# ControlBoardv1_3.net
KiCad netlist of a schematic drawn in EAGLE
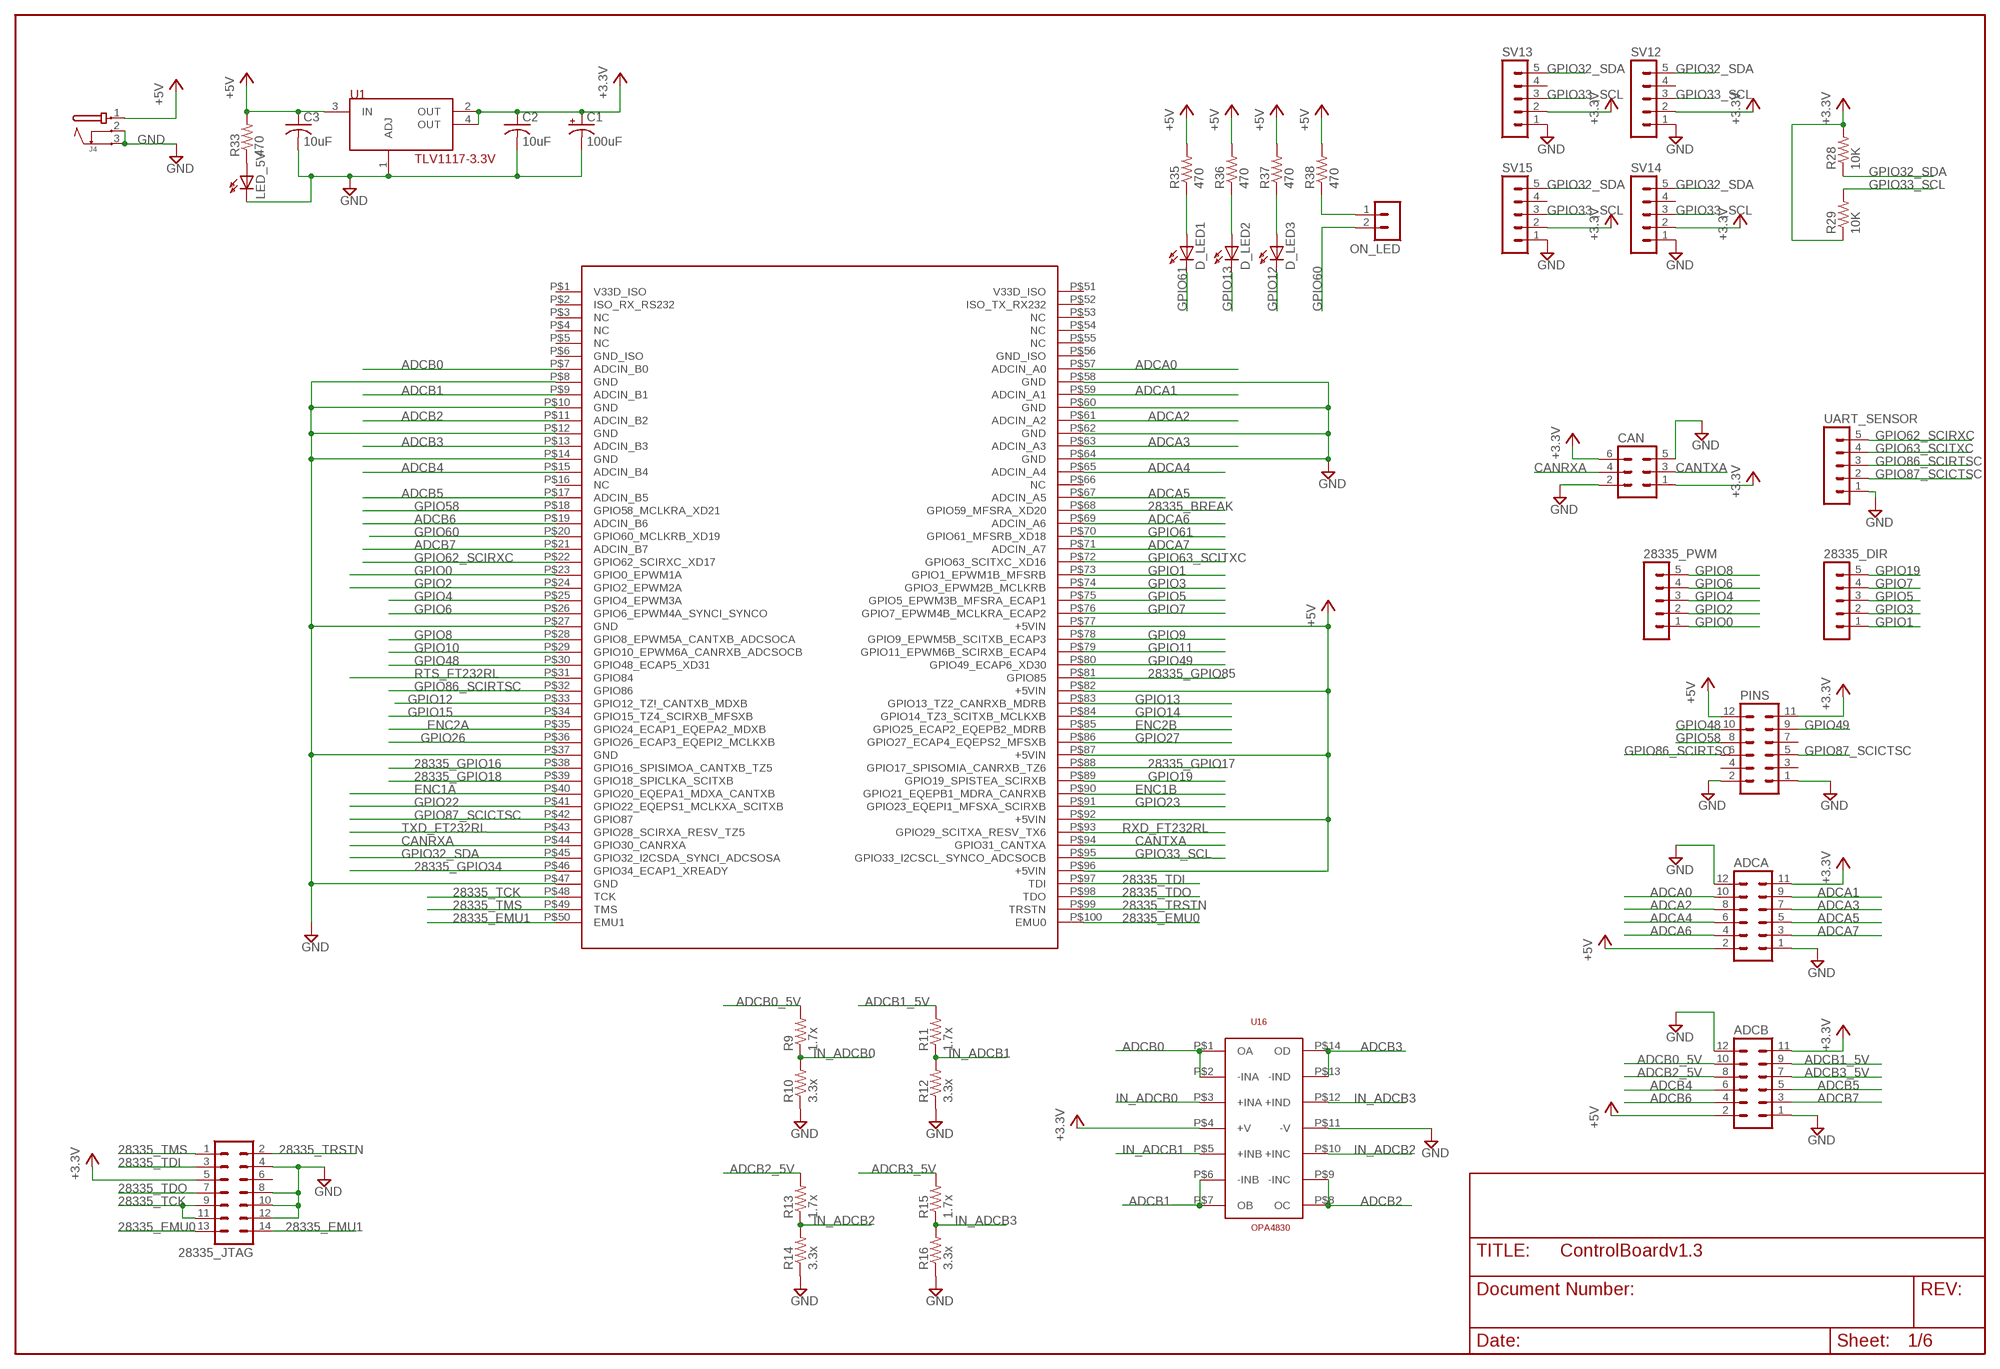
[diagram p0: schematic, sheet 1]
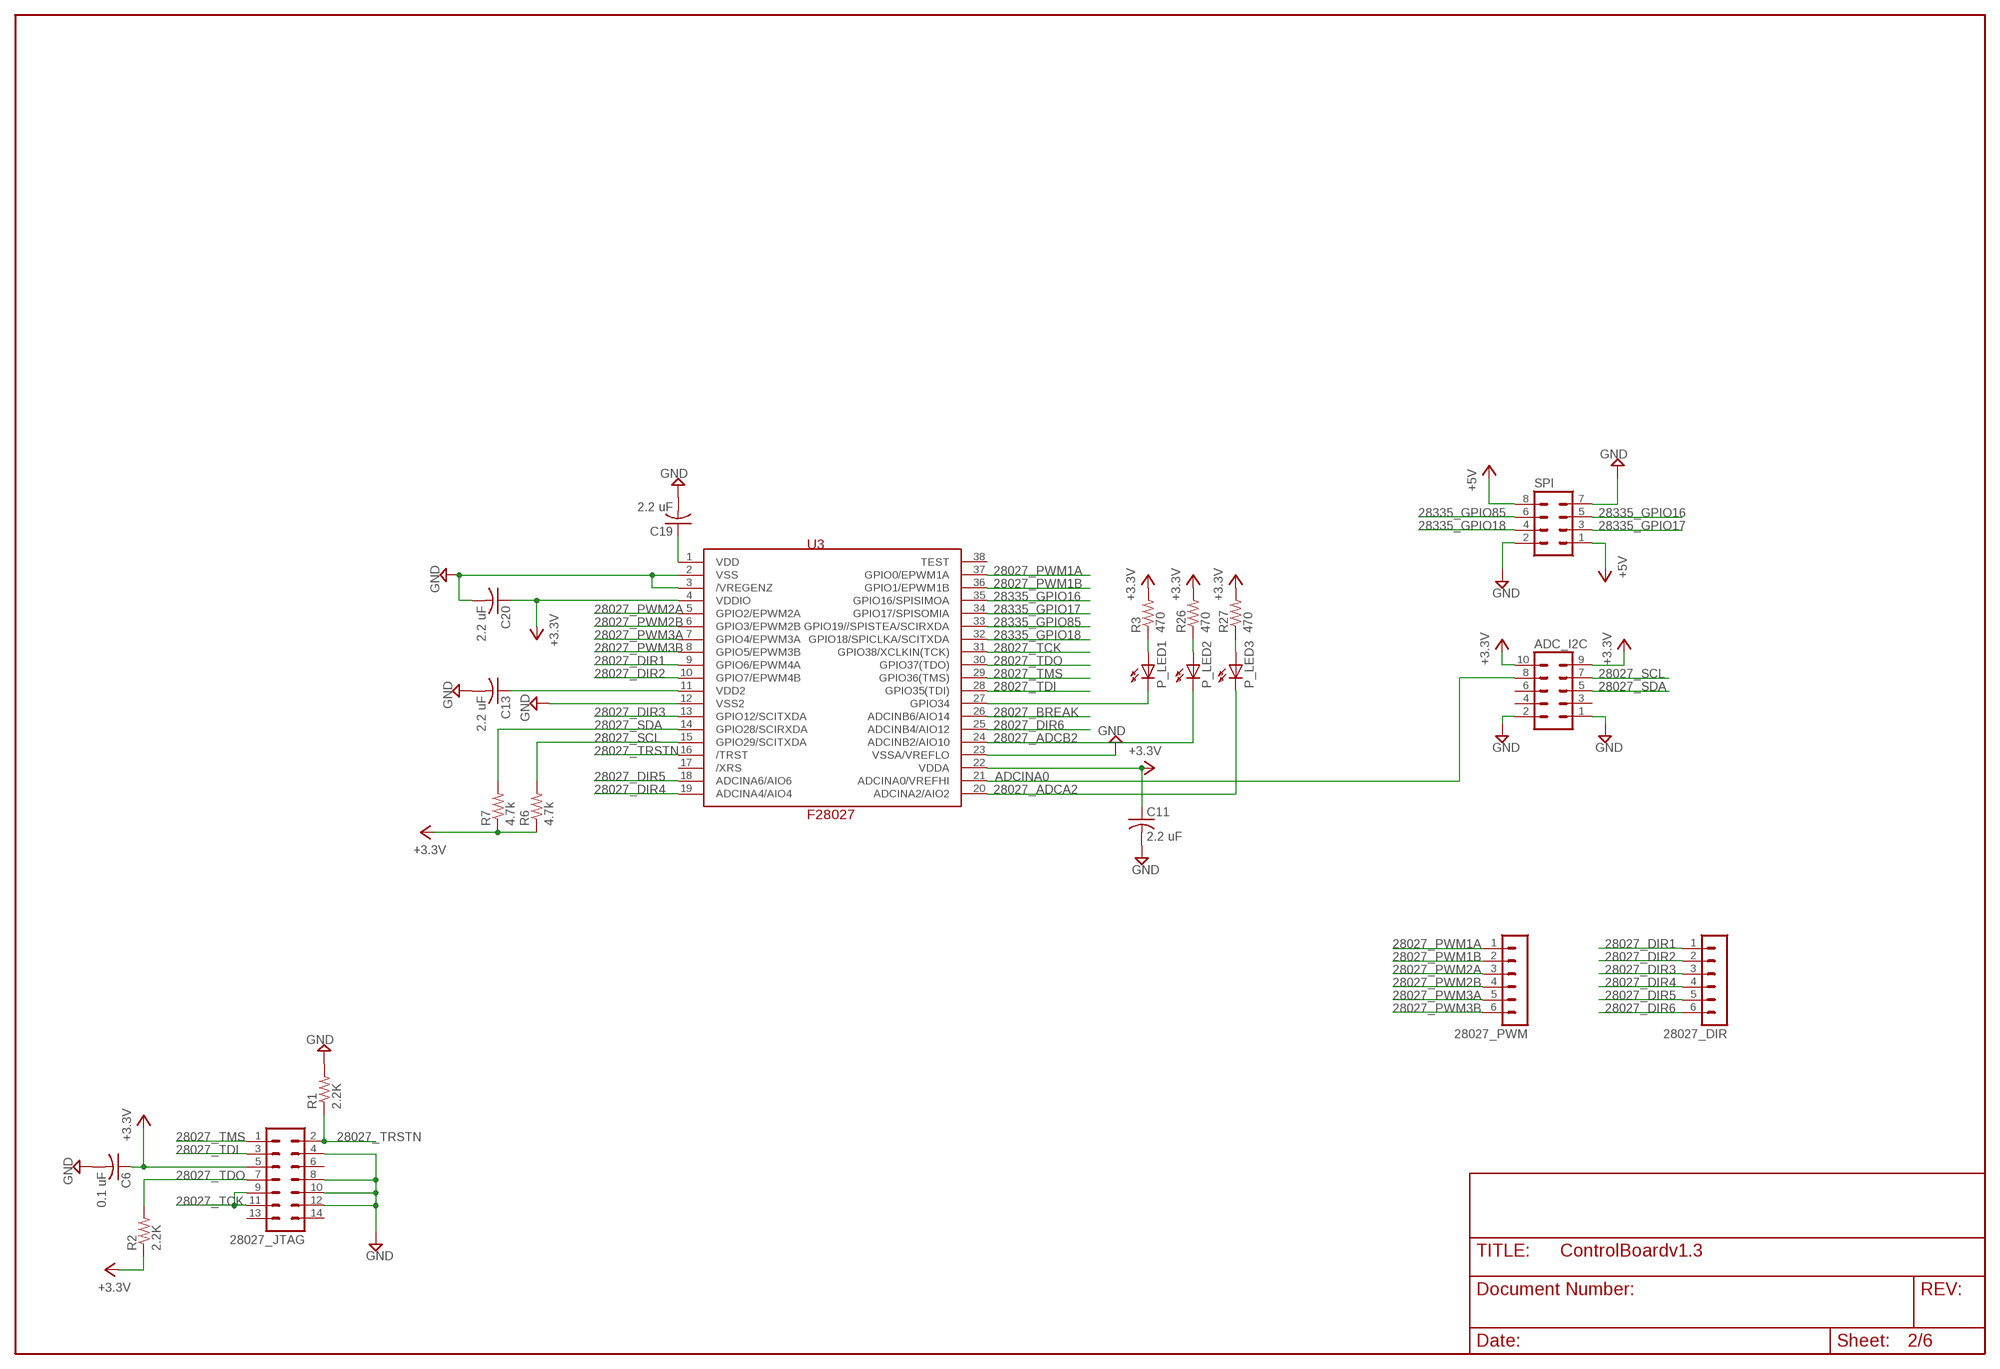
[diagram p1: schematic, sheet 2]
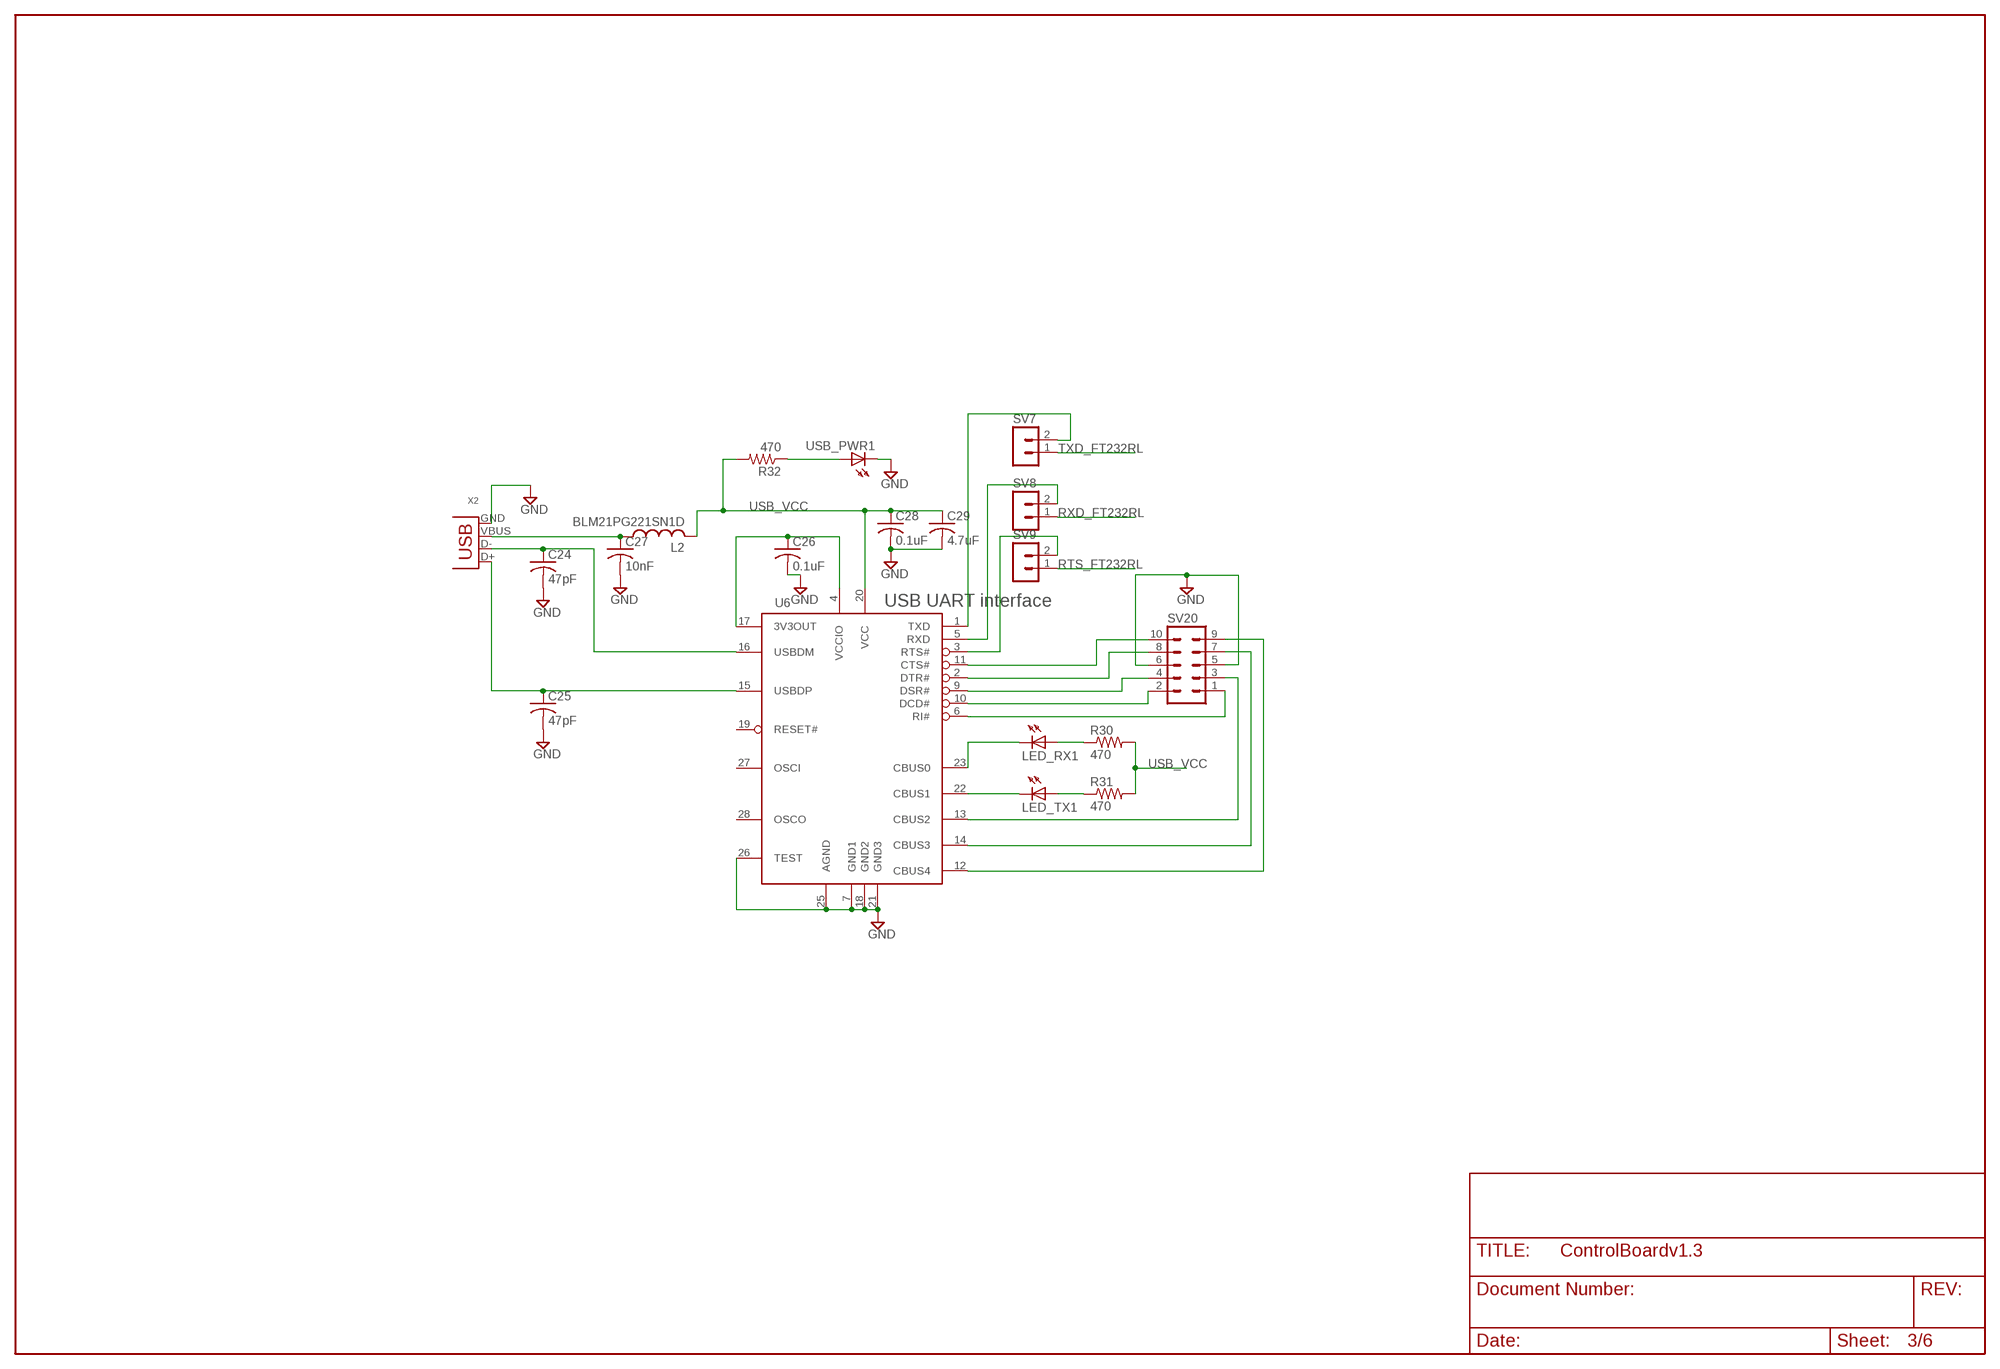
[diagram p2: schematic, sheet 3]
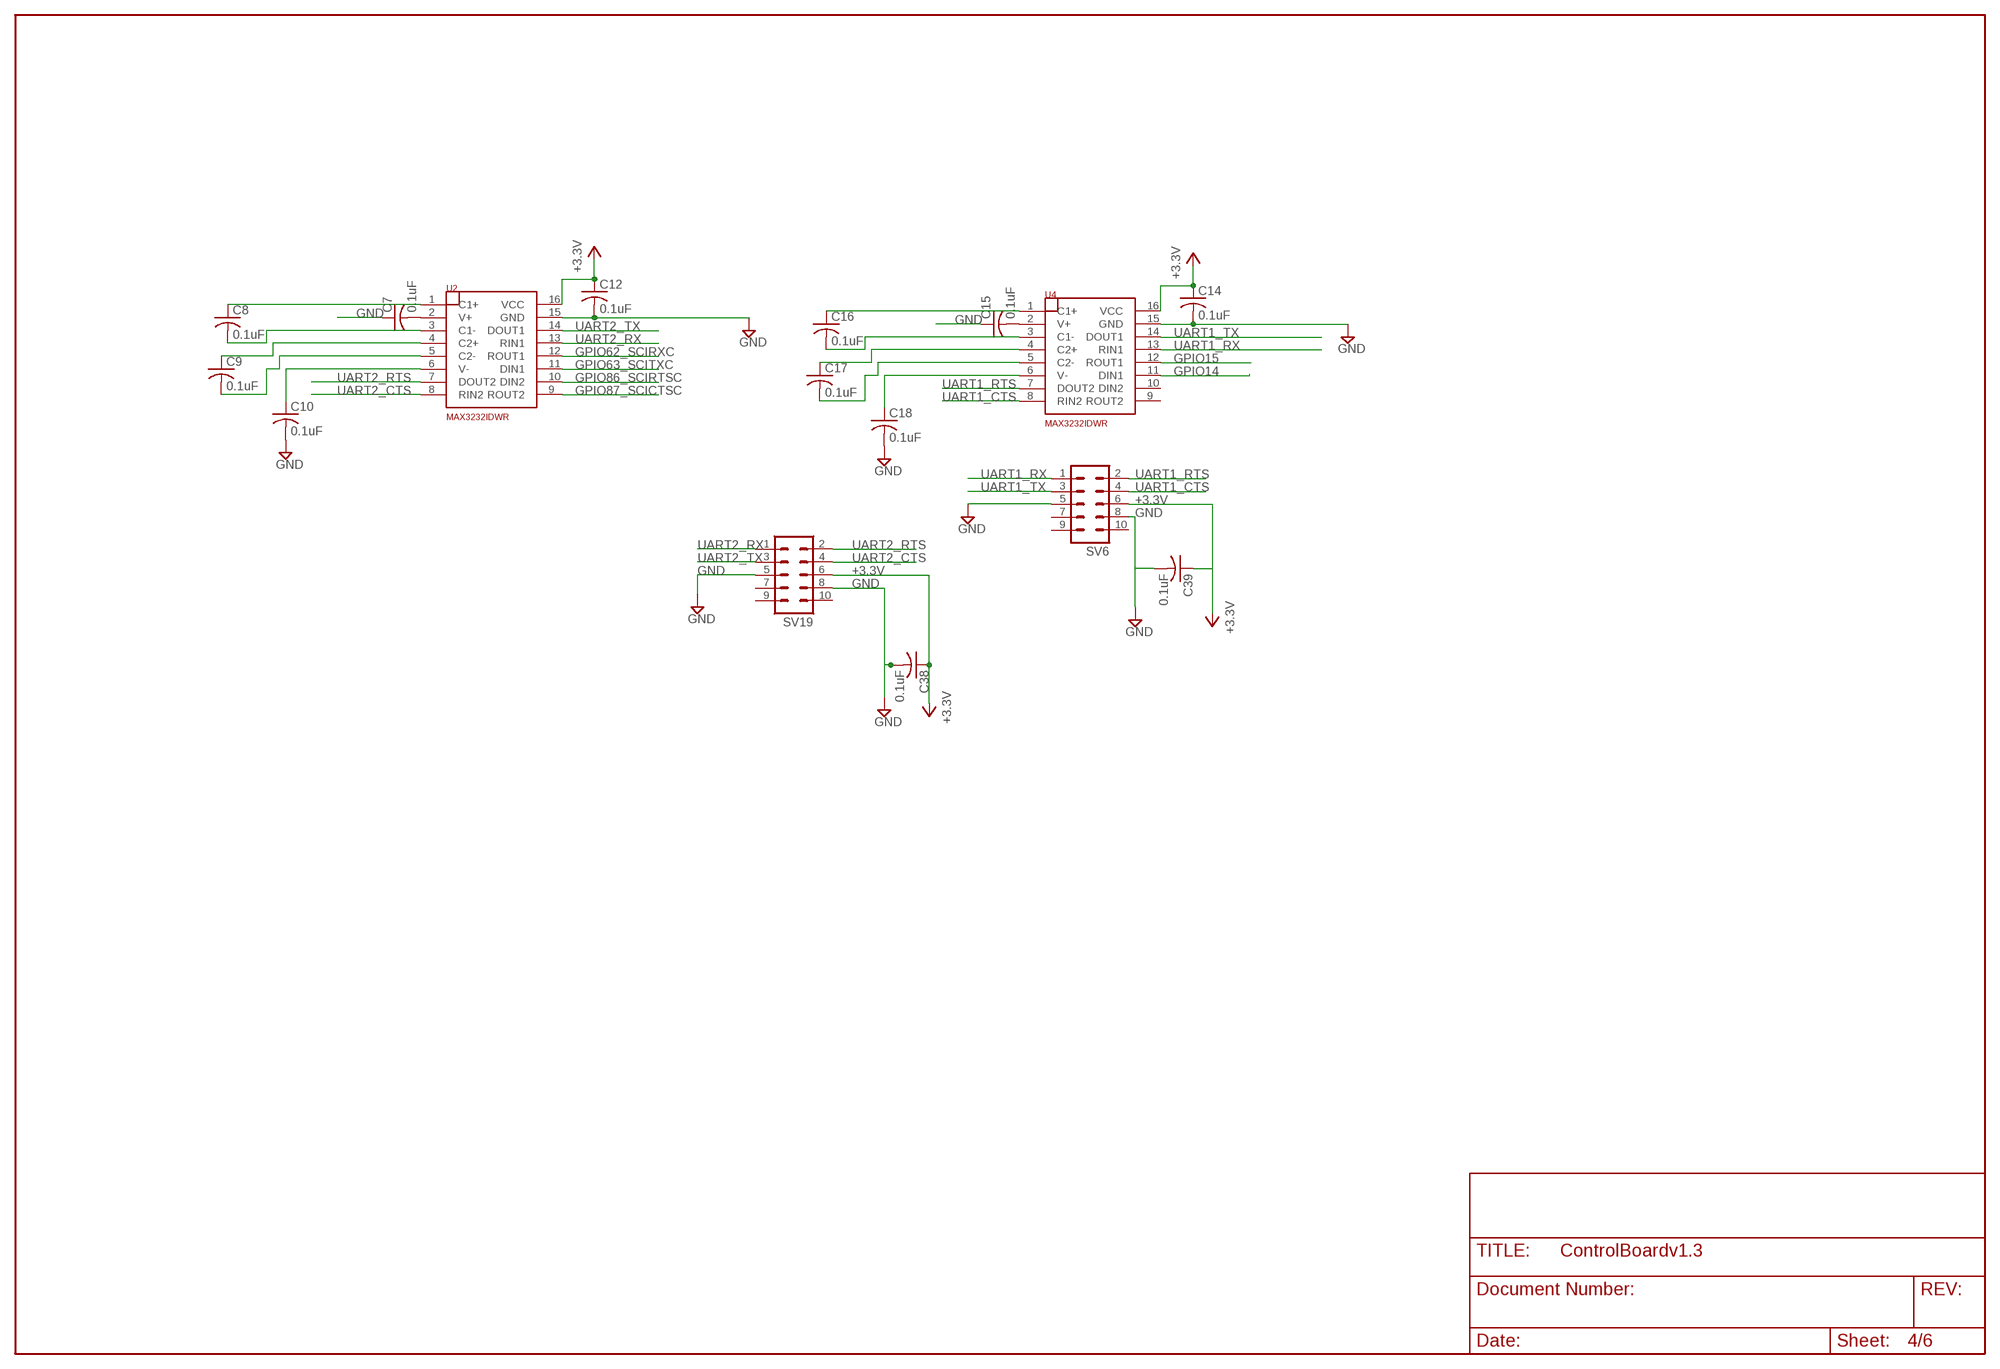
[diagram p3: schematic, sheet 4]
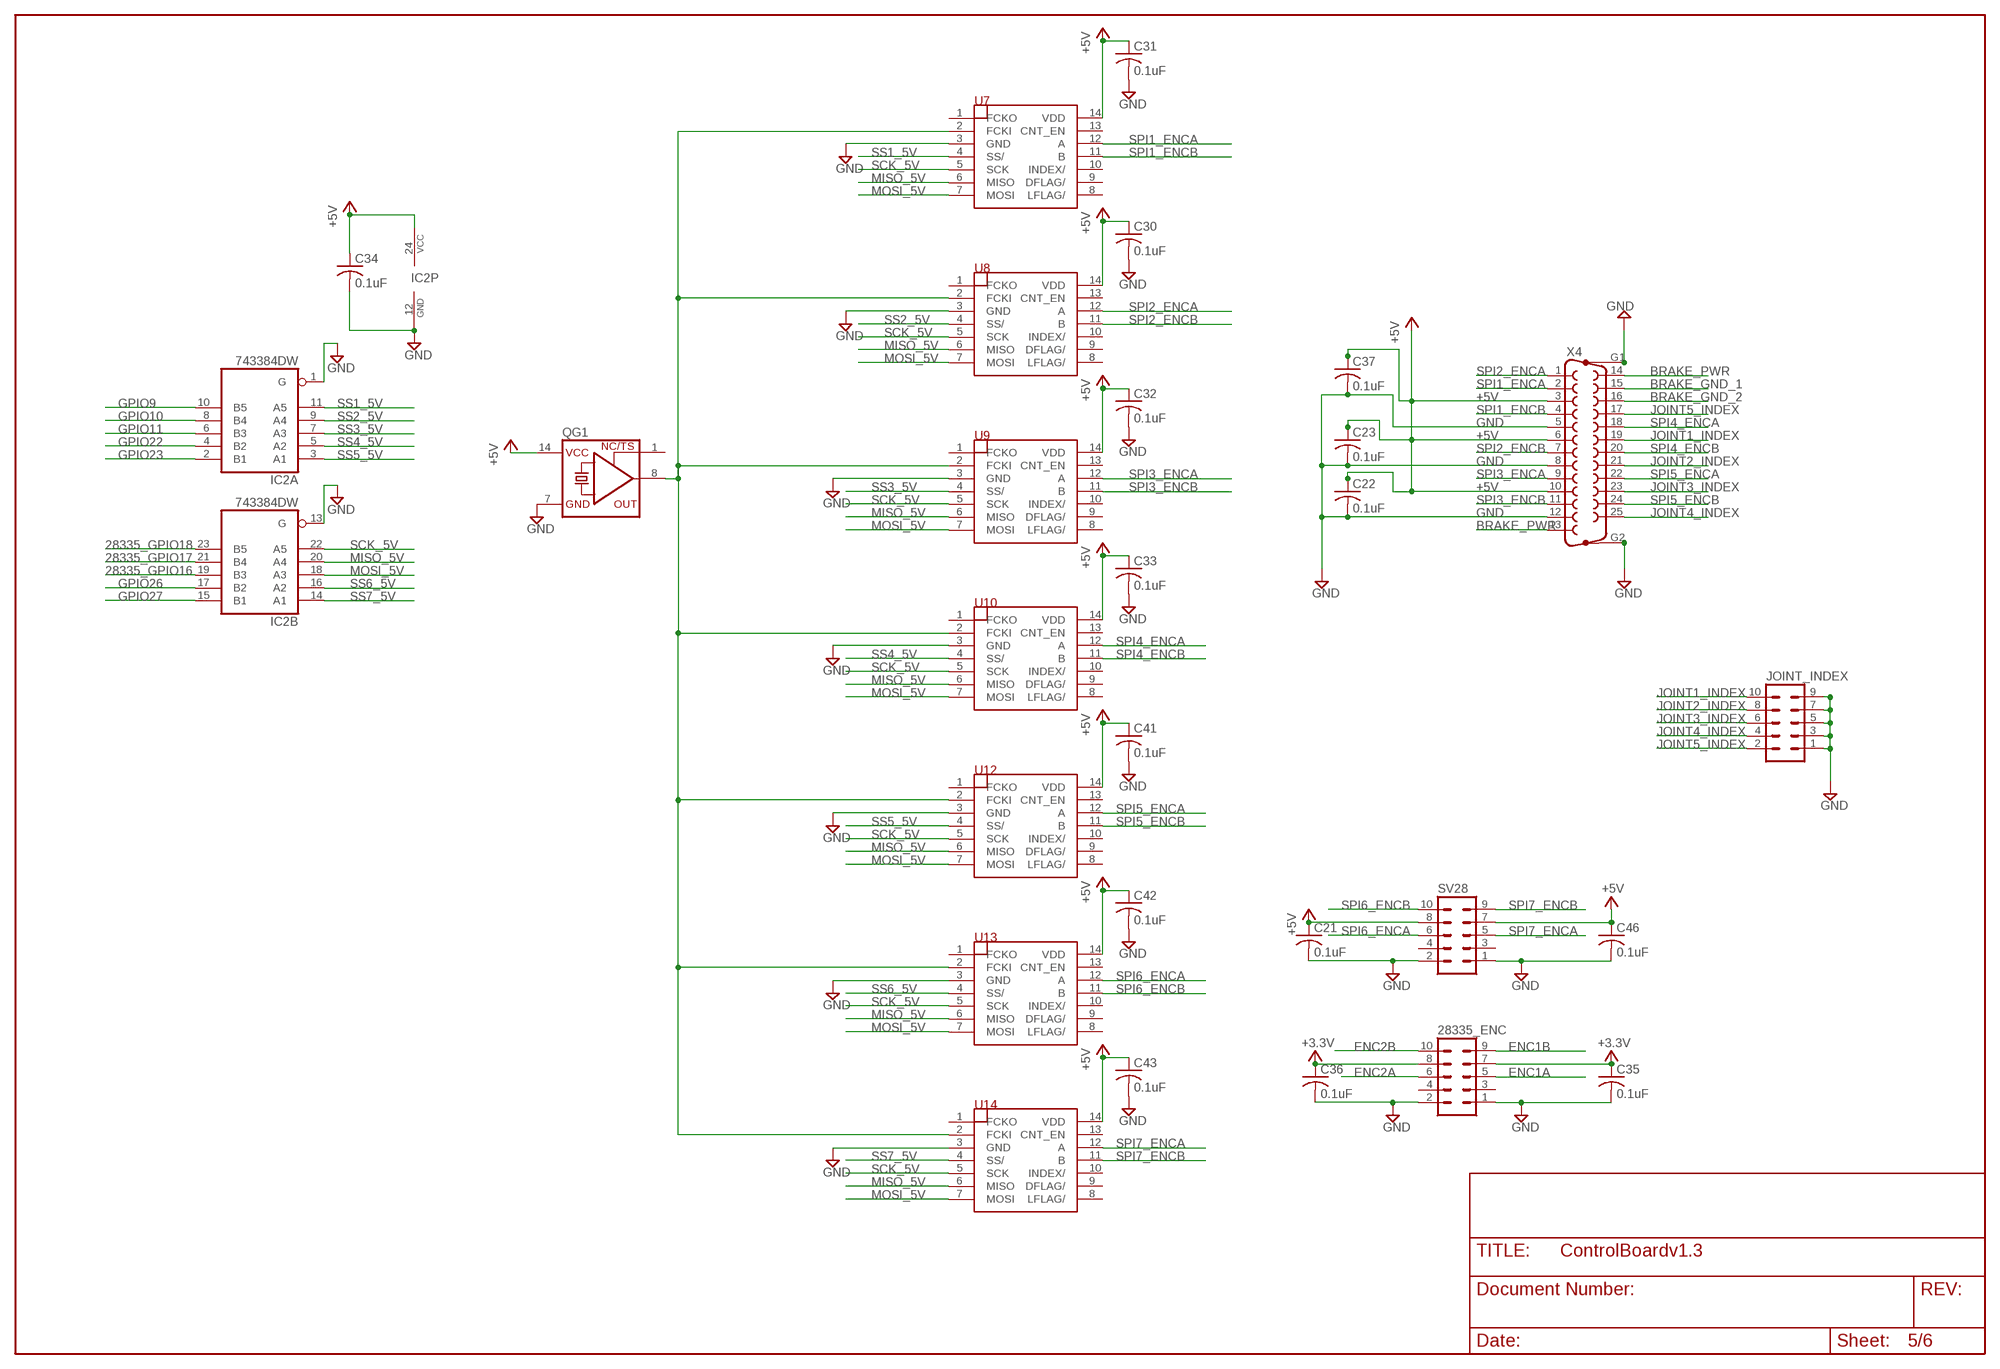
[diagram p4: schematic, sheet 5]
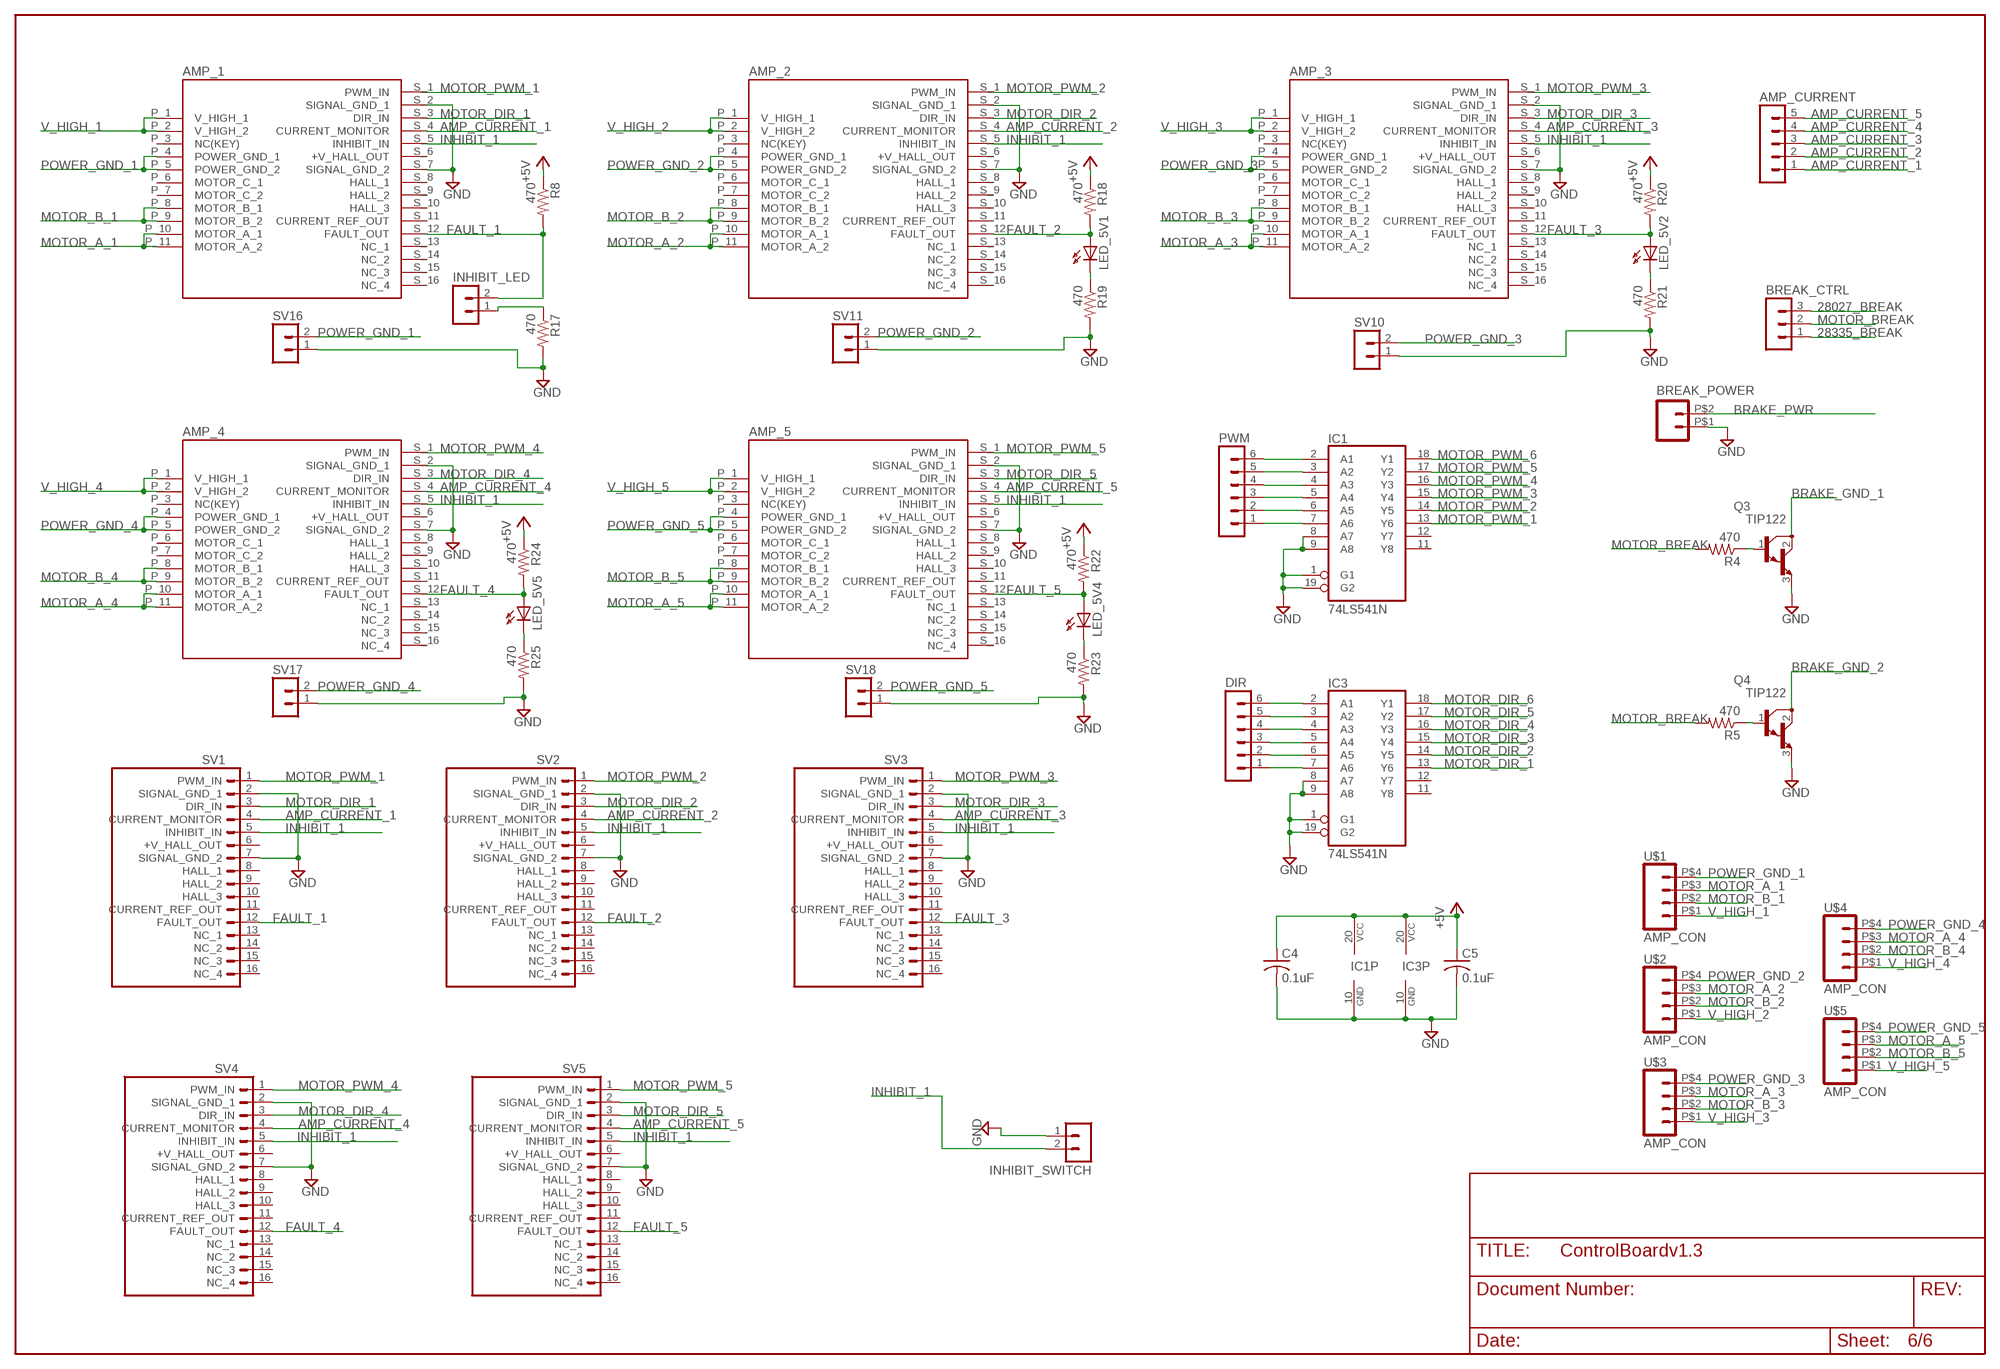
[diagram p5: schematic, sheet 6]

(export (version "E")
  (design (tool "Eeschema 10.0.6"))
  (components
    (comp (ref "C24")
      (value "47pF")
      (footprint "eagle-import:C1206")
      (libsource (lib "eagle-import") (part "C-USC1206"))
    )
    (comp (ref "C25")
      (value "47pF")
      (footprint "eagle-import:C1206")
      (libsource (lib "eagle-import") (part "C-USC1206"))
    )
    (comp (ref "C26")
      (value "0.1uF")
      (footprint "eagle-import:C1206")
      (libsource (lib "eagle-import") (part "C-USC1206"))
    )
    (comp (ref "C27")
      (value "10nF")
      (footprint "eagle-import:C1206")
      (libsource (lib "eagle-import") (part "C-USC1206"))
    )
    (comp (ref "C28")
      (value "0.1uF")
      (footprint "eagle-import:C1206")
      (libsource (lib "eagle-import") (part "C-USC1206"))
    )
    (comp (ref "C29")
      (value "4.7uF")
      (footprint "eagle-import:C1206")
      (libsource (lib "eagle-import") (part "C-USC1206"))
    )
    (comp (ref "L2")
      (value "BLM21PG221SN1D")
      (footprint "eagle-import:L0805")
      (libsource (lib "eagle-import") (part "L-USL0805"))
    )
    (comp (ref "LED_RX1")
      (value "LED3MM")
      (footprint "eagle-import:LED3MM")
      (libsource (lib "eagle-import") (part "LED3MM"))
    )
    (comp (ref "LED_TX1")
      (value "LED3MM")
      (footprint "eagle-import:LED3MM")
      (libsource (lib "eagle-import") (part "LED3MM"))
    )
    (comp (ref "R30")
      (value "470")
      (footprint "eagle-import:M1206")
      (libsource (lib "eagle-import") (part "R-US_M1206"))
    )
    (comp (ref "R31")
      (value "470")
      (footprint "eagle-import:M1206")
      (libsource (lib "eagle-import") (part "R-US_M1206"))
    )
    (comp (ref "R32")
      (value "470")
      (footprint "eagle-import:M1206")
      (libsource (lib "eagle-import") (part "R-US_M1206"))
    )
    (comp (ref "SV7")
      (value "MA02-1")
      (footprint "eagle-import:MA02-1")
      (libsource (lib "eagle-import") (part "MA02-1"))
    )
    (comp (ref "SV8")
      (value "MA02-1")
      (footprint "eagle-import:MA02-1")
      (libsource (lib "eagle-import") (part "MA02-1"))
    )
    (comp (ref "SV9")
      (value "MA02-1")
      (footprint "eagle-import:MA02-1")
      (libsource (lib "eagle-import") (part "MA02-1"))
    )
    (comp (ref "SV20")
      (value "MA05-2")
      (footprint "eagle-import:MA05-2")
      (libsource (lib "eagle-import") (part "MA05-2"))
    )
    (comp (ref "U6")
      (value "FT232RL")
      (footprint "eagle-import:SSOP28DB")
      (libsource (lib "eagle-import") (part "FT232RL"))
    )
    (comp (ref "USB_PWR1")
      (value "LED3MM")
      (footprint "eagle-import:LED3MM")
      (libsource (lib "eagle-import") (part "LED3MM"))
    )
    (comp (ref "X2")
      (value "USB-B-H")
      (footprint "eagle-import:USB-B-H")
      (libsource (lib "eagle-import") (part "USB-B-H"))
    )
    (comp (ref "28027_DIR")
      (value "MA06-1")
      (footprint "eagle-import:MA06-1")
      (libsource (lib "eagle-import") (part "MA06-1"))
    )
    (comp (ref "28027_JTAG")
      (value "MA07-2")
      (footprint "eagle-import:MA07-2")
      (libsource (lib "eagle-import") (part "MA07-2"))
    )
    (comp (ref "28027_PWM")
      (value "MA06-1")
      (footprint "eagle-import:MA06-1")
      (libsource (lib "eagle-import") (part "MA06-1"))
    )
    (comp (ref "ADC_I2C")
      (value "MA05-2")
      (footprint "eagle-import:MA05-2")
      (libsource (lib "eagle-import") (part "MA05-2"))
    )
    (comp (ref "C6")
      (value "0.1 uF")
      (footprint "eagle-import:C1206")
      (libsource (lib "eagle-import") (part "C-USC1206"))
    )
    (comp (ref "C11")
      (value "2.2 uF")
      (footprint "eagle-import:C1206")
      (libsource (lib "eagle-import") (part "C-USC1206"))
    )
    (comp (ref "C13")
      (value "2.2 uF")
      (footprint "eagle-import:C1206")
      (libsource (lib "eagle-import") (part "C-USC1206"))
    )
    (comp (ref "C19")
      (value "2.2 uF")
      (footprint "eagle-import:C1206")
      (libsource (lib "eagle-import") (part "C-USC1206"))
    )
    (comp (ref "C20")
      (value "2.2 uF")
      (footprint "eagle-import:C1206")
      (libsource (lib "eagle-import") (part "C-USC1206"))
    )
    (comp (ref "P_LED1")
      (value "LED3MM")
      (footprint "eagle-import:LED3MM")
      (libsource (lib "eagle-import") (part "LED3MM"))
    )
    (comp (ref "P_LED2")
      (value "LED3MM")
      (footprint "eagle-import:LED3MM")
      (libsource (lib "eagle-import") (part "LED3MM"))
    )
    (comp (ref "P_LED3")
      (value "LED3MM")
      (footprint "eagle-import:LED3MM")
      (libsource (lib "eagle-import") (part "LED3MM"))
    )
    (comp (ref "R1")
      (value "2.2K")
      (footprint "eagle-import:M1206")
      (libsource (lib "eagle-import") (part "R-US_M1206"))
    )
    (comp (ref "R2")
      (value "2.2K")
      (footprint "eagle-import:M1206")
      (libsource (lib "eagle-import") (part "R-US_M1206"))
    )
    (comp (ref "R3")
      (value "470")
      (footprint "eagle-import:M1206")
      (libsource (lib "eagle-import") (part "R-US_M1206"))
    )
    (comp (ref "R6")
      (value "4.7k")
      (footprint "eagle-import:M1206")
      (libsource (lib "eagle-import") (part "R-US_M1206"))
    )
    (comp (ref "R7")
      (value "4.7k")
      (footprint "eagle-import:M1206")
      (libsource (lib "eagle-import") (part "R-US_M1206"))
    )
    (comp (ref "R26")
      (value "470")
      (footprint "eagle-import:M1206")
      (libsource (lib "eagle-import") (part "R-US_M1206"))
    )
    (comp (ref "R27")
      (value "470")
      (footprint "eagle-import:M1206")
      (libsource (lib "eagle-import") (part "R-US_M1206"))
    )
    (comp (ref "SPI")
      (value "MA04-2")
      (footprint "eagle-import:MA04-2")
      (libsource (lib "eagle-import") (part "MA04-2"))
    )
    (comp (ref "U3")
      (value "F28027")
      (footprint "eagle-import:DA38")
      (libsource (lib "eagle-import") (part "TMS320F28027DAS"))
    )
    (comp (ref "28335_DIR")
      (value "MA05-1")
      (footprint "eagle-import:MA05-1")
      (libsource (lib "eagle-import") (part "MA05-1"))
    )
    (comp (ref "28335_JTAG")
      (value "MA07-2")
      (footprint "eagle-import:MA07-2")
      (libsource (lib "eagle-import") (part "MA07-2"))
    )
    (comp (ref "28335_PWM")
      (value "MA05-1")
      (footprint "eagle-import:MA05-1")
      (libsource (lib "eagle-import") (part "MA05-1"))
    )
    (comp (ref "ADCA")
      (value "MA06-2")
      (footprint "eagle-import:MA06-2")
      (libsource (lib "eagle-import") (part "con-lstb_MA06-2"))
    )
    (comp (ref "ADCB")
      (value "MA06-2")
      (footprint "eagle-import:MA06-2")
      (libsource (lib "eagle-import") (part "con-lstb_MA06-2"))
    )
    (comp (ref "C1")
      (value "100uF")
      (footprint "eagle-import:E3,5-8")
      (libsource (lib "eagle-import") (part "CPOL-USE3.5-8"))
    )
    (comp (ref "C2")
      (value "10uF")
      (footprint "eagle-import:C1206")
      (libsource (lib "eagle-import") (part "C-USC1206"))
    )
    (comp (ref "C3")
      (value "10uF")
      (footprint "eagle-import:C1206")
      (libsource (lib "eagle-import") (part "C-USC1206"))
    )
    (comp (ref "CAN")
      (value "MA03-2")
      (footprint "eagle-import:MA03-2")
      (libsource (lib "eagle-import") (part "MA03-2"))
    )
    (comp (ref "D_LED1")
      (value "LED3MM")
      (footprint "eagle-import:LED3MM")
      (libsource (lib "eagle-import") (part "LED3MM"))
    )
    (comp (ref "D_LED2")
      (value "LED3MM")
      (footprint "eagle-import:LED3MM")
      (libsource (lib "eagle-import") (part "LED3MM"))
    )
    (comp (ref "D_LED3")
      (value "LED3MM")
      (footprint "eagle-import:LED3MM")
      (libsource (lib "eagle-import") (part "LED3MM"))
    )
    (comp (ref "J4")
      (value "JACK-PMS")
      (footprint "eagle-import:JACK-PMS")
      (libsource (lib "eagle-import") (part "JACK-PMS"))
    )
    (comp (ref "J7")
      (value "F28335_CONTROLCARD")
      (footprint "eagle-import:MOLEX_DIMM_100")
      (libsource (lib "eagle-import") (part "F28335_CONTROLCARD"))
    )
    (comp (ref "LED_5V")
      (value "LED3MM")
      (footprint "eagle-import:LED3MM")
      (libsource (lib "eagle-import") (part "LED3MM"))
    )
    (comp (ref "ON_LED")
      (value "MA02-1")
      (footprint "eagle-import:MA02-1")
      (libsource (lib "eagle-import") (part "MA02-1"))
    )
    (comp (ref "PINS")
      (value "MA06-2")
      (footprint "eagle-import:MA06-2")
      (libsource (lib "eagle-import") (part "MA06-2"))
    )
    (comp (ref "R9")
      (value "1.7x")
      (footprint "eagle-import:M1206")
      (libsource (lib "eagle-import") (part "R-US_M1206"))
    )
    (comp (ref "R10")
      (value "3.3x")
      (footprint "eagle-import:M1206")
      (libsource (lib "eagle-import") (part "R-US_M1206"))
    )
    (comp (ref "R11")
      (value "1.7x")
      (footprint "eagle-import:M1206")
      (libsource (lib "eagle-import") (part "R-US_M1206"))
    )
    (comp (ref "R12")
      (value "3.3x")
      (footprint "eagle-import:M1206")
      (libsource (lib "eagle-import") (part "R-US_M1206"))
    )
    (comp (ref "R13")
      (value "1.7x")
      (footprint "eagle-import:M1206")
      (libsource (lib "eagle-import") (part "R-US_M1206"))
    )
    (comp (ref "R14")
      (value "3.3x")
      (footprint "eagle-import:M1206")
      (libsource (lib "eagle-import") (part "R-US_M1206"))
    )
    (comp (ref "R15")
      (value "1.7x")
      (footprint "eagle-import:M1206")
      (libsource (lib "eagle-import") (part "R-US_M1206"))
    )
    (comp (ref "R16")
      (value "3.3x")
      (footprint "eagle-import:M1206")
      (libsource (lib "eagle-import") (part "R-US_M1206"))
    )
    (comp (ref "R28")
      (value "10K")
      (footprint "eagle-import:M1206")
      (libsource (lib "eagle-import") (part "R-US_M1206"))
    )
    (comp (ref "R29")
      (value "10K")
      (footprint "eagle-import:M1206")
      (libsource (lib "eagle-import") (part "R-US_M1206"))
    )
    (comp (ref "R33")
      (value "470")
      (footprint "eagle-import:M1206")
      (libsource (lib "eagle-import") (part "R-US_M1206"))
    )
    (comp (ref "R35")
      (value "470")
      (footprint "eagle-import:M1206")
      (libsource (lib "eagle-import") (part "R-US_M1206"))
    )
    (comp (ref "R36")
      (value "470")
      (footprint "eagle-import:M1206")
      (libsource (lib "eagle-import") (part "R-US_M1206"))
    )
    (comp (ref "R37")
      (value "470")
      (footprint "eagle-import:M1206")
      (libsource (lib "eagle-import") (part "R-US_M1206"))
    )
    (comp (ref "R38")
      (value "470")
      (footprint "eagle-import:M1206")
      (libsource (lib "eagle-import") (part "R-US_M1206"))
    )
    (comp (ref "SV12")
      (value "MA05-1")
      (footprint "eagle-import:MA05-1")
      (libsource (lib "eagle-import") (part "MA05-1"))
    )
    (comp (ref "SV13")
      (value "MA05-1")
      (footprint "eagle-import:MA05-1")
      (libsource (lib "eagle-import") (part "MA05-1"))
    )
    (comp (ref "SV14")
      (value "MA05-1")
      (footprint "eagle-import:MA05-1")
      (libsource (lib "eagle-import") (part "MA05-1"))
    )
    (comp (ref "SV15")
      (value "MA05-1")
      (footprint "eagle-import:MA05-1")
      (libsource (lib "eagle-import") (part "MA05-1"))
    )
    (comp (ref "U1")
      (value "TLV1117-3.3V")
      (footprint "eagle-import:SOT223")
      (libsource (lib "eagle-import") (part "TLV1117-ADJ"))
    )
    (comp (ref "U16")
      (value "OPA4830")
      (footprint "eagle-import:OPA4830-TSSOP-14")
      (libsource (lib "eagle-import") (part "OPA4830"))
    )
    (comp (ref "UART_SENSOR")
      (value "MA05-1")
      (footprint "eagle-import:MA05-1")
      (libsource (lib "eagle-import") (part "MA05-1"))
    )
    (comp (ref "C7")
      (value "0.1uF")
      (footprint "eagle-import:C0805K")
      (libsource (lib "eagle-import") (part "C-USC0805K"))
    )
    (comp (ref "C8")
      (value "0.1uF")
      (footprint "eagle-import:C0805K")
      (libsource (lib "eagle-import") (part "C-USC0805K"))
    )
    (comp (ref "C9")
      (value "0.1uF")
      (footprint "eagle-import:C0805K")
      (libsource (lib "eagle-import") (part "C-USC0805K"))
    )
    (comp (ref "C10")
      (value "0.1uF")
      (footprint "eagle-import:C0805K")
      (libsource (lib "eagle-import") (part "C-USC0805K"))
    )
    (comp (ref "C12")
      (value "0.1uF")
      (footprint "eagle-import:C0805K")
      (libsource (lib "eagle-import") (part "C-USC0805K"))
    )
    (comp (ref "C14")
      (value "0.1uF")
      (footprint "eagle-import:C0805K")
      (libsource (lib "eagle-import") (part "C-USC0805K"))
    )
    (comp (ref "C15")
      (value "0.1uF")
      (footprint "eagle-import:C0805K")
      (libsource (lib "eagle-import") (part "C-USC0805K"))
    )
    (comp (ref "C16")
      (value "0.1uF")
      (footprint "eagle-import:C0805K")
      (libsource (lib "eagle-import") (part "C-USC0805K"))
    )
    (comp (ref "C17")
      (value "0.1uF")
      (footprint "eagle-import:C0805K")
      (libsource (lib "eagle-import") (part "C-USC0805K"))
    )
    (comp (ref "C18")
      (value "0.1uF")
      (footprint "eagle-import:C0805K")
      (libsource (lib "eagle-import") (part "C-USC0805K"))
    )
    (comp (ref "C38")
      (value "0.1uF")
      (footprint "eagle-import:C0805K")
      (libsource (lib "eagle-import") (part "C-USC0805K"))
    )
    (comp (ref "C39")
      (value "0.1uF")
      (footprint "eagle-import:C0805K")
      (libsource (lib "eagle-import") (part "C-USC0805K"))
    )
    (comp (ref "SV6")
      (value "MA05-2")
      (footprint "eagle-import:MA05-2")
      (libsource (lib "eagle-import") (part "MA05-2"))
    )
    (comp (ref "SV19")
      (value "MA05-2")
      (footprint "eagle-import:MA05-2")
      (libsource (lib "eagle-import") (part "MA05-2"))
    )
    (comp (ref "U2")
      (value "MAX3232IDWR")
      (footprint "eagle-import:SO16W")
      (libsource (lib "eagle-import") (part "MAX3232IDWR"))
    )
    (comp (ref "U4")
      (value "MAX3232IDWR")
      (footprint "eagle-import:SO16W")
      (libsource (lib "eagle-import") (part "MAX3232IDWR"))
    )
    (comp (ref "28335_ENC")
      (value "MA05-2")
      (footprint "eagle-import:MA05-2")
      (libsource (lib "eagle-import") (part "MA05-2"))
    )
    (comp (ref "C21")
      (value "0.1uF")
      (footprint "eagle-import:C1206")
      (libsource (lib "eagle-import") (part "C-USC1206"))
    )
    (comp (ref "C22")
      (value "0.1uF")
      (footprint "eagle-import:C1206")
      (libsource (lib "eagle-import") (part "C-USC1206"))
    )
    (comp (ref "C23")
      (value "0.1uF")
      (footprint "eagle-import:C1206")
      (libsource (lib "eagle-import") (part "C-USC1206"))
    )
    (comp (ref "C30")
      (value "0.1uF")
      (footprint "eagle-import:C1206")
      (libsource (lib "eagle-import") (part "C-USC1206"))
    )
    (comp (ref "C31")
      (value "0.1uF")
      (footprint "eagle-import:C1206")
      (libsource (lib "eagle-import") (part "C-USC1206"))
    )
    (comp (ref "C32")
      (value "0.1uF")
      (footprint "eagle-import:C1206")
      (libsource (lib "eagle-import") (part "C-USC1206"))
    )
    (comp (ref "C33")
      (value "0.1uF")
      (footprint "eagle-import:C1206")
      (libsource (lib "eagle-import") (part "C-USC1206"))
    )
    (comp (ref "C34")
      (value "0.1uF")
      (footprint "eagle-import:C1206")
      (libsource (lib "eagle-import") (part "C-USC1206"))
    )
    (comp (ref "C35")
      (value "0.1uF")
      (footprint "eagle-import:C1206")
      (libsource (lib "eagle-import") (part "C-USC1206"))
    )
    (comp (ref "C36")
      (value "0.1uF")
      (footprint "eagle-import:C1206")
      (libsource (lib "eagle-import") (part "C-USC1206"))
    )
    (comp (ref "C37")
      (value "0.1uF")
      (footprint "eagle-import:C1206")
      (libsource (lib "eagle-import") (part "C-USC1206"))
    )
    (comp (ref "C41")
      (value "0.1uF")
      (footprint "eagle-import:C1206")
      (libsource (lib "eagle-import") (part "C-USC1206"))
    )
    (comp (ref "C42")
      (value "0.1uF")
      (footprint "eagle-import:C1206")
      (libsource (lib "eagle-import") (part "C-USC1206"))
    )
    (comp (ref "C43")
      (value "0.1uF")
      (footprint "eagle-import:C1206")
      (libsource (lib "eagle-import") (part "C-USC1206"))
    )
    (comp (ref "C46")
      (value "0.1uF")
      (footprint "eagle-import:C1206")
      (libsource (lib "eagle-import") (part "C-USC1206"))
    )
    (comp (ref "IC2")
      (value "743384DW")
      (footprint "eagle-import:SO24W")
      (libsource (lib "eagle-import") (part "743384DW"))
    )
    (comp (ref "JOINT_INDEX")
      (value "MA05-2")
      (footprint "eagle-import:MA05-2")
      (libsource (lib "eagle-import") (part "MA05-2"))
    )
    (comp (ref "QG1")
      (value "XO-14")
      (footprint "eagle-import:DIL14S")
      (libsource (lib "eagle-import") (part "XO-14"))
    )
    (comp (ref "SV28")
      (value "MA05-2")
      (footprint "eagle-import:MA05-2")
      (libsource (lib "eagle-import") (part "MA05-2"))
    )
    (comp (ref "U7")
      (value "LS7366R")
      (footprint "eagle-import:SO14")
      (libsource (lib "eagle-import") (part "LS7366R"))
    )
    (comp (ref "U8")
      (value "LS7366R")
      (footprint "eagle-import:SO14")
      (libsource (lib "eagle-import") (part "LS7366R"))
    )
    (comp (ref "U9")
      (value "LS7366R")
      (footprint "eagle-import:SO14")
      (libsource (lib "eagle-import") (part "LS7366R"))
    )
    (comp (ref "U10")
      (value "LS7366R")
      (footprint "eagle-import:SO14")
      (libsource (lib "eagle-import") (part "LS7366R"))
    )
    (comp (ref "U12")
      (value "LS7366R")
      (footprint "eagle-import:SO14")
      (libsource (lib "eagle-import") (part "LS7366R"))
    )
    (comp (ref "U13")
      (value "LS7366R")
      (footprint "eagle-import:SO14")
      (libsource (lib "eagle-import") (part "LS7366R"))
    )
    (comp (ref "U14")
      (value "LS7366R")
      (footprint "eagle-import:SO14")
      (libsource (lib "eagle-import") (part "LS7366R"))
    )
    (comp (ref "X4")
      (value "F25HP")
      (footprint "eagle-import:F25HP")
      (libsource (lib "eagle-import") (part "F25HP"))
    )
    (comp (ref "AMP_1")
      (value "AZBDC12A8THROUGH_HOLE")
      (footprint "eagle-import:AZBDC12A8")
      (libsource (lib "eagle-import") (part "AZBDC12A8THROUGH_HOLE"))
    )
    (comp (ref "AMP_2")
      (value "AZBDC12A8THROUGH_HOLE")
      (footprint "eagle-import:AZBDC12A8")
      (libsource (lib "eagle-import") (part "AZBDC12A8THROUGH_HOLE"))
    )
    (comp (ref "AMP_3")
      (value "AZBDC12A8THROUGH_HOLE")
      (footprint "eagle-import:AZBDC12A8")
      (libsource (lib "eagle-import") (part "AZBDC12A8THROUGH_HOLE"))
    )
    (comp (ref "AMP_4")
      (value "AZBDC12A8THROUGH_HOLE")
      (footprint "eagle-import:AZBDC12A8")
      (libsource (lib "eagle-import") (part "AZBDC12A8THROUGH_HOLE"))
    )
    (comp (ref "AMP_5")
      (value "AZBDC12A8THROUGH_HOLE")
      (footprint "eagle-import:AZBDC12A8")
      (libsource (lib "eagle-import") (part "AZBDC12A8THROUGH_HOLE"))
    )
    (comp (ref "AMP_CURRENT")
      (value "MA05-1")
      (footprint "eagle-import:MA05-1")
      (libsource (lib "eagle-import") (part "MA05-1"))
    )
    (comp (ref "BREAK_CTRL")
      (value "MA03-1")
      (footprint "eagle-import:MA03-1")
      (libsource (lib "eagle-import") (part "MA03-1"))
    )
    (comp (ref "BREAK_POWER")
      (value "BREAK_POWER_CON")
      (footprint "eagle-import:BREAK_POWER_CON")
      (libsource (lib "eagle-import") (part "BREAK_POWER_CON"))
    )
    (comp (ref "C4")
      (value "0.1uF")
      (footprint "eagle-import:C1206")
      (libsource (lib "eagle-import") (part "C-USC1206"))
    )
    (comp (ref "C5")
      (value "0.1uF")
      (footprint "eagle-import:C1206")
      (libsource (lib "eagle-import") (part "C-USC1206"))
    )
    (comp (ref "DIR")
      (value "MA06-1")
      (footprint "eagle-import:MA06-1")
      (libsource (lib "eagle-import") (part "MA06-1"))
    )
    (comp (ref "IC1")
      (value "74LS541N")
      (footprint "eagle-import:DIL20")
      (libsource (lib "eagle-import") (part "74541NLS"))
    )
    (comp (ref "IC3")
      (value "74LS541N")
      (footprint "eagle-import:DIL20")
      (libsource (lib "eagle-import") (part "74541NLS"))
    )
    (comp (ref "INHIBIT_LED")
      (value "MA02-1")
      (footprint "eagle-import:MA02-1")
      (libsource (lib "eagle-import") (part "MA02-1"))
    )
    (comp (ref "INHIBIT_SWITCH")
      (value "MA02-1")
      (footprint "eagle-import:MA02-1")
      (libsource (lib "eagle-import") (part "MA02-1"))
    )
    (comp (ref "LED_5V1")
      (value "LED3MM")
      (footprint "eagle-import:LED3MM")
      (libsource (lib "eagle-import") (part "LED3MM"))
    )
    (comp (ref "LED_5V2")
      (value "LED3MM")
      (footprint "eagle-import:LED3MM")
      (libsource (lib "eagle-import") (part "LED3MM"))
    )
    (comp (ref "LED_5V4")
      (value "LED3MM")
      (footprint "eagle-import:LED3MM")
      (libsource (lib "eagle-import") (part "LED3MM"))
    )
    (comp (ref "LED_5V5")
      (value "LED3MM")
      (footprint "eagle-import:LED3MM")
      (libsource (lib "eagle-import") (part "LED3MM"))
    )
    (comp (ref "PWM")
      (value "MA06-1")
      (footprint "eagle-import:MA06-1")
      (libsource (lib "eagle-import") (part "MA06-1"))
    )
    (comp (ref "Q3")
      (value "TIP122")
      (footprint "eagle-import:TO220")
      (libsource (lib "eagle-import") (part "TIP122"))
    )
    (comp (ref "Q4")
      (value "TIP122")
      (footprint "eagle-import:TO220")
      (libsource (lib "eagle-import") (part "TIP122"))
    )
    (comp (ref "R4")
      (value "470")
      (footprint "eagle-import:M1206")
      (libsource (lib "eagle-import") (part "R-US_M1206"))
    )
    (comp (ref "R5")
      (value "470")
      (footprint "eagle-import:M1206")
      (libsource (lib "eagle-import") (part "R-US_M1206"))
    )
    (comp (ref "R8")
      (value "470")
      (footprint "eagle-import:M1206")
      (libsource (lib "eagle-import") (part "R-US_M1206"))
    )
    (comp (ref "R17")
      (value "470")
      (footprint "eagle-import:M1206")
      (libsource (lib "eagle-import") (part "R-US_M1206"))
    )
    (comp (ref "R18")
      (value "470")
      (footprint "eagle-import:M1206")
      (libsource (lib "eagle-import") (part "R-US_M1206"))
    )
    (comp (ref "R19")
      (value "470")
      (footprint "eagle-import:M1206")
      (libsource (lib "eagle-import") (part "R-US_M1206"))
    )
    (comp (ref "R20")
      (value "470")
      (footprint "eagle-import:M1206")
      (libsource (lib "eagle-import") (part "R-US_M1206"))
    )
    (comp (ref "R21")
      (value "470")
      (footprint "eagle-import:M1206")
      (libsource (lib "eagle-import") (part "R-US_M1206"))
    )
    (comp (ref "R22")
      (value "470")
      (footprint "eagle-import:M1206")
      (libsource (lib "eagle-import") (part "R-US_M1206"))
    )
    (comp (ref "R23")
      (value "470")
      (footprint "eagle-import:M1206")
      (libsource (lib "eagle-import") (part "R-US_M1206"))
    )
    (comp (ref "R24")
      (value "470")
      (footprint "eagle-import:M1206")
      (libsource (lib "eagle-import") (part "R-US_M1206"))
    )
    (comp (ref "R25")
      (value "470")
      (footprint "eagle-import:M1206")
      (libsource (lib "eagle-import") (part "R-US_M1206"))
    )
    (comp (ref "SV1")
      (value "AMP_HEADER")
      (footprint "eagle-import:AMP_HEADER")
      (libsource (lib "eagle-import") (part "AMP_HEADER"))
    )
    (comp (ref "SV2")
      (value "AMP_HEADER")
      (footprint "eagle-import:AMP_HEADER")
      (libsource (lib "eagle-import") (part "AMP_HEADER"))
    )
    (comp (ref "SV3")
      (value "AMP_HEADER")
      (footprint "eagle-import:AMP_HEADER")
      (libsource (lib "eagle-import") (part "AMP_HEADER"))
    )
    (comp (ref "SV4")
      (value "AMP_HEADER")
      (footprint "eagle-import:AMP_HEADER")
      (libsource (lib "eagle-import") (part "AMP_HEADER"))
    )
    (comp (ref "SV5")
      (value "AMP_HEADER")
      (footprint "eagle-import:AMP_HEADER")
      (libsource (lib "eagle-import") (part "AMP_HEADER"))
    )
    (comp (ref "SV10")
      (value "MA02-1")
      (footprint "eagle-import:MA02-1")
      (libsource (lib "eagle-import") (part "MA02-1"))
    )
    (comp (ref "SV11")
      (value "MA02-1")
      (footprint "eagle-import:MA02-1")
      (libsource (lib "eagle-import") (part "MA02-1"))
    )
    (comp (ref "SV16")
      (value "MA02-1")
      (footprint "eagle-import:MA02-1")
      (libsource (lib "eagle-import") (part "MA02-1"))
    )
    (comp (ref "SV17")
      (value "MA02-1")
      (footprint "eagle-import:MA02-1")
      (libsource (lib "eagle-import") (part "MA02-1"))
    )
    (comp (ref "SV18")
      (value "MA02-1")
      (footprint "eagle-import:MA02-1")
      (libsource (lib "eagle-import") (part "MA02-1"))
    )
    (comp (ref "U$1")
      (value "AMP_CON")
      (footprint "eagle-import:APM_CON")
      (libsource (lib "eagle-import") (part "AMP_CON"))
    )
    (comp (ref "U$2")
      (value "AMP_CON")
      (footprint "eagle-import:APM_CON")
      (libsource (lib "eagle-import") (part "AMP_CON"))
    )
    (comp (ref "U$3")
      (value "AMP_CON")
      (footprint "eagle-import:APM_CON")
      (libsource (lib "eagle-import") (part "AMP_CON"))
    )
    (comp (ref "U$4")
      (value "AMP_CON")
      (footprint "eagle-import:APM_CON")
      (libsource (lib "eagle-import") (part "AMP_CON"))
    )
    (comp (ref "U$5")
      (value "AMP_CON")
      (footprint "eagle-import:APM_CON")
      (libsource (lib "eagle-import") (part "AMP_CON"))
    )
  )
  (nets
    (net (code "1") (name "+3.3V") (class "Default")
      (node (ref "28027_JTAG") (pin "5") (pinfunction "5_5") (pintype "passive"))
      (node (ref "28335_ENC") (pin "7") (pinfunction "7_7") (pintype "passive"))
      (node (ref "28335_ENC") (pin "8") (pinfunction "8_8") (pintype "passive"))
      (node (ref "28335_JTAG") (pin "5") (pinfunction "5_5") (pintype "passive"))
      (node (ref "ADCA") (pin "11") (pinfunction "11_11") (pintype "passive"))
      (node (ref "ADCB") (pin "11") (pinfunction "11_11") (pintype "passive"))
      (node (ref "ADC_I2C") (pin "10") (pinfunction "10_10") (pintype "passive"))
      (node (ref "ADC_I2C") (pin "9") (pinfunction "9_9") (pintype "passive"))
      (node (ref "C1") (pin "+") (pinfunction "+_+") (pintype "passive"))
      (node (ref "C11") (pin "1") (pinfunction "1_1") (pintype "passive"))
      (node (ref "C12") (pin "1") (pinfunction "1_1") (pintype "passive"))
      (node (ref "C14") (pin "1") (pinfunction "1_1") (pintype "passive"))
      (node (ref "C2") (pin "1") (pinfunction "1_1") (pintype "passive"))
      (node (ref "C20") (pin "1") (pinfunction "1_1") (pintype "passive"))
      (node (ref "C35") (pin "1") (pinfunction "1_1") (pintype "passive"))
      (node (ref "C36") (pin "1") (pinfunction "1_1") (pintype "passive"))
      (node (ref "C38") (pin "1") (pinfunction "1_1") (pintype "passive"))
      (node (ref "C39") (pin "1") (pinfunction "1_1") (pintype "passive"))
      (node (ref "C6") (pin "1") (pinfunction "1_1") (pintype "passive"))
      (node (ref "CAN") (pin "1") (pinfunction "1_1") (pintype "passive"))
      (node (ref "CAN") (pin "6") (pinfunction "6_6") (pintype "passive"))
      (node (ref "PINS") (pin "11") (pinfunction "11_11") (pintype "passive"))
      (node (ref "R2") (pin "1") (pinfunction "1_1") (pintype "passive"))
      (node (ref "R26") (pin "2") (pinfunction "2_2") (pintype "passive"))
      (node (ref "R27") (pin "2") (pinfunction "2_2") (pintype "passive"))
      (node (ref "R28") (pin "2") (pinfunction "2_2") (pintype "passive"))
      (node (ref "R29") (pin "1") (pinfunction "1_1") (pintype "passive"))
      (node (ref "R3") (pin "2") (pinfunction "2_2") (pintype "passive"))
      (node (ref "R6") (pin "1") (pinfunction "1_1") (pintype "passive"))
      (node (ref "R7") (pin "1") (pinfunction "1_1") (pintype "passive"))
      (node (ref "SV12") (pin "2") (pinfunction "2_2") (pintype "passive"))
      (node (ref "SV13") (pin "2") (pinfunction "2_2") (pintype "passive"))
      (node (ref "SV14") (pin "2") (pinfunction "2_2") (pintype "passive"))
      (node (ref "SV15") (pin "2") (pinfunction "2_2") (pintype "passive"))
      (node (ref "SV19") (pin "6") (pinfunction "6_6") (pintype "passive"))
      (node (ref "SV6") (pin "6") (pinfunction "6_6") (pintype "passive"))
      (node (ref "U1") (pin "2") (pinfunction "OUT_2") (pintype "bidirectional"))
      (node (ref "U1") (pin "4") (pinfunction "OUT_4") (pintype "bidirectional"))
      (node (ref "U16") (pin "P$4") (pinfunction "+V_P$4") (pintype "bidirectional"))
      (node (ref "U2") (pin "16") (pinfunction "VCC_16") (pintype "bidirectional"))
      (node (ref "U3") (pin "22") (pinfunction "VDDA_22") (pintype "bidirectional"))
      (node (ref "U3") (pin "4") (pinfunction "VDDIO_4") (pintype "bidirectional"))
      (node (ref "U4") (pin "16") (pinfunction "VCC_16") (pintype "bidirectional"))
    )
    (net (code "2") (name "+5V") (class "Default")
      (node (ref "ADCA") (pin "2") (pinfunction "2_2") (pintype "passive"))
      (node (ref "ADCB") (pin "2") (pinfunction "2_2") (pintype "passive"))
      (node (ref "C21") (pin "1") (pinfunction "1_1") (pintype "passive"))
      (node (ref "C22") (pin "1") (pinfunction "1_1") (pintype "passive"))
      (node (ref "C23") (pin "1") (pinfunction "1_1") (pintype "passive"))
      (node (ref "C3") (pin "1") (pinfunction "1_1") (pintype "passive"))
      (node (ref "C30") (pin "1") (pinfunction "1_1") (pintype "passive"))
      (node (ref "C31") (pin "1") (pinfunction "1_1") (pintype "passive"))
      (node (ref "C32") (pin "1") (pinfunction "1_1") (pintype "passive"))
      (node (ref "C33") (pin "1") (pinfunction "1_1") (pintype "passive"))
      (node (ref "C34") (pin "1") (pinfunction "1_1") (pintype "passive"))
      (node (ref "C37") (pin "1") (pinfunction "1_1") (pintype "passive"))
      (node (ref "C4") (pin "1") (pinfunction "1_1") (pintype "passive"))
      (node (ref "C41") (pin "1") (pinfunction "1_1") (pintype "passive"))
      (node (ref "C42") (pin "1") (pinfunction "1_1") (pintype "passive"))
      (node (ref "C43") (pin "1") (pinfunction "1_1") (pintype "passive"))
      (node (ref "C46") (pin "1") (pinfunction "1_1") (pintype "passive"))
      (node (ref "C5") (pin "1") (pinfunction "1_1") (pintype "passive"))
      (node (ref "IC1") (pin "20") (pinfunction "VCC_20") (pintype "power_in"))
      (node (ref "IC2") (pin "24") (pinfunction "VCC_24") (pintype "power_in"))
      (node (ref "IC3") (pin "20") (pinfunction "VCC_20") (pintype "power_in"))
      (node (ref "J4") (pin "1") (pinfunction "1_1") (pintype "passive"))
      (node (ref "J7") (pin "P$77") (pinfunction "+5VIN_P$77") (pintype "bidirectional"))
      (node (ref "J7") (pin "P$82") (pinfunction "+5VIN_P$82") (pintype "bidirectional"))
      (node (ref "J7") (pin "P$87") (pinfunction "+5VIN_P$87") (pintype "bidirectional"))
      (node (ref "J7") (pin "P$92") (pinfunction "+5VIN_P$92") (pintype "bidirectional"))
      (node (ref "J7") (pin "P$96") (pinfunction "+5VIN_P$96") (pintype "bidirectional"))
      (node (ref "PINS") (pin "12") (pinfunction "12_12") (pintype "passive"))
      (node (ref "QG1") (pin "14") (pinfunction "VCC_14") (pintype "power_in"))
      (node (ref "R18") (pin "1") (pinfunction "1_1") (pintype "passive"))
      (node (ref "R20") (pin "1") (pinfunction "1_1") (pintype "passive"))
      (node (ref "R22") (pin "1") (pinfunction "1_1") (pintype "passive"))
      (node (ref "R24") (pin "1") (pinfunction "1_1") (pintype "passive"))
      (node (ref "R33") (pin "2") (pinfunction "2_2") (pintype "passive"))
      (node (ref "R35") (pin "2") (pinfunction "2_2") (pintype "passive"))
      (node (ref "R36") (pin "2") (pinfunction "2_2") (pintype "passive"))
      (node (ref "R37") (pin "2") (pinfunction "2_2") (pintype "passive"))
      (node (ref "R38") (pin "2") (pinfunction "2_2") (pintype "passive"))
      (node (ref "R8") (pin "1") (pinfunction "1_1") (pintype "passive"))
      (node (ref "SPI") (pin "1") (pinfunction "1_1") (pintype "passive"))
      (node (ref "SPI") (pin "8") (pinfunction "8_8") (pintype "passive"))
      (node (ref "SV28") (pin "7") (pinfunction "7_7") (pintype "passive"))
      (node (ref "SV28") (pin "8") (pinfunction "8_8") (pintype "passive"))
      (node (ref "U1") (pin "3") (pinfunction "IN_3") (pintype "bidirectional"))
      (node (ref "U10") (pin "14") (pinfunction "VDD_14") (pintype "bidirectional"))
      (node (ref "U12") (pin "14") (pinfunction "VDD_14") (pintype "bidirectional"))
      (node (ref "U13") (pin "14") (pinfunction "VDD_14") (pintype "bidirectional"))
      (node (ref "U14") (pin "14") (pinfunction "VDD_14") (pintype "bidirectional"))
      (node (ref "U7") (pin "14") (pinfunction "VDD_14") (pintype "bidirectional"))
      (node (ref "U8") (pin "14") (pinfunction "VDD_14") (pintype "bidirectional"))
      (node (ref "U9") (pin "14") (pinfunction "VDD_14") (pintype "bidirectional"))
      (node (ref "X4") (pin "10") (pinfunction "10_10") (pintype "passive"))
      (node (ref "X4") (pin "3") (pinfunction "3_3") (pintype "passive"))
      (node (ref "X4") (pin "6") (pinfunction "6_6") (pintype "passive"))
    )
    (net (code "3") (name "28027_ADCA2") (class "Default")
      (node (ref "P_LED3") (pin "K") (pinfunction "C_K") (pintype "passive"))
      (node (ref "U3") (pin "20") (pinfunction "ADCINA2/AIO2_20") (pintype "bidirectional"))
    )
    (net (code "4") (name "28027_ADCB2") (class "Default")
      (node (ref "P_LED2") (pin "K") (pinfunction "C_K") (pintype "passive"))
      (node (ref "U3") (pin "24") (pinfunction "ADCINB2/AIO10_24") (pintype "bidirectional"))
    )
    (net (code "5") (name "28027_BREAK") (class "Default")
      (node (ref "BREAK_CTRL") (pin "3") (pinfunction "3_3") (pintype "passive"))
      (node (ref "U3") (pin "26") (pinfunction "ADCINB6/AIO14_26") (pintype "bidirectional"))
    )
    (net (code "6") (name "28027_DIR1") (class "Default")
      (node (ref "28027_DIR") (pin "1") (pinfunction "1_1") (pintype "passive"))
      (node (ref "U3") (pin "9") (pinfunction "GPIO6/EPWM4A_9") (pintype "bidirectional"))
    )
    (net (code "7") (name "28027_DIR2") (class "Default")
      (node (ref "28027_DIR") (pin "2") (pinfunction "2_2") (pintype "passive"))
      (node (ref "U3") (pin "10") (pinfunction "GPIO7/EPWM4B_10") (pintype "bidirectional"))
    )
    (net (code "8") (name "28027_DIR3") (class "Default")
      (node (ref "28027_DIR") (pin "3") (pinfunction "3_3") (pintype "passive"))
      (node (ref "U3") (pin "13") (pinfunction "GPIO12/SCITXDA_13") (pintype "bidirectional"))
    )
    (net (code "9") (name "28027_DIR4") (class "Default")
      (node (ref "28027_DIR") (pin "4") (pinfunction "4_4") (pintype "passive"))
      (node (ref "U3") (pin "19") (pinfunction "ADCINA4/AIO4_19") (pintype "bidirectional"))
    )
    (net (code "10") (name "28027_DIR5") (class "Default")
      (node (ref "28027_DIR") (pin "5") (pinfunction "5_5") (pintype "passive"))
      (node (ref "U3") (pin "18") (pinfunction "ADCINA6/AIO6_18") (pintype "bidirectional"))
    )
    (net (code "11") (name "28027_DIR6") (class "Default")
      (node (ref "28027_DIR") (pin "6") (pinfunction "6_6") (pintype "passive"))
      (node (ref "U3") (pin "25") (pinfunction "ADCINB4/AIO12_25") (pintype "bidirectional"))
    )
    (net (code "12") (name "28027_PWM1A") (class "Default")
      (node (ref "28027_PWM") (pin "1") (pinfunction "1_1") (pintype "passive"))
      (node (ref "U3") (pin "37") (pinfunction "GPIO0/EPWM1A_37") (pintype "bidirectional"))
    )
    (net (code "13") (name "28027_PWM1B") (class "Default")
      (node (ref "28027_PWM") (pin "2") (pinfunction "2_2") (pintype "passive"))
      (node (ref "U3") (pin "36") (pinfunction "GPIO1/EPWM1B_36") (pintype "bidirectional"))
    )
    (net (code "14") (name "28027_PWM2A") (class "Default")
      (node (ref "28027_PWM") (pin "3") (pinfunction "3_3") (pintype "passive"))
      (node (ref "U3") (pin "5") (pinfunction "GPIO2/EPWM2A_5") (pintype "bidirectional"))
    )
    (net (code "15") (name "28027_PWM2B") (class "Default")
      (node (ref "28027_PWM") (pin "4") (pinfunction "4_4") (pintype "passive"))
      (node (ref "U3") (pin "6") (pinfunction "GPIO3/EPWM2B_6") (pintype "bidirectional"))
    )
    (net (code "16") (name "28027_PWM3A") (class "Default")
      (node (ref "28027_PWM") (pin "5") (pinfunction "5_5") (pintype "passive"))
      (node (ref "U3") (pin "7") (pinfunction "GPIO4/EPWM3A_7") (pintype "bidirectional"))
    )
    (net (code "17") (name "28027_PWM3B") (class "Default")
      (node (ref "28027_PWM") (pin "6") (pinfunction "6_6") (pintype "passive"))
      (node (ref "U3") (pin "8") (pinfunction "GPIO5/EPWM3B_8") (pintype "bidirectional"))
    )
    (net (code "18") (name "28027_SCL") (class "Default")
      (node (ref "ADC_I2C") (pin "7") (pinfunction "7_7") (pintype "passive"))
      (node (ref "R6") (pin "2") (pinfunction "2_2") (pintype "passive"))
      (node (ref "U3") (pin "15") (pinfunction "GPIO29/SCITXDA_15") (pintype "bidirectional"))
    )
    (net (code "19") (name "28027_SDA") (class "Default")
      (node (ref "ADC_I2C") (pin "5") (pinfunction "5_5") (pintype "passive"))
      (node (ref "R7") (pin "2") (pinfunction "2_2") (pintype "passive"))
      (node (ref "U3") (pin "14") (pinfunction "GPIO28/SCIRXDA_14") (pintype "bidirectional"))
    )
    (net (code "20") (name "28027_TCK") (class "Default")
      (node (ref "28027_JTAG") (pin "11") (pinfunction "11_11") (pintype "passive"))
      (node (ref "28027_JTAG") (pin "9") (pinfunction "9_9") (pintype "passive"))
      (node (ref "U3") (pin "31") (pinfunction "GPIO38/XCLKIN(TCK)_31") (pintype "bidirectional"))
    )
    (net (code "21") (name "28027_TDI") (class "Default")
      (node (ref "28027_JTAG") (pin "3") (pinfunction "3_3") (pintype "passive"))
      (node (ref "U3") (pin "28") (pinfunction "GPIO35(TDI)_28") (pintype "bidirectional"))
    )
    (net (code "22") (name "28027_TDO") (class "Default")
      (node (ref "28027_JTAG") (pin "7") (pinfunction "7_7") (pintype "passive"))
      (node (ref "R2") (pin "2") (pinfunction "2_2") (pintype "passive"))
      (node (ref "U3") (pin "30") (pinfunction "GPIO37(TDO)_30") (pintype "bidirectional"))
    )
    (net (code "23") (name "28027_TMS") (class "Default")
      (node (ref "28027_JTAG") (pin "1") (pinfunction "1_1") (pintype "passive"))
      (node (ref "U3") (pin "29") (pinfunction "GPIO36(TMS)_29") (pintype "bidirectional"))
    )
    (net (code "24") (name "28027_TRSTN") (class "Default")
      (node (ref "28027_JTAG") (pin "2") (pinfunction "2_2") (pintype "passive"))
      (node (ref "R1") (pin "1") (pinfunction "1_1") (pintype "passive"))
      (node (ref "U3") (pin "16") (pinfunction "/TRST_16") (pintype "bidirectional"))
    )
    (net (code "25") (name "28335_BREAK") (class "Default")
      (node (ref "BREAK_CTRL") (pin "1") (pinfunction "1_1") (pintype "passive"))
      (node (ref "J7") (pin "P$68") (pinfunction "GPIO59_MFSRA_XD20_P$68") (pintype "bidirectional"))
    )
    (net (code "26") (name "28335_EMU0") (class "Default")
      (node (ref "28335_JTAG") (pin "13") (pinfunction "13_13") (pintype "passive"))
      (node (ref "J7") (pin "P$100") (pinfunction "EMU0_P$100") (pintype "bidirectional"))
    )
    (net (code "27") (name "28335_EMU1") (class "Default")
      (node (ref "28335_JTAG") (pin "14") (pinfunction "14_14") (pintype "passive"))
      (node (ref "J7") (pin "P$50") (pinfunction "EMU1_P$50") (pintype "bidirectional"))
    )
    (net (code "28") (name "28335_GPIO16") (class "Default")
      (node (ref "IC2") (pin "19") (pinfunction "B3_19") (pintype "bidirectional"))
      (node (ref "J7") (pin "P$38") (pinfunction "GPIO16_SPISIMOA_CANTXB_TZ5_P$38") (pintype "bidirectional"))
      (node (ref "SPI") (pin "5") (pinfunction "5_5") (pintype "passive"))
      (node (ref "U3") (pin "35") (pinfunction "GPIO16/SPISIMOA_35") (pintype "bidirectional"))
    )
    (net (code "29") (name "28335_GPIO17") (class "Default")
      (node (ref "IC2") (pin "21") (pinfunction "B4_21") (pintype "bidirectional"))
      (node (ref "J7") (pin "P$88") (pinfunction "GPIO17_SPISOMIA_CANRXB_TZ6_P$88") (pintype "bidirectional"))
      (node (ref "SPI") (pin "3") (pinfunction "3_3") (pintype "passive"))
      (node (ref "U3") (pin "34") (pinfunction "GPIO17/SPISOMIA_34") (pintype "bidirectional"))
    )
    (net (code "30") (name "28335_GPIO18") (class "Default")
      (node (ref "IC2") (pin "23") (pinfunction "B5_23") (pintype "bidirectional"))
      (node (ref "J7") (pin "P$39") (pinfunction "GPIO18_SPICLKA_SCITXB_P$39") (pintype "bidirectional"))
      (node (ref "SPI") (pin "4") (pinfunction "4_4") (pintype "passive"))
      (node (ref "U3") (pin "32") (pinfunction "GPIO18/SPICLKA/SCITXDA_32") (pintype "bidirectional"))
    )
    (net (code "31") (name "28335_GPIO34") (class "Default")
      (node (ref "J7") (pin "P$46") (pinfunction "GPIO34_ECAP1_XREADY_P$46") (pintype "bidirectional"))
    )
    (net (code "32") (name "28335_GPIO85") (class "Default")
      (node (ref "J7") (pin "P$81") (pinfunction "GPIO85_P$81") (pintype "bidirectional"))
      (node (ref "SPI") (pin "6") (pinfunction "6_6") (pintype "passive"))
      (node (ref "U3") (pin "33") (pinfunction "GPIO19//SPISTEA/SCIRXDA_33") (pintype "bidirectional"))
    )
    (net (code "33") (name "28335_TCK") (class "Default")
      (node (ref "28335_JTAG") (pin "11") (pinfunction "11_11") (pintype "passive"))
      (node (ref "28335_JTAG") (pin "9") (pinfunction "9_9") (pintype "passive"))
      (node (ref "J7") (pin "P$48") (pinfunction "TCK_P$48") (pintype "bidirectional"))
    )
    (net (code "34") (name "28335_TDI") (class "Default")
      (node (ref "28335_JTAG") (pin "3") (pinfunction "3_3") (pintype "passive"))
      (node (ref "J7") (pin "P$97") (pinfunction "TDI_P$97") (pintype "bidirectional"))
    )
    (net (code "35") (name "28335_TDO") (class "Default")
      (node (ref "28335_JTAG") (pin "7") (pinfunction "7_7") (pintype "passive"))
      (node (ref "J7") (pin "P$98") (pinfunction "TDO_P$98") (pintype "bidirectional"))
    )
    (net (code "36") (name "28335_TMS") (class "Default")
      (node (ref "28335_JTAG") (pin "1") (pinfunction "1_1") (pintype "passive"))
      (node (ref "J7") (pin "P$49") (pinfunction "TMS_P$49") (pintype "bidirectional"))
    )
    (net (code "37") (name "28335_TRSTN") (class "Default")
      (node (ref "28335_JTAG") (pin "2") (pinfunction "2_2") (pintype "passive"))
      (node (ref "J7") (pin "P$99") (pinfunction "TRSTN_P$99") (pintype "bidirectional"))
    )
    (net (code "38") (name "ADCA0") (class "Default")
      (node (ref "ADCA") (pin "10") (pinfunction "10_10") (pintype "passive"))
      (node (ref "J7") (pin "P$57") (pinfunction "ADCIN_A0_P$57") (pintype "bidirectional"))
    )
    (net (code "39") (name "ADCA1") (class "Default")
      (node (ref "ADCA") (pin "9") (pinfunction "9_9") (pintype "passive"))
      (node (ref "J7") (pin "P$59") (pinfunction "ADCIN_A1_P$59") (pintype "bidirectional"))
    )
    (net (code "40") (name "ADCA2") (class "Default")
      (node (ref "ADCA") (pin "8") (pinfunction "8_8") (pintype "passive"))
      (node (ref "J7") (pin "P$61") (pinfunction "ADCIN_A2_P$61") (pintype "bidirectional"))
    )
    (net (code "41") (name "ADCA3") (class "Default")
      (node (ref "ADCA") (pin "7") (pinfunction "7_7") (pintype "passive"))
      (node (ref "J7") (pin "P$63") (pinfunction "ADCIN_A3_P$63") (pintype "bidirectional"))
    )
    (net (code "42") (name "ADCA4") (class "Default")
      (node (ref "ADCA") (pin "6") (pinfunction "6_6") (pintype "passive"))
      (node (ref "J7") (pin "P$65") (pinfunction "ADCIN_A4_P$65") (pintype "bidirectional"))
    )
    (net (code "43") (name "ADCA5") (class "Default")
      (node (ref "ADCA") (pin "5") (pinfunction "5_5") (pintype "passive"))
      (node (ref "J7") (pin "P$67") (pinfunction "ADCIN_A5_P$67") (pintype "bidirectional"))
    )
    (net (code "44") (name "ADCA6") (class "Default")
      (node (ref "ADCA") (pin "4") (pinfunction "4_4") (pintype "passive"))
      (node (ref "J7") (pin "P$69") (pinfunction "ADCIN_A6_P$69") (pintype "bidirectional"))
    )
    (net (code "45") (name "ADCA7") (class "Default")
      (node (ref "ADCA") (pin "3") (pinfunction "3_3") (pintype "passive"))
      (node (ref "J7") (pin "P$71") (pinfunction "ADCIN_A7_P$71") (pintype "bidirectional"))
    )
    (net (code "46") (name "ADCB0") (class "Default")
      (node (ref "J7") (pin "P$7") (pinfunction "ADCIN_B0_P$7") (pintype "bidirectional"))
      (node (ref "U16") (pin "P$1") (pinfunction "OA_P$1") (pintype "bidirectional"))
      (node (ref "U16") (pin "P$2") (pinfunction "-INA_P$2") (pintype "bidirectional"))
    )
    (net (code "47") (name "ADCB0_5V") (class "Default")
      (node (ref "ADCB") (pin "10") (pinfunction "10_10") (pintype "passive"))
      (node (ref "R9") (pin "2") (pinfunction "2_2") (pintype "passive"))
    )
    (net (code "48") (name "ADCB1") (class "Default")
      (node (ref "J7") (pin "P$9") (pinfunction "ADCIN_B1_P$9") (pintype "bidirectional"))
      (node (ref "U16") (pin "P$6") (pinfunction "-INB_P$6") (pintype "bidirectional"))
      (node (ref "U16") (pin "P$7") (pinfunction "OB_P$7") (pintype "bidirectional"))
    )
    (net (code "49") (name "ADCB1_5V") (class "Default")
      (node (ref "ADCB") (pin "9") (pinfunction "9_9") (pintype "passive"))
      (node (ref "R11") (pin "2") (pinfunction "2_2") (pintype "passive"))
    )
    (net (code "50") (name "ADCB2") (class "Default")
      (node (ref "J7") (pin "P$11") (pinfunction "ADCIN_B2_P$11") (pintype "bidirectional"))
      (node (ref "U16") (pin "P$8") (pinfunction "OC_P$8") (pintype "bidirectional"))
      (node (ref "U16") (pin "P$9") (pinfunction "-INC_P$9") (pintype "bidirectional"))
    )
    (net (code "51") (name "ADCB2_5V") (class "Default")
      (node (ref "ADCB") (pin "8") (pinfunction "8_8") (pintype "passive"))
      (node (ref "R13") (pin "2") (pinfunction "2_2") (pintype "passive"))
    )
    (net (code "52") (name "ADCB3") (class "Default")
      (node (ref "J7") (pin "P$13") (pinfunction "ADCIN_B3_P$13") (pintype "bidirectional"))
      (node (ref "U16") (pin "P$13") (pinfunction "-IND_P$13") (pintype "bidirectional"))
      (node (ref "U16") (pin "P$14") (pinfunction "OD_P$14") (pintype "bidirectional"))
    )
    (net (code "53") (name "ADCB3_5V") (class "Default")
      (node (ref "ADCB") (pin "7") (pinfunction "7_7") (pintype "passive"))
      (node (ref "R15") (pin "2") (pinfunction "2_2") (pintype "passive"))
    )
    (net (code "54") (name "ADCB4") (class "Default")
      (node (ref "ADCB") (pin "6") (pinfunction "6_6") (pintype "passive"))
      (node (ref "J7") (pin "P$15") (pinfunction "ADCIN_B4_P$15") (pintype "bidirectional"))
    )
    (net (code "55") (name "ADCB5") (class "Default")
      (node (ref "ADCB") (pin "5") (pinfunction "5_5") (pintype "passive"))
      (node (ref "J7") (pin "P$17") (pinfunction "ADCIN_B5_P$17") (pintype "bidirectional"))
    )
    (net (code "56") (name "ADCB6") (class "Default")
      (node (ref "ADCB") (pin "4") (pinfunction "4_4") (pintype "passive"))
      (node (ref "J7") (pin "P$19") (pinfunction "ADCIN_B6_P$19") (pintype "bidirectional"))
    )
    (net (code "57") (name "ADCB7") (class "Default")
      (node (ref "ADCB") (pin "3") (pinfunction "3_3") (pintype "passive"))
      (node (ref "J7") (pin "P$21") (pinfunction "ADCIN_B7_P$21") (pintype "bidirectional"))
    )
    (net (code "58") (name "ADCINA0") (class "Default")
      (node (ref "ADC_I2C") (pin "8") (pinfunction "8_8") (pintype "passive"))
      (node (ref "U3") (pin "21") (pinfunction "ADCINA0/VREFHI_21") (pintype "bidirectional"))
    )
    (net (code "59") (name "AMP_CURRENT_1") (class "Default")
      (node (ref "AMP_1") (pin "S_4") (pinfunction "CURRENT_MONITOR_S_4") (pintype "bidirectional"))
      (node (ref "AMP_CURRENT") (pin "1") (pinfunction "1_1") (pintype "passive"))
      (node (ref "SV1") (pin "4") (pinfunction "CURRENT_MONITOR_4") (pintype "passive"))
    )
    (net (code "60") (name "AMP_CURRENT_2") (class "Default")
      (node (ref "AMP_2") (pin "S_4") (pinfunction "CURRENT_MONITOR_S_4") (pintype "bidirectional"))
      (node (ref "AMP_CURRENT") (pin "2") (pinfunction "2_2") (pintype "passive"))
      (node (ref "SV2") (pin "4") (pinfunction "CURRENT_MONITOR_4") (pintype "passive"))
    )
    (net (code "61") (name "AMP_CURRENT_3") (class "Default")
      (node (ref "AMP_3") (pin "S_4") (pinfunction "CURRENT_MONITOR_S_4") (pintype "bidirectional"))
      (node (ref "AMP_CURRENT") (pin "3") (pinfunction "3_3") (pintype "passive"))
      (node (ref "SV3") (pin "4") (pinfunction "CURRENT_MONITOR_4") (pintype "passive"))
    )
    (net (code "62") (name "AMP_CURRENT_4") (class "Default")
      (node (ref "AMP_4") (pin "S_4") (pinfunction "CURRENT_MONITOR_S_4") (pintype "bidirectional"))
      (node (ref "AMP_CURRENT") (pin "4") (pinfunction "4_4") (pintype "passive"))
      (node (ref "SV4") (pin "4") (pinfunction "CURRENT_MONITOR_4") (pintype "passive"))
    )
    (net (code "63") (name "AMP_CURRENT_5") (class "Default")
      (node (ref "AMP_5") (pin "S_4") (pinfunction "CURRENT_MONITOR_S_4") (pintype "bidirectional"))
      (node (ref "AMP_CURRENT") (pin "5") (pinfunction "5_5") (pintype "passive"))
      (node (ref "SV5") (pin "4") (pinfunction "CURRENT_MONITOR_4") (pintype "passive"))
    )
    (net (code "64") (name "BRAKE_GND_1") (class "Default")
      (node (ref "Q3") (pin "2") (pinfunction "C_2") (pintype "passive"))
      (node (ref "X4") (pin "15") (pinfunction "15_15") (pintype "passive"))
    )
    (net (code "65") (name "BRAKE_GND_2") (class "Default")
      (node (ref "Q4") (pin "2") (pinfunction "C_2") (pintype "passive"))
      (node (ref "X4") (pin "16") (pinfunction "16_16") (pintype "passive"))
    )
    (net (code "66") (name "BRAKE_PWR") (class "Default")
      (node (ref "BREAK_POWER") (pin "P$2") (pinfunction "P$2_P$2") (pintype "passive"))
      (node (ref "X4") (pin "13") (pinfunction "13_13") (pintype "passive"))
      (node (ref "X4") (pin "14") (pinfunction "14_14") (pintype "passive"))
    )
    (net (code "67") (name "CANRXA") (class "Default")
      (node (ref "CAN") (pin "4") (pinfunction "4_4") (pintype "passive"))
      (node (ref "J7") (pin "P$44") (pinfunction "GPIO30_CANRXA_P$44") (pintype "bidirectional"))
    )
    (net (code "68") (name "CANTXA") (class "Default")
      (node (ref "CAN") (pin "3") (pinfunction "3_3") (pintype "passive"))
      (node (ref "J7") (pin "P$94") (pinfunction "GPIO31_CANTXA_P$94") (pintype "bidirectional"))
    )
    (net (code "69") (name "ENC1A") (class "Default")
      (node (ref "28335_ENC") (pin "5") (pinfunction "5_5") (pintype "passive"))
      (node (ref "J7") (pin "P$40") (pinfunction "GPIO20_EQEPA1_MDXA_CANTXB_P$40") (pintype "bidirectional"))
    )
    (net (code "70") (name "ENC1B") (class "Default")
      (node (ref "28335_ENC") (pin "9") (pinfunction "9_9") (pintype "passive"))
      (node (ref "J7") (pin "P$90") (pinfunction "GPIO21_EQEPB1_MDRA_CANRXB_P$90") (pintype "bidirectional"))
    )
    (net (code "71") (name "ENC2A") (class "Default")
      (node (ref "28335_ENC") (pin "6") (pinfunction "6_6") (pintype "passive"))
      (node (ref "J7") (pin "P$35") (pinfunction "GPIO24_ECAP1_EQEPA2_MDXB_P$35") (pintype "bidirectional"))
    )
    (net (code "72") (name "ENC2B") (class "Default")
      (node (ref "28335_ENC") (pin "10") (pinfunction "10_10") (pintype "passive"))
      (node (ref "J7") (pin "P$85") (pinfunction "GPIO25_ECAP2_EQEPB2_MDRB_P$85") (pintype "bidirectional"))
    )
    (net (code "73") (name "FAULT_1") (class "Default")
      (node (ref "AMP_1") (pin "S_12") (pinfunction "FAULT_OUT_S_12") (pintype "bidirectional"))
      (node (ref "INHIBIT_LED") (pin "2") (pinfunction "2_2") (pintype "passive"))
      (node (ref "R8") (pin "2") (pinfunction "2_2") (pintype "passive"))
      (node (ref "SV1") (pin "12") (pinfunction "FAULT_OUT_12") (pintype "passive"))
    )
    (net (code "74") (name "FAULT_2") (class "Default")
      (node (ref "AMP_2") (pin "S_12") (pinfunction "FAULT_OUT_S_12") (pintype "bidirectional"))
      (node (ref "LED_5V1") (pin "A") (pinfunction "A_A") (pintype "passive"))
      (node (ref "R18") (pin "2") (pinfunction "2_2") (pintype "passive"))
      (node (ref "SV2") (pin "12") (pinfunction "FAULT_OUT_12") (pintype "passive"))
    )
    (net (code "75") (name "FAULT_3") (class "Default")
      (node (ref "AMP_3") (pin "S_12") (pinfunction "FAULT_OUT_S_12") (pintype "bidirectional"))
      (node (ref "LED_5V2") (pin "A") (pinfunction "A_A") (pintype "passive"))
      (node (ref "R20") (pin "2") (pinfunction "2_2") (pintype "passive"))
      (node (ref "SV3") (pin "12") (pinfunction "FAULT_OUT_12") (pintype "passive"))
    )
    (net (code "76") (name "FAULT_4") (class "Default")
      (node (ref "AMP_4") (pin "S_12") (pinfunction "FAULT_OUT_S_12") (pintype "bidirectional"))
      (node (ref "LED_5V5") (pin "A") (pinfunction "A_A") (pintype "passive"))
      (node (ref "R24") (pin "2") (pinfunction "2_2") (pintype "passive"))
      (node (ref "SV4") (pin "12") (pinfunction "FAULT_OUT_12") (pintype "passive"))
    )
    (net (code "77") (name "FAULT_5") (class "Default")
      (node (ref "AMP_5") (pin "S_12") (pinfunction "FAULT_OUT_S_12") (pintype "bidirectional"))
      (node (ref "LED_5V4") (pin "A") (pinfunction "A_A") (pintype "passive"))
      (node (ref "R22") (pin "2") (pinfunction "2_2") (pintype "passive"))
      (node (ref "SV5") (pin "12") (pinfunction "FAULT_OUT_12") (pintype "passive"))
    )
    (net (code "78") (name "GND") (class "Default")
      (node (ref "28027_JTAG") (pin "10") (pinfunction "10_10") (pintype "passive"))
      (node (ref "28027_JTAG") (pin "12") (pinfunction "12_12") (pintype "passive"))
      (node (ref "28027_JTAG") (pin "4") (pinfunction "4_4") (pintype "passive"))
      (node (ref "28027_JTAG") (pin "8") (pinfunction "8_8") (pintype "passive"))
      (node (ref "28335_ENC") (pin "1") (pinfunction "1_1") (pintype "passive"))
      (node (ref "28335_ENC") (pin "2") (pinfunction "2_2") (pintype "passive"))
      (node (ref "28335_JTAG") (pin "10") (pinfunction "10_10") (pintype "passive"))
      (node (ref "28335_JTAG") (pin "12") (pinfunction "12_12") (pintype "passive"))
      (node (ref "28335_JTAG") (pin "4") (pinfunction "4_4") (pintype "passive"))
      (node (ref "28335_JTAG") (pin "8") (pinfunction "8_8") (pintype "passive"))
      (node (ref "ADCA") (pin "1") (pinfunction "1_1") (pintype "passive"))
      (node (ref "ADCA") (pin "12") (pinfunction "12_12") (pintype "passive"))
      (node (ref "ADCB") (pin "1") (pinfunction "1_1") (pintype "passive"))
      (node (ref "ADCB") (pin "12") (pinfunction "12_12") (pintype "passive"))
      (node (ref "ADC_I2C") (pin "1") (pinfunction "1_1") (pintype "passive"))
      (node (ref "ADC_I2C") (pin "2") (pinfunction "2_2") (pintype "passive"))
      (node (ref "AMP_1") (pin "S_2") (pinfunction "SIGNAL_GND_1_S_2") (pintype "bidirectional"))
      (node (ref "AMP_1") (pin "S_7") (pinfunction "SIGNAL_GND_2_S_7") (pintype "bidirectional"))
      (node (ref "AMP_2") (pin "S_2") (pinfunction "SIGNAL_GND_1_S_2") (pintype "bidirectional"))
      (node (ref "AMP_2") (pin "S_7") (pinfunction "SIGNAL_GND_2_S_7") (pintype "bidirectional"))
      (node (ref "AMP_3") (pin "S_2") (pinfunction "SIGNAL_GND_1_S_2") (pintype "bidirectional"))
      (node (ref "AMP_3") (pin "S_7") (pinfunction "SIGNAL_GND_2_S_7") (pintype "bidirectional"))
      (node (ref "AMP_4") (pin "S_2") (pinfunction "SIGNAL_GND_1_S_2") (pintype "bidirectional"))
      (node (ref "AMP_4") (pin "S_7") (pinfunction "SIGNAL_GND_2_S_7") (pintype "bidirectional"))
      (node (ref "AMP_5") (pin "S_2") (pinfunction "SIGNAL_GND_1_S_2") (pintype "bidirectional"))
      (node (ref "AMP_5") (pin "S_7") (pinfunction "SIGNAL_GND_2_S_7") (pintype "bidirectional"))
      (node (ref "BREAK_POWER") (pin "P$1") (pinfunction "P$1_P$1") (pintype "passive"))
      (node (ref "C1") (pin "-") (pinfunction "-_-") (pintype "passive"))
      (node (ref "C10") (pin "2") (pinfunction "2_2") (pintype "passive"))
      (node (ref "C11") (pin "2") (pinfunction "2_2") (pintype "passive"))
      (node (ref "C12") (pin "2") (pinfunction "2_2") (pintype "passive"))
      (node (ref "C13") (pin "2") (pinfunction "2_2") (pintype "passive"))
      (node (ref "C14") (pin "2") (pinfunction "2_2") (pintype "passive"))
      (node (ref "C15") (pin "1") (pinfunction "1_1") (pintype "passive"))
      (node (ref "C18") (pin "2") (pinfunction "2_2") (pintype "passive"))
      (node (ref "C19") (pin "2") (pinfunction "2_2") (pintype "passive"))
      (node (ref "C2") (pin "2") (pinfunction "2_2") (pintype "passive"))
      (node (ref "C20") (pin "2") (pinfunction "2_2") (pintype "passive"))
      (node (ref "C21") (pin "2") (pinfunction "2_2") (pintype "passive"))
      (node (ref "C22") (pin "2") (pinfunction "2_2") (pintype "passive"))
      (node (ref "C23") (pin "2") (pinfunction "2_2") (pintype "passive"))
      (node (ref "C24") (pin "2") (pinfunction "2_2") (pintype "passive"))
      (node (ref "C25") (pin "2") (pinfunction "2_2") (pintype "passive"))
      (node (ref "C26") (pin "2") (pinfunction "2_2") (pintype "passive"))
      (node (ref "C27") (pin "2") (pinfunction "2_2") (pintype "passive"))
      (node (ref "C28") (pin "2") (pinfunction "2_2") (pintype "passive"))
      (node (ref "C29") (pin "2") (pinfunction "2_2") (pintype "passive"))
      (node (ref "C3") (pin "2") (pinfunction "2_2") (pintype "passive"))
      (node (ref "C30") (pin "2") (pinfunction "2_2") (pintype "passive"))
      (node (ref "C31") (pin "2") (pinfunction "2_2") (pintype "passive"))
      (node (ref "C32") (pin "2") (pinfunction "2_2") (pintype "passive"))
      (node (ref "C33") (pin "2") (pinfunction "2_2") (pintype "passive"))
      (node (ref "C34") (pin "2") (pinfunction "2_2") (pintype "passive"))
      (node (ref "C35") (pin "2") (pinfunction "2_2") (pintype "passive"))
      (node (ref "C36") (pin "2") (pinfunction "2_2") (pintype "passive"))
      (node (ref "C37") (pin "2") (pinfunction "2_2") (pintype "passive"))
      (node (ref "C38") (pin "2") (pinfunction "2_2") (pintype "passive"))
      (node (ref "C39") (pin "2") (pinfunction "2_2") (pintype "passive"))
      (node (ref "C4") (pin "2") (pinfunction "2_2") (pintype "passive"))
      (node (ref "C41") (pin "2") (pinfunction "2_2") (pintype "passive"))
      (node (ref "C42") (pin "2") (pinfunction "2_2") (pintype "passive"))
      (node (ref "C43") (pin "2") (pinfunction "2_2") (pintype "passive"))
      (node (ref "C46") (pin "2") (pinfunction "2_2") (pintype "passive"))
      (node (ref "C5") (pin "2") (pinfunction "2_2") (pintype "passive"))
      (node (ref "C6") (pin "2") (pinfunction "2_2") (pintype "passive"))
      (node (ref "C7") (pin "1") (pinfunction "1_1") (pintype "passive"))
      (node (ref "CAN") (pin "2") (pinfunction "2_2") (pintype "passive"))
      (node (ref "CAN") (pin "5") (pinfunction "5_5") (pintype "passive"))
      (node (ref "IC1") (pin "1") (pinfunction "G1_1") (pintype "input"))
      (node (ref "IC1") (pin "10") (pinfunction "GND_10") (pintype "power_in"))
      (node (ref "IC1") (pin "19") (pinfunction "G2_19") (pintype "input"))
      (node (ref "IC1") (pin "8") (pinfunction "A7_8") (pintype "input"))
      (node (ref "IC1") (pin "9") (pinfunction "A8_9") (pintype "input"))
      (node (ref "IC2") (pin "1") (pinfunction "G_1") (pintype "input"))
      (node (ref "IC2") (pin "12") (pinfunction "GND_12") (pintype "power_in"))
      (node (ref "IC2") (pin "13") (pinfunction "G_13") (pintype "input"))
      (node (ref "IC3") (pin "1") (pinfunction "G1_1") (pintype "input"))
      (node (ref "IC3") (pin "10") (pinfunction "GND_10") (pintype "power_in"))
      (node (ref "IC3") (pin "19") (pinfunction "G2_19") (pintype "input"))
      (node (ref "IC3") (pin "8") (pinfunction "A7_8") (pintype "input"))
      (node (ref "IC3") (pin "9") (pinfunction "A8_9") (pintype "input"))
      (node (ref "INHIBIT_SWITCH") (pin "1") (pinfunction "1_1") (pintype "passive"))
      (node (ref "J4") (pin "2") (pinfunction "2_2") (pintype "passive"))
      (node (ref "J4") (pin "3") (pinfunction "3_3") (pintype "passive"))
      (node (ref "J7") (pin "P$10") (pinfunction "GND_P$10") (pintype "bidirectional"))
      (node (ref "J7") (pin "P$12") (pinfunction "GND_P$12") (pintype "bidirectional"))
      (node (ref "J7") (pin "P$14") (pinfunction "GND_P$14") (pintype "bidirectional"))
      (node (ref "J7") (pin "P$27") (pinfunction "GND_P$27") (pintype "bidirectional"))
      (node (ref "J7") (pin "P$37") (pinfunction "GND_P$37") (pintype "bidirectional"))
      (node (ref "J7") (pin "P$47") (pinfunction "GND_P$47") (pintype "bidirectional"))
      (node (ref "J7") (pin "P$58") (pinfunction "GND_P$58") (pintype "bidirectional"))
      (node (ref "J7") (pin "P$60") (pinfunction "GND_P$60") (pintype "bidirectional"))
      (node (ref "J7") (pin "P$62") (pinfunction "GND_P$62") (pintype "bidirectional"))
      (node (ref "J7") (pin "P$64") (pinfunction "GND_P$64") (pintype "bidirectional"))
      (node (ref "J7") (pin "P$8") (pinfunction "GND_P$8") (pintype "bidirectional"))
      (node (ref "JOINT_INDEX") (pin "1") (pinfunction "1_1") (pintype "passive"))
      (node (ref "JOINT_INDEX") (pin "3") (pinfunction "3_3") (pintype "passive"))
      (node (ref "JOINT_INDEX") (pin "5") (pinfunction "5_5") (pintype "passive"))
      (node (ref "JOINT_INDEX") (pin "7") (pinfunction "7_7") (pintype "passive"))
      (node (ref "JOINT_INDEX") (pin "9") (pinfunction "9_9") (pintype "passive"))
      (node (ref "LED_5V") (pin "K") (pinfunction "C_K") (pintype "passive"))
      (node (ref "PINS") (pin "1") (pinfunction "1_1") (pintype "passive"))
      (node (ref "PINS") (pin "2") (pinfunction "2_2") (pintype "passive"))
      (node (ref "Q3") (pin "3") (pinfunction "E_3") (pintype "passive"))
      (node (ref "Q4") (pin "3") (pinfunction "E_3") (pintype "passive"))
      (node (ref "QG1") (pin "7") (pinfunction "GND_7") (pintype "power_in"))
      (node (ref "R1") (pin "2") (pinfunction "2_2") (pintype "passive"))
      (node (ref "R10") (pin "1") (pinfunction "1_1") (pintype "passive"))
      (node (ref "R12") (pin "1") (pinfunction "1_1") (pintype "passive"))
      (node (ref "R14") (pin "1") (pinfunction "1_1") (pintype "passive"))
      (node (ref "R16") (pin "1") (pinfunction "1_1") (pintype "passive"))
      (node (ref "R17") (pin "2") (pinfunction "2_2") (pintype "passive"))
      (node (ref "R19") (pin "2") (pinfunction "2_2") (pintype "passive"))
      (node (ref "R21") (pin "2") (pinfunction "2_2") (pintype "passive"))
      (node (ref "R23") (pin "2") (pinfunction "2_2") (pintype "passive"))
      (node (ref "R25") (pin "2") (pinfunction "2_2") (pintype "passive"))
      (node (ref "SPI") (pin "2") (pinfunction "2_2") (pintype "passive"))
      (node (ref "SPI") (pin "7") (pinfunction "7_7") (pintype "passive"))
      (node (ref "SV1") (pin "2") (pinfunction "SIGNAL_GND_1_2") (pintype "passive"))
      (node (ref "SV1") (pin "7") (pinfunction "SIGNAL_GND_2_7") (pintype "passive"))
      (node (ref "SV10") (pin "1") (pinfunction "1_1") (pintype "passive"))
      (node (ref "SV11") (pin "1") (pinfunction "1_1") (pintype "passive"))
      (node (ref "SV12") (pin "1") (pinfunction "1_1") (pintype "passive"))
      (node (ref "SV13") (pin "1") (pinfunction "1_1") (pintype "passive"))
      (node (ref "SV14") (pin "1") (pinfunction "1_1") (pintype "passive"))
      (node (ref "SV15") (pin "1") (pinfunction "1_1") (pintype "passive"))
      (node (ref "SV16") (pin "1") (pinfunction "1_1") (pintype "passive"))
      (node (ref "SV17") (pin "1") (pinfunction "1_1") (pintype "passive"))
      (node (ref "SV18") (pin "1") (pinfunction "1_1") (pintype "passive"))
      (node (ref "SV19") (pin "5") (pinfunction "5_5") (pintype "passive"))
      (node (ref "SV19") (pin "8") (pinfunction "8_8") (pintype "passive"))
      (node (ref "SV2") (pin "2") (pinfunction "SIGNAL_GND_1_2") (pintype "passive"))
      (node (ref "SV2") (pin "7") (pinfunction "SIGNAL_GND_2_7") (pintype "passive"))
      (node (ref "SV20") (pin "5") (pinfunction "5_5") (pintype "passive"))
      (node (ref "SV20") (pin "6") (pinfunction "6_6") (pintype "passive"))
      (node (ref "SV28") (pin "1") (pinfunction "1_1") (pintype "passive"))
      (node (ref "SV28") (pin "2") (pinfunction "2_2") (pintype "passive"))
      (node (ref "SV3") (pin "2") (pinfunction "SIGNAL_GND_1_2") (pintype "passive"))
      (node (ref "SV3") (pin "7") (pinfunction "SIGNAL_GND_2_7") (pintype "passive"))
      (node (ref "SV4") (pin "2") (pinfunction "SIGNAL_GND_1_2") (pintype "passive"))
      (node (ref "SV4") (pin "7") (pinfunction "SIGNAL_GND_2_7") (pintype "passive"))
      (node (ref "SV5") (pin "2") (pinfunction "SIGNAL_GND_1_2") (pintype "passive"))
      (node (ref "SV5") (pin "7") (pinfunction "SIGNAL_GND_2_7") (pintype "passive"))
      (node (ref "SV6") (pin "5") (pinfunction "5_5") (pintype "passive"))
      (node (ref "SV6") (pin "8") (pinfunction "8_8") (pintype "passive"))
      (node (ref "U1") (pin "1") (pinfunction "ADJ_1") (pintype "bidirectional"))
      (node (ref "U10") (pin "3") (pinfunction "GND_3") (pintype "bidirectional"))
      (node (ref "U12") (pin "3") (pinfunction "GND_3") (pintype "bidirectional"))
      (node (ref "U13") (pin "3") (pinfunction "GND_3") (pintype "bidirectional"))
      (node (ref "U14") (pin "3") (pinfunction "GND_3") (pintype "bidirectional"))
      (node (ref "U16") (pin "P$11") (pinfunction "-V_P$11") (pintype "bidirectional"))
      (node (ref "U2") (pin "15") (pinfunction "GND_15") (pintype "bidirectional"))
      (node (ref "U3") (pin "12") (pinfunction "VSS2_12") (pintype "bidirectional"))
      (node (ref "U3") (pin "2") (pinfunction "VSS_2") (pintype "bidirectional"))
      (node (ref "U3") (pin "23") (pinfunction "VSSA/VREFLO_23") (pintype "bidirectional"))
      (node (ref "U3") (pin "3") (pinfunction "/VREGENZ_3") (pintype "bidirectional"))
      (node (ref "U4") (pin "15") (pinfunction "GND_15") (pintype "bidirectional"))
      (node (ref "U6") (pin "18") (pinfunction "GND2_18") (pintype "power_in"))
      (node (ref "U6") (pin "21") (pinfunction "GND3_21") (pintype "power_in"))
      (node (ref "U6") (pin "25") (pinfunction "AGND_25") (pintype "power_in"))
      (node (ref "U6") (pin "26") (pinfunction "TEST_26") (pintype "input"))
      (node (ref "U6") (pin "7") (pinfunction "GND1_7") (pintype "power_in"))
      (node (ref "U7") (pin "3") (pinfunction "GND_3") (pintype "bidirectional"))
      (node (ref "U8") (pin "3") (pinfunction "GND_3") (pintype "bidirectional"))
      (node (ref "U9") (pin "3") (pinfunction "GND_3") (pintype "bidirectional"))
      (node (ref "UART_SENSOR") (pin "1") (pinfunction "1_1") (pintype "passive"))
      (node (ref "USB_PWR1") (pin "K") (pinfunction "C_K") (pintype "passive"))
      (node (ref "X2") (pin "GND") (pinfunction "GND_GND") (pintype "bidirectional"))
      (node (ref "X4") (pin "12") (pinfunction "12_12") (pintype "passive"))
      (node (ref "X4") (pin "5") (pinfunction "5_5") (pintype "passive"))
      (node (ref "X4") (pin "8") (pinfunction "8_8") (pintype "passive"))
      (node (ref "X4") (pin "G1") (pinfunction "G1_G1") (pintype "passive"))
      (node (ref "X4") (pin "G2") (pinfunction "G2_G2") (pintype "passive"))
    )
    (net (code "79") (name "GPIO0") (class "Default")
      (node (ref "28335_PWM") (pin "1") (pinfunction "1_1") (pintype "passive"))
      (node (ref "J7") (pin "P$23") (pinfunction "GPIO0_EPWM1A_P$23") (pintype "bidirectional"))
    )
    (net (code "80") (name "GPIO1") (class "Default")
      (node (ref "28335_DIR") (pin "1") (pinfunction "1_1") (pintype "passive"))
      (node (ref "J7") (pin "P$73") (pinfunction "GPIO1_EPWM1B_MFSRB_P$73") (pintype "bidirectional"))
    )
    (net (code "81") (name "GPIO2") (class "Default")
      (node (ref "28335_PWM") (pin "2") (pinfunction "2_2") (pintype "passive"))
      (node (ref "J7") (pin "P$24") (pinfunction "GPIO2_EPWM2A_P$24") (pintype "bidirectional"))
    )
    (net (code "82") (name "GPIO3") (class "Default")
      (node (ref "28335_DIR") (pin "2") (pinfunction "2_2") (pintype "passive"))
      (node (ref "J7") (pin "P$74") (pinfunction "GPIO3_EPWM2B_MCLKRB_P$74") (pintype "bidirectional"))
    )
    (net (code "83") (name "GPIO4") (class "Default")
      (node (ref "28335_PWM") (pin "3") (pinfunction "3_3") (pintype "passive"))
      (node (ref "J7") (pin "P$25") (pinfunction "GPIO4_EPWM3A_P$25") (pintype "bidirectional"))
    )
    (net (code "84") (name "GPIO5") (class "Default")
      (node (ref "28335_DIR") (pin "3") (pinfunction "3_3") (pintype "passive"))
      (node (ref "J7") (pin "P$75") (pinfunction "GPIO5_EPWM3B_MFSRA_ECAP1_P$75") (pintype "bidirectional"))
    )
    (net (code "85") (name "GPIO6") (class "Default")
      (node (ref "28335_PWM") (pin "4") (pinfunction "4_4") (pintype "passive"))
      (node (ref "J7") (pin "P$26") (pinfunction "GPIO6_EPWM4A_SYNCI_SYNCO_P$26") (pintype "bidirectional"))
    )
    (net (code "86") (name "GPIO7") (class "Default")
      (node (ref "28335_DIR") (pin "4") (pinfunction "4_4") (pintype "passive"))
      (node (ref "J7") (pin "P$76") (pinfunction "GPIO7_EPWM4B_MCLKRA_ECAP2_P$76") (pintype "bidirectional"))
    )
    (net (code "87") (name "GPIO8") (class "Default")
      (node (ref "28335_PWM") (pin "5") (pinfunction "5_5") (pintype "passive"))
      (node (ref "J7") (pin "P$28") (pinfunction "GPIO8_EPWM5A_CANTXB_ADCSOCA_P$28") (pintype "bidirectional"))
    )
    (net (code "88") (name "GPIO9") (class "Default")
      (node (ref "IC2") (pin "10") (pinfunction "B5_10") (pintype "bidirectional"))
      (node (ref "J7") (pin "P$78") (pinfunction "GPIO9_EPWM5B_SCITXB_ECAP3_P$78") (pintype "bidirectional"))
    )
    (net (code "89") (name "GPIO10") (class "Default")
      (node (ref "IC2") (pin "8") (pinfunction "B4_8") (pintype "bidirectional"))
      (node (ref "J7") (pin "P$29") (pinfunction "GPIO10_EPWM6A_CANRXB_ADCSOCB_P$29") (pintype "bidirectional"))
    )
    (net (code "90") (name "GPIO11") (class "Default")
      (node (ref "IC2") (pin "6") (pinfunction "B3_6") (pintype "bidirectional"))
      (node (ref "J7") (pin "P$79") (pinfunction "GPIO11_EPWM6B_SCIRXB_ECAP4_P$79") (pintype "bidirectional"))
    )
    (net (code "91") (name "GPIO12") (class "Default")
      (node (ref "D_LED3") (pin "K") (pinfunction "C_K") (pintype "passive"))
      (node (ref "J7") (pin "P$33") (pinfunction "GPIO12_TZ\\~{_CANTXB_MDXB}_P$33") (pintype "bidirectional"))
    )
    (net (code "92") (name "GPIO13") (class "Default")
      (node (ref "D_LED2") (pin "K") (pinfunction "C_K") (pintype "passive"))
      (node (ref "J7") (pin "P$83") (pinfunction "GPIO13_TZ2_CANRXB_MDRB_P$83") (pintype "bidirectional"))
    )
    (net (code "93") (name "GPIO14") (class "Default")
      (node (ref "J7") (pin "P$84") (pinfunction "GPIO14_TZ3_SCITXB_MCLKXB_P$84") (pintype "bidirectional"))
      (node (ref "U4") (pin "11") (pinfunction "DIN1_11") (pintype "bidirectional"))
    )
    (net (code "94") (name "GPIO15") (class "Default")
      (node (ref "J7") (pin "P$34") (pinfunction "GPIO15_TZ4_SCIRXB_MFSXB_P$34") (pintype "bidirectional"))
      (node (ref "U4") (pin "12") (pinfunction "ROUT1_12") (pintype "bidirectional"))
    )
    (net (code "95") (name "GPIO19") (class "Default")
      (node (ref "28335_DIR") (pin "5") (pinfunction "5_5") (pintype "passive"))
      (node (ref "J7") (pin "P$89") (pinfunction "GPIO19_SPISTEA_SCIRXB_P$89") (pintype "bidirectional"))
    )
    (net (code "96") (name "GPIO22") (class "Default")
      (node (ref "IC2") (pin "4") (pinfunction "B2_4") (pintype "bidirectional"))
      (node (ref "J7") (pin "P$41") (pinfunction "GPIO22_EQEPS1_MCLKXA_SCITXB_P$41") (pintype "bidirectional"))
    )
    (net (code "97") (name "GPIO23") (class "Default")
      (node (ref "IC2") (pin "2") (pinfunction "B1_2") (pintype "bidirectional"))
      (node (ref "J7") (pin "P$91") (pinfunction "GPIO23_EQEPI1_MFSXA_SCIRXB_P$91") (pintype "bidirectional"))
    )
    (net (code "98") (name "GPIO26") (class "Default")
      (node (ref "IC2") (pin "17") (pinfunction "B2_17") (pintype "bidirectional"))
      (node (ref "J7") (pin "P$36") (pinfunction "GPIO26_ECAP3_EQEPI2_MCLKXB_P$36") (pintype "bidirectional"))
    )
    (net (code "99") (name "GPIO27") (class "Default")
      (node (ref "IC2") (pin "15") (pinfunction "B1_15") (pintype "bidirectional"))
      (node (ref "J7") (pin "P$86") (pinfunction "GPIO27_ECAP4_EQEPS2_MFSXB_P$86") (pintype "bidirectional"))
    )
    (net (code "100") (name "GPIO32_SDA") (class "Default")
      (node (ref "J7") (pin "P$45") (pinfunction "GPIO32_I2CSDA_SYNCI_ADCSOSA_P$45") (pintype "bidirectional"))
      (node (ref "R28") (pin "1") (pinfunction "1_1") (pintype "passive"))
      (node (ref "SV12") (pin "5") (pinfunction "5_5") (pintype "passive"))
      (node (ref "SV13") (pin "5") (pinfunction "5_5") (pintype "passive"))
      (node (ref "SV14") (pin "5") (pinfunction "5_5") (pintype "passive"))
      (node (ref "SV15") (pin "5") (pinfunction "5_5") (pintype "passive"))
    )
    (net (code "101") (name "GPIO33_SCL") (class "Default")
      (node (ref "J7") (pin "P$95") (pinfunction "GPIO33_I2CSCL_SYNCO_ADCSOCB_P$95") (pintype "bidirectional"))
      (node (ref "R29") (pin "2") (pinfunction "2_2") (pintype "passive"))
      (node (ref "SV12") (pin "3") (pinfunction "3_3") (pintype "passive"))
      (node (ref "SV13") (pin "3") (pinfunction "3_3") (pintype "passive"))
      (node (ref "SV14") (pin "3") (pinfunction "3_3") (pintype "passive"))
      (node (ref "SV15") (pin "3") (pinfunction "3_3") (pintype "passive"))
    )
    (net (code "102") (name "GPIO48") (class "Default")
      (node (ref "J7") (pin "P$30") (pinfunction "GPIO48_ECAP5_XD31_P$30") (pintype "bidirectional"))
      (node (ref "PINS") (pin "10") (pinfunction "10_10") (pintype "passive"))
    )
    (net (code "103") (name "GPIO49") (class "Default")
      (node (ref "J7") (pin "P$80") (pinfunction "GPIO49_ECAP6_XD30_P$80") (pintype "bidirectional"))
      (node (ref "PINS") (pin "9") (pinfunction "9_9") (pintype "passive"))
    )
    (net (code "104") (name "GPIO58") (class "Default")
      (node (ref "J7") (pin "P$18") (pinfunction "GPIO58_MCLKRA_XD21_P$18") (pintype "bidirectional"))
      (node (ref "PINS") (pin "8") (pinfunction "8_8") (pintype "passive"))
    )
    (net (code "105") (name "GPIO60") (class "Default")
      (node (ref "J7") (pin "P$20") (pinfunction "GPIO60_MCLKRB_XD19_P$20") (pintype "bidirectional"))
      (node (ref "ON_LED") (pin "2") (pinfunction "2_2") (pintype "passive"))
    )
    (net (code "106") (name "GPIO61") (class "Default")
      (node (ref "D_LED1") (pin "K") (pinfunction "C_K") (pintype "passive"))
      (node (ref "J7") (pin "P$70") (pinfunction "GPIO61_MFSRB_XD18_P$70") (pintype "bidirectional"))
    )
    (net (code "107") (name "GPIO62_SCIRXC") (class "Default")
      (node (ref "J7") (pin "P$22") (pinfunction "GPIO62_SCIRXC_XD17_P$22") (pintype "bidirectional"))
      (node (ref "U2") (pin "12") (pinfunction "ROUT1_12") (pintype "bidirectional"))
      (node (ref "UART_SENSOR") (pin "5") (pinfunction "5_5") (pintype "passive"))
    )
    (net (code "108") (name "GPIO63_SCITXC") (class "Default")
      (node (ref "J7") (pin "P$72") (pinfunction "GPIO63_SCITXC_XD16_P$72") (pintype "bidirectional"))
      (node (ref "U2") (pin "11") (pinfunction "DIN1_11") (pintype "bidirectional"))
      (node (ref "UART_SENSOR") (pin "4") (pinfunction "4_4") (pintype "passive"))
    )
    (net (code "109") (name "GPIO86_SCIRTSC") (class "Default")
      (node (ref "J7") (pin "P$32") (pinfunction "GPIO86_P$32") (pintype "bidirectional"))
      (node (ref "PINS") (pin "6") (pinfunction "6_6") (pintype "passive"))
      (node (ref "U2") (pin "10") (pinfunction "DIN2_10") (pintype "bidirectional"))
      (node (ref "UART_SENSOR") (pin "3") (pinfunction "3_3") (pintype "passive"))
    )
    (net (code "110") (name "GPIO87_SCICTSC") (class "Default")
      (node (ref "J7") (pin "P$42") (pinfunction "GPIO87_P$42") (pintype "bidirectional"))
      (node (ref "PINS") (pin "5") (pinfunction "5_5") (pintype "passive"))
      (node (ref "U2") (pin "9") (pinfunction "ROUT2_9") (pintype "bidirectional"))
      (node (ref "UART_SENSOR") (pin "2") (pinfunction "2_2") (pintype "passive"))
    )
    (net (code "111") (name "INHIBIT_1") (class "Default")
      (node (ref "AMP_1") (pin "S_5") (pinfunction "INHIBIT_IN_S_5") (pintype "bidirectional"))
      (node (ref "AMP_2") (pin "S_5") (pinfunction "INHIBIT_IN_S_5") (pintype "bidirectional"))
      (node (ref "AMP_3") (pin "S_5") (pinfunction "INHIBIT_IN_S_5") (pintype "bidirectional"))
      (node (ref "AMP_4") (pin "S_5") (pinfunction "INHIBIT_IN_S_5") (pintype "bidirectional"))
      (node (ref "AMP_5") (pin "S_5") (pinfunction "INHIBIT_IN_S_5") (pintype "bidirectional"))
      (node (ref "INHIBIT_SWITCH") (pin "2") (pinfunction "2_2") (pintype "passive"))
      (node (ref "SV1") (pin "5") (pinfunction "INHIBIT_IN_5") (pintype "passive"))
      (node (ref "SV2") (pin "5") (pinfunction "INHIBIT_IN_5") (pintype "passive"))
      (node (ref "SV3") (pin "5") (pinfunction "INHIBIT_IN_5") (pintype "passive"))
      (node (ref "SV4") (pin "5") (pinfunction "INHIBIT_IN_5") (pintype "passive"))
      (node (ref "SV5") (pin "5") (pinfunction "INHIBIT_IN_5") (pintype "passive"))
    )
    (net (code "112") (name "IN_ADCB0") (class "Default")
      (node (ref "R10") (pin "2") (pinfunction "2_2") (pintype "passive"))
      (node (ref "R9") (pin "1") (pinfunction "1_1") (pintype "passive"))
      (node (ref "U16") (pin "P$3") (pinfunction "+INA_P$3") (pintype "bidirectional"))
    )
    (net (code "113") (name "IN_ADCB1") (class "Default")
      (node (ref "R11") (pin "1") (pinfunction "1_1") (pintype "passive"))
      (node (ref "R12") (pin "2") (pinfunction "2_2") (pintype "passive"))
      (node (ref "U16") (pin "P$5") (pinfunction "+INB_P$5") (pintype "bidirectional"))
    )
    (net (code "114") (name "IN_ADCB2") (class "Default")
      (node (ref "R13") (pin "1") (pinfunction "1_1") (pintype "passive"))
      (node (ref "R14") (pin "2") (pinfunction "2_2") (pintype "passive"))
      (node (ref "U16") (pin "P$10") (pinfunction "+INC_P$10") (pintype "bidirectional"))
    )
    (net (code "115") (name "IN_ADCB3") (class "Default")
      (node (ref "R15") (pin "1") (pinfunction "1_1") (pintype "passive"))
      (node (ref "R16") (pin "2") (pinfunction "2_2") (pintype "passive"))
      (node (ref "U16") (pin "P$12") (pinfunction "+IND_P$12") (pintype "bidirectional"))
    )
    (net (code "116") (name "JOINT1_INDEX") (class "Default")
      (node (ref "JOINT_INDEX") (pin "10") (pinfunction "10_10") (pintype "passive"))
      (node (ref "X4") (pin "19") (pinfunction "19_19") (pintype "passive"))
    )
    (net (code "117") (name "JOINT2_INDEX") (class "Default")
      (node (ref "JOINT_INDEX") (pin "8") (pinfunction "8_8") (pintype "passive"))
      (node (ref "X4") (pin "21") (pinfunction "21_21") (pintype "passive"))
    )
    (net (code "118") (name "JOINT3_INDEX") (class "Default")
      (node (ref "JOINT_INDEX") (pin "6") (pinfunction "6_6") (pintype "passive"))
      (node (ref "X4") (pin "23") (pinfunction "23_23") (pintype "passive"))
    )
    (net (code "119") (name "JOINT4_INDEX") (class "Default")
      (node (ref "JOINT_INDEX") (pin "4") (pinfunction "4_4") (pintype "passive"))
      (node (ref "X4") (pin "25") (pinfunction "25_25") (pintype "passive"))
    )
    (net (code "120") (name "JOINT5_INDEX") (class "Default")
      (node (ref "JOINT_INDEX") (pin "2") (pinfunction "2_2") (pintype "passive"))
      (node (ref "X4") (pin "17") (pinfunction "17_17") (pintype "passive"))
    )
    (net (code "121") (name "MISO_5V") (class "Default")
      (node (ref "IC2") (pin "20") (pinfunction "A4_20") (pintype "bidirectional"))
      (node (ref "U10") (pin "6") (pinfunction "MISO_6") (pintype "bidirectional"))
      (node (ref "U12") (pin "6") (pinfunction "MISO_6") (pintype "bidirectional"))
      (node (ref "U13") (pin "6") (pinfunction "MISO_6") (pintype "bidirectional"))
      (node (ref "U14") (pin "6") (pinfunction "MISO_6") (pintype "bidirectional"))
      (node (ref "U7") (pin "6") (pinfunction "MISO_6") (pintype "bidirectional"))
      (node (ref "U8") (pin "6") (pinfunction "MISO_6") (pintype "bidirectional"))
      (node (ref "U9") (pin "6") (pinfunction "MISO_6") (pintype "bidirectional"))
    )
    (net (code "122") (name "MOSI_5V") (class "Default")
      (node (ref "IC2") (pin "18") (pinfunction "A3_18") (pintype "bidirectional"))
      (node (ref "U10") (pin "7") (pinfunction "MOSI_7") (pintype "bidirectional"))
      (node (ref "U12") (pin "7") (pinfunction "MOSI_7") (pintype "bidirectional"))
      (node (ref "U13") (pin "7") (pinfunction "MOSI_7") (pintype "bidirectional"))
      (node (ref "U14") (pin "7") (pinfunction "MOSI_7") (pintype "bidirectional"))
      (node (ref "U7") (pin "7") (pinfunction "MOSI_7") (pintype "bidirectional"))
      (node (ref "U8") (pin "7") (pinfunction "MOSI_7") (pintype "bidirectional"))
      (node (ref "U9") (pin "7") (pinfunction "MOSI_7") (pintype "bidirectional"))
    )
    (net (code "123") (name "MOTOR_A_1") (class "Default")
      (node (ref "AMP_1") (pin "P_10") (pinfunction "MOTOR_A_1_P_10") (pintype "bidirectional"))
      (node (ref "AMP_1") (pin "P_11") (pinfunction "MOTOR_A_2_P_11") (pintype "bidirectional"))
      (node (ref "U$1") (pin "P$3") (pinfunction "P$3_P$3") (pintype "passive"))
    )
    (net (code "124") (name "MOTOR_A_2") (class "Default")
      (node (ref "AMP_2") (pin "P_10") (pinfunction "MOTOR_A_1_P_10") (pintype "bidirectional"))
      (node (ref "AMP_2") (pin "P_11") (pinfunction "MOTOR_A_2_P_11") (pintype "bidirectional"))
      (node (ref "U$2") (pin "P$3") (pinfunction "P$3_P$3") (pintype "passive"))
    )
    (net (code "125") (name "MOTOR_A_3") (class "Default")
      (node (ref "AMP_3") (pin "P_10") (pinfunction "MOTOR_A_1_P_10") (pintype "bidirectional"))
      (node (ref "AMP_3") (pin "P_11") (pinfunction "MOTOR_A_2_P_11") (pintype "bidirectional"))
      (node (ref "U$3") (pin "P$3") (pinfunction "P$3_P$3") (pintype "passive"))
    )
    (net (code "126") (name "MOTOR_A_4") (class "Default")
      (node (ref "AMP_4") (pin "P_10") (pinfunction "MOTOR_A_1_P_10") (pintype "bidirectional"))
      (node (ref "AMP_4") (pin "P_11") (pinfunction "MOTOR_A_2_P_11") (pintype "bidirectional"))
      (node (ref "U$4") (pin "P$3") (pinfunction "P$3_P$3") (pintype "passive"))
    )
    (net (code "127") (name "MOTOR_A_5") (class "Default")
      (node (ref "AMP_5") (pin "P_10") (pinfunction "MOTOR_A_1_P_10") (pintype "bidirectional"))
      (node (ref "AMP_5") (pin "P_11") (pinfunction "MOTOR_A_2_P_11") (pintype "bidirectional"))
      (node (ref "U$5") (pin "P$3") (pinfunction "P$3_P$3") (pintype "passive"))
    )
    (net (code "128") (name "MOTOR_BREAK") (class "Default")
      (node (ref "BREAK_CTRL") (pin "2") (pinfunction "2_2") (pintype "passive"))
      (node (ref "R4") (pin "2") (pinfunction "2_2") (pintype "passive"))
      (node (ref "R5") (pin "2") (pinfunction "2_2") (pintype "passive"))
    )
    (net (code "129") (name "MOTOR_B_1") (class "Default")
      (node (ref "AMP_1") (pin "P_8") (pinfunction "MOTOR_B_1_P_8") (pintype "bidirectional"))
      (node (ref "AMP_1") (pin "P_9") (pinfunction "MOTOR_B_2_P_9") (pintype "bidirectional"))
      (node (ref "U$1") (pin "P$2") (pinfunction "P$2_P$2") (pintype "passive"))
    )
    (net (code "130") (name "MOTOR_B_2") (class "Default")
      (node (ref "AMP_2") (pin "P_8") (pinfunction "MOTOR_B_1_P_8") (pintype "bidirectional"))
      (node (ref "AMP_2") (pin "P_9") (pinfunction "MOTOR_B_2_P_9") (pintype "bidirectional"))
      (node (ref "U$2") (pin "P$2") (pinfunction "P$2_P$2") (pintype "passive"))
    )
    (net (code "131") (name "MOTOR_B_3") (class "Default")
      (node (ref "AMP_3") (pin "P_8") (pinfunction "MOTOR_B_1_P_8") (pintype "bidirectional"))
      (node (ref "AMP_3") (pin "P_9") (pinfunction "MOTOR_B_2_P_9") (pintype "bidirectional"))
      (node (ref "U$3") (pin "P$2") (pinfunction "P$2_P$2") (pintype "passive"))
    )
    (net (code "132") (name "MOTOR_B_4") (class "Default")
      (node (ref "AMP_4") (pin "P_8") (pinfunction "MOTOR_B_1_P_8") (pintype "bidirectional"))
      (node (ref "AMP_4") (pin "P_9") (pinfunction "MOTOR_B_2_P_9") (pintype "bidirectional"))
      (node (ref "U$4") (pin "P$2") (pinfunction "P$2_P$2") (pintype "passive"))
    )
    (net (code "133") (name "MOTOR_B_5") (class "Default")
      (node (ref "AMP_5") (pin "P_8") (pinfunction "MOTOR_B_1_P_8") (pintype "bidirectional"))
      (node (ref "AMP_5") (pin "P_9") (pinfunction "MOTOR_B_2_P_9") (pintype "bidirectional"))
      (node (ref "U$5") (pin "P$2") (pinfunction "P$2_P$2") (pintype "passive"))
    )
    (net (code "134") (name "MOTOR_DIR_1") (class "Default")
      (node (ref "AMP_1") (pin "S_3") (pinfunction "DIR_IN_S_3") (pintype "bidirectional"))
      (node (ref "IC3") (pin "13") (pinfunction "Y6_13") (pintype "tri_state"))
      (node (ref "SV1") (pin "3") (pinfunction "DIR_IN_3") (pintype "passive"))
    )
    (net (code "135") (name "MOTOR_DIR_2") (class "Default")
      (node (ref "AMP_2") (pin "S_3") (pinfunction "DIR_IN_S_3") (pintype "bidirectional"))
      (node (ref "IC3") (pin "14") (pinfunction "Y5_14") (pintype "tri_state"))
      (node (ref "SV2") (pin "3") (pinfunction "DIR_IN_3") (pintype "passive"))
    )
    (net (code "136") (name "MOTOR_DIR_3") (class "Default")
      (node (ref "AMP_3") (pin "S_3") (pinfunction "DIR_IN_S_3") (pintype "bidirectional"))
      (node (ref "IC3") (pin "15") (pinfunction "Y4_15") (pintype "tri_state"))
      (node (ref "SV3") (pin "3") (pinfunction "DIR_IN_3") (pintype "passive"))
    )
    (net (code "137") (name "MOTOR_DIR_4") (class "Default")
      (node (ref "AMP_4") (pin "S_3") (pinfunction "DIR_IN_S_3") (pintype "bidirectional"))
      (node (ref "IC3") (pin "16") (pinfunction "Y3_16") (pintype "tri_state"))
      (node (ref "SV4") (pin "3") (pinfunction "DIR_IN_3") (pintype "passive"))
    )
    (net (code "138") (name "MOTOR_DIR_5") (class "Default")
      (node (ref "AMP_5") (pin "S_3") (pinfunction "DIR_IN_S_3") (pintype "bidirectional"))
      (node (ref "IC3") (pin "17") (pinfunction "Y2_17") (pintype "tri_state"))
      (node (ref "SV5") (pin "3") (pinfunction "DIR_IN_3") (pintype "passive"))
    )
    (net (code "139") (name "MOTOR_DIR_6") (class "Default")
      (node (ref "IC3") (pin "18") (pinfunction "Y1_18") (pintype "tri_state"))
    )
    (net (code "140") (name "MOTOR_PWM_1") (class "Default")
      (node (ref "AMP_1") (pin "S_1") (pinfunction "PWM_IN_S_1") (pintype "bidirectional"))
      (node (ref "IC1") (pin "13") (pinfunction "Y6_13") (pintype "tri_state"))
      (node (ref "SV1") (pin "1") (pinfunction "PWM_IN_1") (pintype "passive"))
    )
    (net (code "141") (name "MOTOR_PWM_2") (class "Default")
      (node (ref "AMP_2") (pin "S_1") (pinfunction "PWM_IN_S_1") (pintype "bidirectional"))
      (node (ref "IC1") (pin "14") (pinfunction "Y5_14") (pintype "tri_state"))
      (node (ref "SV2") (pin "1") (pinfunction "PWM_IN_1") (pintype "passive"))
    )
    (net (code "142") (name "MOTOR_PWM_3") (class "Default")
      (node (ref "AMP_3") (pin "S_1") (pinfunction "PWM_IN_S_1") (pintype "bidirectional"))
      (node (ref "IC1") (pin "15") (pinfunction "Y4_15") (pintype "tri_state"))
      (node (ref "SV3") (pin "1") (pinfunction "PWM_IN_1") (pintype "passive"))
    )
    (net (code "143") (name "MOTOR_PWM_4") (class "Default")
      (node (ref "AMP_4") (pin "S_1") (pinfunction "PWM_IN_S_1") (pintype "bidirectional"))
      (node (ref "IC1") (pin "16") (pinfunction "Y3_16") (pintype "tri_state"))
      (node (ref "SV4") (pin "1") (pinfunction "PWM_IN_1") (pintype "passive"))
    )
    (net (code "144") (name "MOTOR_PWM_5") (class "Default")
      (node (ref "AMP_5") (pin "S_1") (pinfunction "PWM_IN_S_1") (pintype "bidirectional"))
      (node (ref "IC1") (pin "17") (pinfunction "Y2_17") (pintype "tri_state"))
      (node (ref "SV5") (pin "1") (pinfunction "PWM_IN_1") (pintype "passive"))
    )
    (net (code "145") (name "MOTOR_PWM_6") (class "Default")
      (node (ref "IC1") (pin "18") (pinfunction "Y1_18") (pintype "tri_state"))
    )
    (net (code "146") (name "Net-(C27-Pad1)") (class "Default")
      (node (ref "C27") (pin "1") (pinfunction "1_1") (pintype "passive"))
      (node (ref "L2") (pin "1") (pinfunction "1_1") (pintype "passive"))
      (node (ref "X2") (pin "VBUS") (pinfunction "VBUS_VBUS") (pintype "bidirectional"))
    )
    (net (code "147") (name "Net-(D_LED1-PadA)") (class "Default")
      (node (ref "D_LED1") (pin "A") (pinfunction "A_A") (pintype "passive"))
      (node (ref "R35") (pin "1") (pinfunction "1_1") (pintype "passive"))
    )
    (net (code "148") (name "Net-(D_LED2-PadA)") (class "Default")
      (node (ref "D_LED2") (pin "A") (pinfunction "A_A") (pintype "passive"))
      (node (ref "R36") (pin "1") (pinfunction "1_1") (pintype "passive"))
    )
    (net (code "149") (name "Net-(D_LED3-PadA)") (class "Default")
      (node (ref "D_LED3") (pin "A") (pinfunction "A_A") (pintype "passive"))
      (node (ref "R37") (pin "1") (pinfunction "1_1") (pintype "passive"))
    )
    (net (code "150") (name "Net-(IC1A-A1)") (class "Default")
      (node (ref "IC1") (pin "2") (pinfunction "A1_2") (pintype "input"))
      (node (ref "PWM") (pin "6") (pinfunction "6_6") (pintype "passive"))
    )
    (net (code "151") (name "Net-(IC1A-A2)") (class "Default")
      (node (ref "IC1") (pin "3") (pinfunction "A2_3") (pintype "input"))
      (node (ref "PWM") (pin "5") (pinfunction "5_5") (pintype "passive"))
    )
    (net (code "152") (name "Net-(IC1A-A3)") (class "Default")
      (node (ref "IC1") (pin "4") (pinfunction "A3_4") (pintype "input"))
      (node (ref "PWM") (pin "4") (pinfunction "4_4") (pintype "passive"))
    )
    (net (code "153") (name "Net-(IC1A-A4)") (class "Default")
      (node (ref "IC1") (pin "5") (pinfunction "A4_5") (pintype "input"))
      (node (ref "PWM") (pin "3") (pinfunction "3_3") (pintype "passive"))
    )
    (net (code "154") (name "Net-(IC1A-A5)") (class "Default")
      (node (ref "IC1") (pin "6") (pinfunction "A5_6") (pintype "input"))
      (node (ref "PWM") (pin "2") (pinfunction "2_2") (pintype "passive"))
    )
    (net (code "155") (name "Net-(IC1A-A6)") (class "Default")
      (node (ref "IC1") (pin "7") (pinfunction "A6_7") (pintype "input"))
      (node (ref "PWM") (pin "1") (pinfunction "1_1") (pintype "passive"))
    )
    (net (code "156") (name "Net-(IC3A-A1)") (class "Default")
      (node (ref "DIR") (pin "6") (pinfunction "6_6") (pintype "passive"))
      (node (ref "IC3") (pin "2") (pinfunction "A1_2") (pintype "input"))
    )
    (net (code "157") (name "Net-(IC3A-A2)") (class "Default")
      (node (ref "DIR") (pin "5") (pinfunction "5_5") (pintype "passive"))
      (node (ref "IC3") (pin "3") (pinfunction "A2_3") (pintype "input"))
    )
    (net (code "158") (name "Net-(IC3A-A3)") (class "Default")
      (node (ref "DIR") (pin "4") (pinfunction "4_4") (pintype "passive"))
      (node (ref "IC3") (pin "4") (pinfunction "A3_4") (pintype "input"))
    )
    (net (code "159") (name "Net-(IC3A-A4)") (class "Default")
      (node (ref "DIR") (pin "3") (pinfunction "3_3") (pintype "passive"))
      (node (ref "IC3") (pin "5") (pinfunction "A4_5") (pintype "input"))
    )
    (net (code "160") (name "Net-(IC3A-A5)") (class "Default")
      (node (ref "DIR") (pin "2") (pinfunction "2_2") (pintype "passive"))
      (node (ref "IC3") (pin "6") (pinfunction "A5_6") (pintype "input"))
    )
    (net (code "161") (name "Net-(IC3A-A6)") (class "Default")
      (node (ref "DIR") (pin "1") (pinfunction "1_1") (pintype "passive"))
      (node (ref "IC3") (pin "7") (pinfunction "A6_7") (pintype "input"))
    )
    (net (code "162") (name "Net-(INHIBIT_LED-Pad1)") (class "Default")
      (node (ref "INHIBIT_LED") (pin "1") (pinfunction "1_1") (pintype "passive"))
      (node (ref "R17") (pin "1") (pinfunction "1_1") (pintype "passive"))
    )
    (net (code "163") (name "Net-(LED_5V-PadA)") (class "Default")
      (node (ref "LED_5V") (pin "A") (pinfunction "A_A") (pintype "passive"))
      (node (ref "R33") (pin "1") (pinfunction "1_1") (pintype "passive"))
    )
    (net (code "164") (name "Net-(LED_5V1-C)") (class "Default")
      (node (ref "LED_5V1") (pin "K") (pinfunction "C_K") (pintype "passive"))
      (node (ref "R19") (pin "1") (pinfunction "1_1") (pintype "passive"))
    )
    (net (code "165") (name "Net-(LED_5V2-C)") (class "Default")
      (node (ref "LED_5V2") (pin "K") (pinfunction "C_K") (pintype "passive"))
      (node (ref "R21") (pin "1") (pinfunction "1_1") (pintype "passive"))
    )
    (net (code "166") (name "Net-(LED_5V4-C)") (class "Default")
      (node (ref "LED_5V4") (pin "K") (pinfunction "C_K") (pintype "passive"))
      (node (ref "R23") (pin "1") (pinfunction "1_1") (pintype "passive"))
    )
    (net (code "167") (name "Net-(LED_5V5-C)") (class "Default")
      (node (ref "LED_5V5") (pin "K") (pinfunction "C_K") (pintype "passive"))
      (node (ref "R25") (pin "1") (pinfunction "1_1") (pintype "passive"))
    )
    (net (code "168") (name "Net-(LED_RX1-C)") (class "Default")
      (node (ref "LED_RX1") (pin "K") (pinfunction "C_K") (pintype "passive"))
      (node (ref "U6") (pin "23") (pinfunction "CBUS0_23") (pintype "bidirectional"))
    )
    (net (code "169") (name "Net-(LED_RX1-PadA)") (class "Default")
      (node (ref "LED_RX1") (pin "A") (pinfunction "A_A") (pintype "passive"))
      (node (ref "R30") (pin "1") (pinfunction "1_1") (pintype "passive"))
    )
    (net (code "170") (name "Net-(LED_TX1-C)") (class "Default")
      (node (ref "LED_TX1") (pin "K") (pinfunction "C_K") (pintype "passive"))
      (node (ref "U6") (pin "22") (pinfunction "CBUS1_22") (pintype "bidirectional"))
    )
    (net (code "171") (name "Net-(LED_TX1-PadA)") (class "Default")
      (node (ref "LED_TX1") (pin "A") (pinfunction "A_A") (pintype "passive"))
      (node (ref "R31") (pin "1") (pinfunction "1_1") (pintype "passive"))
    )
    (net (code "172") (name "Net-(ON_LED-Pad1)") (class "Default")
      (node (ref "ON_LED") (pin "1") (pinfunction "1_1") (pintype "passive"))
      (node (ref "R38") (pin "1") (pinfunction "1_1") (pintype "passive"))
    )
    (net (code "173") (name "Net-(P_LED1-C)") (class "Default")
      (node (ref "P_LED1") (pin "K") (pinfunction "C_K") (pintype "passive"))
      (node (ref "U3") (pin "27") (pinfunction "GPIO34_27") (pintype "bidirectional"))
    )
    (net (code "174") (name "Net-(P_LED1-PadA)") (class "Default")
      (node (ref "P_LED1") (pin "A") (pinfunction "A_A") (pintype "passive"))
      (node (ref "R3") (pin "1") (pinfunction "1_1") (pintype "passive"))
    )
    (net (code "175") (name "Net-(P_LED2-PadA)") (class "Default")
      (node (ref "P_LED2") (pin "A") (pinfunction "A_A") (pintype "passive"))
      (node (ref "R26") (pin "1") (pinfunction "1_1") (pintype "passive"))
    )
    (net (code "176") (name "Net-(P_LED3-PadA)") (class "Default")
      (node (ref "P_LED3") (pin "A") (pinfunction "A_A") (pintype "passive"))
      (node (ref "R27") (pin "1") (pinfunction "1_1") (pintype "passive"))
    )
    (net (code "177") (name "Net-(Q3-B)") (class "Default")
      (node (ref "Q3") (pin "1") (pinfunction "B_1") (pintype "passive"))
      (node (ref "R4") (pin "1") (pinfunction "1_1") (pintype "passive"))
    )
    (net (code "178") (name "Net-(Q4-B)") (class "Default")
      (node (ref "Q4") (pin "1") (pinfunction "B_1") (pintype "passive"))
      (node (ref "R5") (pin "1") (pinfunction "1_1") (pintype "passive"))
    )
    (net (code "179") (name "Net-(QG1-OUT)") (class "Default")
      (node (ref "QG1") (pin "8") (pinfunction "OUT_8") (pintype "output"))
      (node (ref "U10") (pin "2") (pinfunction "FCKI_2") (pintype "bidirectional"))
      (node (ref "U12") (pin "2") (pinfunction "FCKI_2") (pintype "bidirectional"))
      (node (ref "U13") (pin "2") (pinfunction "FCKI_2") (pintype "bidirectional"))
      (node (ref "U14") (pin "2") (pinfunction "FCKI_2") (pintype "bidirectional"))
      (node (ref "U7") (pin "2") (pinfunction "FCKI_2") (pintype "bidirectional"))
      (node (ref "U8") (pin "2") (pinfunction "FCKI_2") (pintype "bidirectional"))
      (node (ref "U9") (pin "2") (pinfunction "FCKI_2") (pintype "bidirectional"))
    )
    (net (code "180") (name "Net-(R32-Pad1)") (class "Default")
      (node (ref "R32") (pin "1") (pinfunction "1_1") (pintype "passive"))
      (node (ref "USB_PWR1") (pin "A") (pinfunction "A_A") (pintype "passive"))
    )
    (net (code "181") (name "Net-(U2-C1+)") (class "Default")
      (node (ref "C8") (pin "1") (pinfunction "1_1") (pintype "passive"))
      (node (ref "U2") (pin "1") (pinfunction "C1+_1") (pintype "bidirectional"))
    )
    (net (code "182") (name "Net-(U2-C1-)") (class "Default")
      (node (ref "C8") (pin "2") (pinfunction "2_2") (pintype "passive"))
      (node (ref "U2") (pin "3") (pinfunction "C1-_3") (pintype "bidirectional"))
    )
    (net (code "183") (name "Net-(U2-C2+)") (class "Default")
      (node (ref "C9") (pin "1") (pinfunction "1_1") (pintype "passive"))
      (node (ref "U2") (pin "4") (pinfunction "C2+_4") (pintype "bidirectional"))
    )
    (net (code "184") (name "Net-(U2-C2-)") (class "Default")
      (node (ref "C9") (pin "2") (pinfunction "2_2") (pintype "passive"))
      (node (ref "U2") (pin "5") (pinfunction "C2-_5") (pintype "bidirectional"))
    )
    (net (code "185") (name "Net-(U2-V+)") (class "Default")
      (node (ref "C7") (pin "2") (pinfunction "2_2") (pintype "passive"))
      (node (ref "U2") (pin "2") (pinfunction "V+_2") (pintype "bidirectional"))
    )
    (net (code "186") (name "Net-(U2-V-)") (class "Default")
      (node (ref "C10") (pin "1") (pinfunction "1_1") (pintype "passive"))
      (node (ref "U2") (pin "6") (pinfunction "V-_6") (pintype "bidirectional"))
    )
    (net (code "187") (name "Net-(U3-VDD)") (class "Default")
      (node (ref "C19") (pin "1") (pinfunction "1_1") (pintype "passive"))
      (node (ref "U3") (pin "1") (pinfunction "VDD_1") (pintype "bidirectional"))
    )
    (net (code "188") (name "Net-(U3-VDD2)") (class "Default")
      (node (ref "C13") (pin "1") (pinfunction "1_1") (pintype "passive"))
      (node (ref "U3") (pin "11") (pinfunction "VDD2_11") (pintype "bidirectional"))
    )
    (net (code "189") (name "Net-(U4-C1+)") (class "Default")
      (node (ref "C16") (pin "1") (pinfunction "1_1") (pintype "passive"))
      (node (ref "U4") (pin "1") (pinfunction "C1+_1") (pintype "bidirectional"))
    )
    (net (code "190") (name "Net-(U4-C1-)") (class "Default")
      (node (ref "C16") (pin "2") (pinfunction "2_2") (pintype "passive"))
      (node (ref "U4") (pin "3") (pinfunction "C1-_3") (pintype "bidirectional"))
    )
    (net (code "191") (name "Net-(U4-C2+)") (class "Default")
      (node (ref "C17") (pin "1") (pinfunction "1_1") (pintype "passive"))
      (node (ref "U4") (pin "4") (pinfunction "C2+_4") (pintype "bidirectional"))
    )
    (net (code "192") (name "Net-(U4-C2-)") (class "Default")
      (node (ref "C17") (pin "2") (pinfunction "2_2") (pintype "passive"))
      (node (ref "U4") (pin "5") (pinfunction "C2-_5") (pintype "bidirectional"))
    )
    (net (code "193") (name "Net-(U4-V+)") (class "Default")
      (node (ref "C15") (pin "2") (pinfunction "2_2") (pintype "passive"))
      (node (ref "U4") (pin "2") (pinfunction "V+_2") (pintype "bidirectional"))
    )
    (net (code "194") (name "Net-(U4-V-)") (class "Default")
      (node (ref "C18") (pin "1") (pinfunction "1_1") (pintype "passive"))
      (node (ref "U4") (pin "6") (pinfunction "V-_6") (pintype "bidirectional"))
    )
    (net (code "195") (name "Net-(U6-3V3OUT)") (class "Default")
      (node (ref "C26") (pin "1") (pinfunction "1_1") (pintype "passive"))
      (node (ref "U6") (pin "17") (pinfunction "3V3OUT_17") (pintype "output"))
      (node (ref "U6") (pin "4") (pinfunction "VCCIO_4") (pintype "power_in"))
    )
    (net (code "196") (name "Net-(U6-CBUS2)") (class "Default")
      (node (ref "SV20") (pin "3") (pinfunction "3_3") (pintype "passive"))
      (node (ref "U6") (pin "13") (pinfunction "CBUS2_13") (pintype "bidirectional"))
    )
    (net (code "197") (name "Net-(U6-CBUS3)") (class "Default")
      (node (ref "SV20") (pin "7") (pinfunction "7_7") (pintype "passive"))
      (node (ref "U6") (pin "14") (pinfunction "CBUS3_14") (pintype "bidirectional"))
    )
    (net (code "198") (name "Net-(U6-CBUS4)") (class "Default")
      (node (ref "SV20") (pin "9") (pinfunction "9_9") (pintype "passive"))
      (node (ref "U6") (pin "12") (pinfunction "CBUS4_12") (pintype "bidirectional"))
    )
    (net (code "199") (name "Net-(U6-CTS#)") (class "Default")
      (node (ref "SV20") (pin "10") (pinfunction "10_10") (pintype "passive"))
      (node (ref "U6") (pin "11") (pinfunction "CTS#_11") (pintype "input"))
    )
    (net (code "200") (name "Net-(U6-DCD#)") (class "Default")
      (node (ref "SV20") (pin "2") (pinfunction "2_2") (pintype "passive"))
      (node (ref "U6") (pin "10") (pinfunction "DCD#_10") (pintype "input"))
    )
    (net (code "201") (name "Net-(U6-DSR#)") (class "Default")
      (node (ref "SV20") (pin "4") (pinfunction "4_4") (pintype "passive"))
      (node (ref "U6") (pin "9") (pinfunction "DSR#_9") (pintype "input"))
    )
    (net (code "202") (name "Net-(U6-DTR#)") (class "Default")
      (node (ref "SV20") (pin "8") (pinfunction "8_8") (pintype "passive"))
      (node (ref "U6") (pin "2") (pinfunction "DTR#_2") (pintype "output"))
    )
    (net (code "203") (name "Net-(U6-RI#)") (class "Default")
      (node (ref "SV20") (pin "1") (pinfunction "1_1") (pintype "passive"))
      (node (ref "U6") (pin "6") (pinfunction "RI#_6") (pintype "input"))
    )
    (net (code "204") (name "Net-(U6-RTS#)") (class "Default")
      (node (ref "SV9") (pin "2") (pinfunction "2_2") (pintype "passive"))
      (node (ref "U6") (pin "3") (pinfunction "RTS#_3") (pintype "output"))
    )
    (net (code "205") (name "Net-(U6-RXD)") (class "Default")
      (node (ref "SV8") (pin "2") (pinfunction "2_2") (pintype "passive"))
      (node (ref "U6") (pin "5") (pinfunction "RXD_5") (pintype "input"))
    )
    (net (code "206") (name "Net-(U6-TXD)") (class "Default")
      (node (ref "SV7") (pin "2") (pinfunction "2_2") (pintype "passive"))
      (node (ref "U6") (pin "1") (pinfunction "TXD_1") (pintype "output"))
    )
    (net (code "207") (name "Net-(U6-USBDM)") (class "Default")
      (node (ref "C24") (pin "1") (pinfunction "1_1") (pintype "passive"))
      (node (ref "U6") (pin "16") (pinfunction "USBDM_16") (pintype "bidirectional"))
      (node (ref "X2") (pin "D-") (pinfunction "D-_D-") (pintype "bidirectional"))
    )
    (net (code "208") (name "Net-(U6-USBDP)") (class "Default")
      (node (ref "C25") (pin "1") (pinfunction "1_1") (pintype "passive"))
      (node (ref "U6") (pin "15") (pinfunction "USBDP_15") (pintype "bidirectional"))
      (node (ref "X2") (pin "D+") (pinfunction "D+_D+") (pintype "bidirectional"))
    )
    (net (code "209") (name "POWER_GND_1") (class "Default")
      (node (ref "AMP_1") (pin "P_4") (pinfunction "POWER_GND_1_P_4") (pintype "bidirectional"))
      (node (ref "AMP_1") (pin "P_5") (pinfunction "POWER_GND_2_P_5") (pintype "bidirectional"))
      (node (ref "SV16") (pin "2") (pinfunction "2_2") (pintype "passive"))
      (node (ref "U$1") (pin "P$4") (pinfunction "P$4_P$4") (pintype "passive"))
    )
    (net (code "210") (name "POWER_GND_2") (class "Default")
      (node (ref "AMP_2") (pin "P_4") (pinfunction "POWER_GND_1_P_4") (pintype "bidirectional"))
      (node (ref "AMP_2") (pin "P_5") (pinfunction "POWER_GND_2_P_5") (pintype "bidirectional"))
      (node (ref "SV11") (pin "2") (pinfunction "2_2") (pintype "passive"))
      (node (ref "U$2") (pin "P$4") (pinfunction "P$4_P$4") (pintype "passive"))
    )
    (net (code "211") (name "POWER_GND_3") (class "Default")
      (node (ref "AMP_3") (pin "P_4") (pinfunction "POWER_GND_1_P_4") (pintype "bidirectional"))
      (node (ref "AMP_3") (pin "P_5") (pinfunction "POWER_GND_2_P_5") (pintype "bidirectional"))
      (node (ref "SV10") (pin "2") (pinfunction "2_2") (pintype "passive"))
      (node (ref "U$3") (pin "P$4") (pinfunction "P$4_P$4") (pintype "passive"))
    )
    (net (code "212") (name "POWER_GND_4") (class "Default")
      (node (ref "AMP_4") (pin "P_4") (pinfunction "POWER_GND_1_P_4") (pintype "bidirectional"))
      (node (ref "AMP_4") (pin "P_5") (pinfunction "POWER_GND_2_P_5") (pintype "bidirectional"))
      (node (ref "SV17") (pin "2") (pinfunction "2_2") (pintype "passive"))
      (node (ref "U$4") (pin "P$4") (pinfunction "P$4_P$4") (pintype "passive"))
    )
    (net (code "213") (name "POWER_GND_5") (class "Default")
      (node (ref "AMP_5") (pin "P_4") (pinfunction "POWER_GND_1_P_4") (pintype "bidirectional"))
      (node (ref "AMP_5") (pin "P_5") (pinfunction "POWER_GND_2_P_5") (pintype "bidirectional"))
      (node (ref "SV18") (pin "2") (pinfunction "2_2") (pintype "passive"))
      (node (ref "U$5") (pin "P$4") (pinfunction "P$4_P$4") (pintype "passive"))
    )
    (net (code "214") (name "RTS_FT232RL") (class "Default")
      (node (ref "J7") (pin "P$31") (pinfunction "GPIO84_P$31") (pintype "bidirectional"))
      (node (ref "SV9") (pin "1") (pinfunction "1_1") (pintype "passive"))
    )
    (net (code "215") (name "RXD_FT232RL") (class "Default")
      (node (ref "J7") (pin "P$93") (pinfunction "GPIO29_SCITXA_RESV_TX6_P$93") (pintype "bidirectional"))
      (node (ref "SV8") (pin "1") (pinfunction "1_1") (pintype "passive"))
    )
    (net (code "216") (name "SCK_5V") (class "Default")
      (node (ref "IC2") (pin "22") (pinfunction "A5_22") (pintype "bidirectional"))
      (node (ref "U10") (pin "5") (pinfunction "SCK_5") (pintype "bidirectional"))
      (node (ref "U12") (pin "5") (pinfunction "SCK_5") (pintype "bidirectional"))
      (node (ref "U13") (pin "5") (pinfunction "SCK_5") (pintype "bidirectional"))
      (node (ref "U14") (pin "5") (pinfunction "SCK_5") (pintype "bidirectional"))
      (node (ref "U7") (pin "5") (pinfunction "SCK_5") (pintype "bidirectional"))
      (node (ref "U8") (pin "5") (pinfunction "SCK_5") (pintype "bidirectional"))
      (node (ref "U9") (pin "5") (pinfunction "SCK_5") (pintype "bidirectional"))
    )
    (net (code "217") (name "SPI1_ENCA") (class "Default")
      (node (ref "U7") (pin "12") (pinfunction "A_12") (pintype "bidirectional"))
      (node (ref "X4") (pin "2") (pinfunction "2_2") (pintype "passive"))
    )
    (net (code "218") (name "SPI1_ENCB") (class "Default")
      (node (ref "U7") (pin "11") (pinfunction "B_11") (pintype "bidirectional"))
      (node (ref "X4") (pin "4") (pinfunction "4_4") (pintype "passive"))
    )
    (net (code "219") (name "SPI2_ENCA") (class "Default")
      (node (ref "U8") (pin "12") (pinfunction "A_12") (pintype "bidirectional"))
      (node (ref "X4") (pin "1") (pinfunction "1_1") (pintype "passive"))
    )
    (net (code "220") (name "SPI2_ENCB") (class "Default")
      (node (ref "U8") (pin "11") (pinfunction "B_11") (pintype "bidirectional"))
      (node (ref "X4") (pin "7") (pinfunction "7_7") (pintype "passive"))
    )
    (net (code "221") (name "SPI3_ENCA") (class "Default")
      (node (ref "U9") (pin "12") (pinfunction "A_12") (pintype "bidirectional"))
      (node (ref "X4") (pin "9") (pinfunction "9_9") (pintype "passive"))
    )
    (net (code "222") (name "SPI3_ENCB") (class "Default")
      (node (ref "U9") (pin "11") (pinfunction "B_11") (pintype "bidirectional"))
      (node (ref "X4") (pin "11") (pinfunction "11_11") (pintype "passive"))
    )
    (net (code "223") (name "SPI4_ENCA") (class "Default")
      (node (ref "U10") (pin "12") (pinfunction "A_12") (pintype "bidirectional"))
      (node (ref "X4") (pin "18") (pinfunction "18_18") (pintype "passive"))
    )
    (net (code "224") (name "SPI4_ENCB") (class "Default")
      (node (ref "U10") (pin "11") (pinfunction "B_11") (pintype "bidirectional"))
      (node (ref "X4") (pin "20") (pinfunction "20_20") (pintype "passive"))
    )
    (net (code "225") (name "SPI5_ENCA") (class "Default")
      (node (ref "U12") (pin "12") (pinfunction "A_12") (pintype "bidirectional"))
      (node (ref "X4") (pin "22") (pinfunction "22_22") (pintype "passive"))
    )
    (net (code "226") (name "SPI5_ENCB") (class "Default")
      (node (ref "U12") (pin "11") (pinfunction "B_11") (pintype "bidirectional"))
      (node (ref "X4") (pin "24") (pinfunction "24_24") (pintype "passive"))
    )
    (net (code "227") (name "SPI6_ENCA") (class "Default")
      (node (ref "SV28") (pin "6") (pinfunction "6_6") (pintype "passive"))
      (node (ref "U13") (pin "12") (pinfunction "A_12") (pintype "bidirectional"))
    )
    (net (code "228") (name "SPI6_ENCB") (class "Default")
      (node (ref "SV28") (pin "10") (pinfunction "10_10") (pintype "passive"))
      (node (ref "U13") (pin "11") (pinfunction "B_11") (pintype "bidirectional"))
    )
    (net (code "229") (name "SPI7_ENCA") (class "Default")
      (node (ref "SV28") (pin "5") (pinfunction "5_5") (pintype "passive"))
      (node (ref "U14") (pin "12") (pinfunction "A_12") (pintype "bidirectional"))
    )
    (net (code "230") (name "SPI7_ENCB") (class "Default")
      (node (ref "SV28") (pin "9") (pinfunction "9_9") (pintype "passive"))
      (node (ref "U14") (pin "11") (pinfunction "B_11") (pintype "bidirectional"))
    )
    (net (code "231") (name "SS1_5V") (class "Default")
      (node (ref "IC2") (pin "11") (pinfunction "A5_11") (pintype "bidirectional"))
      (node (ref "U7") (pin "4") (pinfunction "SS/_4") (pintype "bidirectional"))
    )
    (net (code "232") (name "SS2_5V") (class "Default")
      (node (ref "IC2") (pin "9") (pinfunction "A4_9") (pintype "bidirectional"))
      (node (ref "U8") (pin "4") (pinfunction "SS/_4") (pintype "bidirectional"))
    )
    (net (code "233") (name "SS3_5V") (class "Default")
      (node (ref "IC2") (pin "7") (pinfunction "A3_7") (pintype "bidirectional"))
      (node (ref "U9") (pin "4") (pinfunction "SS/_4") (pintype "bidirectional"))
    )
    (net (code "234") (name "SS4_5V") (class "Default")
      (node (ref "IC2") (pin "5") (pinfunction "A2_5") (pintype "bidirectional"))
      (node (ref "U10") (pin "4") (pinfunction "SS/_4") (pintype "bidirectional"))
    )
    (net (code "235") (name "SS5_5V") (class "Default")
      (node (ref "IC2") (pin "3") (pinfunction "A1_3") (pintype "bidirectional"))
      (node (ref "U12") (pin "4") (pinfunction "SS/_4") (pintype "bidirectional"))
    )
    (net (code "236") (name "SS6_5V") (class "Default")
      (node (ref "IC2") (pin "16") (pinfunction "A2_16") (pintype "bidirectional"))
      (node (ref "U13") (pin "4") (pinfunction "SS/_4") (pintype "bidirectional"))
    )
    (net (code "237") (name "SS7_5V") (class "Default")
      (node (ref "IC2") (pin "14") (pinfunction "A1_14") (pintype "bidirectional"))
      (node (ref "U14") (pin "4") (pinfunction "SS/_4") (pintype "bidirectional"))
    )
    (net (code "238") (name "TXD_FT232RL") (class "Default")
      (node (ref "J7") (pin "P$43") (pinfunction "GPIO28_SCIRXA_RESV_TZ5_P$43") (pintype "bidirectional"))
      (node (ref "SV7") (pin "1") (pinfunction "1_1") (pintype "passive"))
    )
    (net (code "239") (name "UART1_CTS") (class "Default")
      (node (ref "SV6") (pin "4") (pinfunction "4_4") (pintype "passive"))
      (node (ref "U4") (pin "8") (pinfunction "RIN2_8") (pintype "bidirectional"))
    )
    (net (code "240") (name "UART1_RTS") (class "Default")
      (node (ref "SV6") (pin "2") (pinfunction "2_2") (pintype "passive"))
      (node (ref "U4") (pin "7") (pinfunction "DOUT2_7") (pintype "bidirectional"))
    )
    (net (code "241") (name "UART1_RX") (class "Default")
      (node (ref "SV6") (pin "1") (pinfunction "1_1") (pintype "passive"))
      (node (ref "U4") (pin "13") (pinfunction "RIN1_13") (pintype "bidirectional"))
    )
    (net (code "242") (name "UART1_TX") (class "Default")
      (node (ref "SV6") (pin "3") (pinfunction "3_3") (pintype "passive"))
      (node (ref "U4") (pin "14") (pinfunction "DOUT1_14") (pintype "bidirectional"))
    )
    (net (code "243") (name "UART2_CTS") (class "Default")
      (node (ref "SV19") (pin "4") (pinfunction "4_4") (pintype "passive"))
      (node (ref "U2") (pin "8") (pinfunction "RIN2_8") (pintype "bidirectional"))
    )
    (net (code "244") (name "UART2_RTS") (class "Default")
      (node (ref "SV19") (pin "2") (pinfunction "2_2") (pintype "passive"))
      (node (ref "U2") (pin "7") (pinfunction "DOUT2_7") (pintype "bidirectional"))
    )
    (net (code "245") (name "UART2_RX") (class "Default")
      (node (ref "SV19") (pin "1") (pinfunction "1_1") (pintype "passive"))
      (node (ref "U2") (pin "13") (pinfunction "RIN1_13") (pintype "bidirectional"))
    )
    (net (code "246") (name "UART2_TX") (class "Default")
      (node (ref "SV19") (pin "3") (pinfunction "3_3") (pintype "passive"))
      (node (ref "U2") (pin "14") (pinfunction "DOUT1_14") (pintype "bidirectional"))
    )
    (net (code "247") (name "USB_VCC") (class "Default")
      (node (ref "C28") (pin "1") (pinfunction "1_1") (pintype "passive"))
      (node (ref "C29") (pin "1") (pinfunction "1_1") (pintype "passive"))
      (node (ref "L2") (pin "2") (pinfunction "2_2") (pintype "passive"))
      (node (ref "R30") (pin "2") (pinfunction "2_2") (pintype "passive"))
      (node (ref "R31") (pin "2") (pinfunction "2_2") (pintype "passive"))
      (node (ref "R32") (pin "2") (pinfunction "2_2") (pintype "passive"))
      (node (ref "U6") (pin "20") (pinfunction "VCC_20") (pintype "power_in"))
    )
    (net (code "248") (name "V_HIGH_1") (class "Default")
      (node (ref "AMP_1") (pin "P_1") (pinfunction "V_HIGH_1_P_1") (pintype "bidirectional"))
      (node (ref "AMP_1") (pin "P_2") (pinfunction "V_HIGH_2_P_2") (pintype "bidirectional"))
      (node (ref "U$1") (pin "P$1") (pinfunction "P$1_P$1") (pintype "passive"))
    )
    (net (code "249") (name "V_HIGH_2") (class "Default")
      (node (ref "AMP_2") (pin "P_1") (pinfunction "V_HIGH_1_P_1") (pintype "bidirectional"))
      (node (ref "AMP_2") (pin "P_2") (pinfunction "V_HIGH_2_P_2") (pintype "bidirectional"))
      (node (ref "U$2") (pin "P$1") (pinfunction "P$1_P$1") (pintype "passive"))
    )
    (net (code "250") (name "V_HIGH_3") (class "Default")
      (node (ref "AMP_3") (pin "P_1") (pinfunction "V_HIGH_1_P_1") (pintype "bidirectional"))
      (node (ref "AMP_3") (pin "P_2") (pinfunction "V_HIGH_2_P_2") (pintype "bidirectional"))
      (node (ref "U$3") (pin "P$1") (pinfunction "P$1_P$1") (pintype "passive"))
    )
    (net (code "251") (name "V_HIGH_4") (class "Default")
      (node (ref "AMP_4") (pin "P_1") (pinfunction "V_HIGH_1_P_1") (pintype "bidirectional"))
      (node (ref "AMP_4") (pin "P_2") (pinfunction "V_HIGH_2_P_2") (pintype "bidirectional"))
      (node (ref "U$4") (pin "P$1") (pinfunction "P$1_P$1") (pintype "passive"))
    )
    (net (code "252") (name "V_HIGH_5") (class "Default")
      (node (ref "AMP_5") (pin "P_1") (pinfunction "V_HIGH_1_P_1") (pintype "bidirectional"))
      (node (ref "AMP_5") (pin "P_2") (pinfunction "V_HIGH_2_P_2") (pintype "bidirectional"))
      (node (ref "U$5") (pin "P$1") (pinfunction "P$1_P$1") (pintype "passive"))
    )
    (net (code "253") (name "unconnected-(28027_JTAG-Pad6)") (class "Default")
      (node (ref "28027_JTAG") (pin "6") (pinfunction "6_6") (pintype "passive"))
    )
    (net (code "254") (name "unconnected-(28027_JTAG-Pad13)") (class "Default")
      (node (ref "28027_JTAG") (pin "13") (pinfunction "13_13") (pintype "passive"))
    )
    (net (code "255") (name "unconnected-(28027_JTAG-Pad14)") (class "Default")
      (node (ref "28027_JTAG") (pin "14") (pinfunction "14_14") (pintype "passive"))
    )
    (net (code "256") (name "unconnected-(28335_ENC-Pad3)") (class "Default")
      (node (ref "28335_ENC") (pin "3") (pinfunction "3_3") (pintype "passive"))
    )
    (net (code "257") (name "unconnected-(28335_ENC-Pad4)") (class "Default")
      (node (ref "28335_ENC") (pin "4") (pinfunction "4_4") (pintype "passive"))
    )
    (net (code "258") (name "unconnected-(28335_JTAG-Pad6)") (class "Default")
      (node (ref "28335_JTAG") (pin "6") (pinfunction "6_6") (pintype "passive"))
    )
    (net (code "259") (name "unconnected-(ADC_I2C-Pad3)") (class "Default")
      (node (ref "ADC_I2C") (pin "3") (pinfunction "3_3") (pintype "passive"))
    )
    (net (code "260") (name "unconnected-(ADC_I2C-Pad4)") (class "Default")
      (node (ref "ADC_I2C") (pin "4") (pinfunction "4_4") (pintype "passive"))
    )
    (net (code "261") (name "unconnected-(ADC_I2C-Pad6)") (class "Default")
      (node (ref "ADC_I2C") (pin "6") (pinfunction "6_6") (pintype "passive"))
    )
    (net (code "262") (name "unconnected-(AMP_1-+V_HALL_OUT-PadS_6)") (class "Default")
      (node (ref "AMP_1") (pin "S_6") (pinfunction "+V_HALL_OUT_S_6") (pintype "bidirectional"))
    )
    (net (code "263") (name "unconnected-(AMP_1-CURRENT_REF_OUT-PadS_11)") (class "Default")
      (node (ref "AMP_1") (pin "S_11") (pinfunction "CURRENT_REF_OUT_S_11") (pintype "bidirectional"))
    )
    (net (code "264") (name "unconnected-(AMP_1-HALL_1-PadS_8)") (class "Default")
      (node (ref "AMP_1") (pin "S_8") (pinfunction "HALL_1_S_8") (pintype "bidirectional"))
    )
    (net (code "265") (name "unconnected-(AMP_1-HALL_2-PadS_9)") (class "Default")
      (node (ref "AMP_1") (pin "S_9") (pinfunction "HALL_2_S_9") (pintype "bidirectional"))
    )
    (net (code "266") (name "unconnected-(AMP_1-HALL_3-PadS_10)") (class "Default")
      (node (ref "AMP_1") (pin "S_10") (pinfunction "HALL_3_S_10") (pintype "bidirectional"))
    )
    (net (code "267") (name "unconnected-(AMP_1-MOTOR_C_1-PadP_6)") (class "Default")
      (node (ref "AMP_1") (pin "P_6") (pinfunction "MOTOR_C_1_P_6") (pintype "bidirectional"))
    )
    (net (code "268") (name "unconnected-(AMP_1-MOTOR_C_2-PadP_7)") (class "Default")
      (node (ref "AMP_1") (pin "P_7") (pinfunction "MOTOR_C_2_P_7") (pintype "bidirectional"))
    )
    (net (code "269") (name "unconnected-(AMP_1-NC(KEY)-PadP_3)") (class "Default")
      (node (ref "AMP_1") (pin "P_3") (pinfunction "NC(KEY)_P_3") (pintype "bidirectional"))
    )
    (net (code "270") (name "unconnected-(AMP_1-NC_1-PadS_13)") (class "Default")
      (node (ref "AMP_1") (pin "S_13") (pinfunction "NC_1_S_13") (pintype "bidirectional"))
    )
    (net (code "271") (name "unconnected-(AMP_1-NC_2-PadS_14)") (class "Default")
      (node (ref "AMP_1") (pin "S_14") (pinfunction "NC_2_S_14") (pintype "bidirectional"))
    )
    (net (code "272") (name "unconnected-(AMP_1-NC_3-PadS_15)") (class "Default")
      (node (ref "AMP_1") (pin "S_15") (pinfunction "NC_3_S_15") (pintype "bidirectional"))
    )
    (net (code "273") (name "unconnected-(AMP_1-NC_4-PadS_16)") (class "Default")
      (node (ref "AMP_1") (pin "S_16") (pinfunction "NC_4_S_16") (pintype "bidirectional"))
    )
    (net (code "274") (name "unconnected-(AMP_2-+V_HALL_OUT-PadS_6)") (class "Default")
      (node (ref "AMP_2") (pin "S_6") (pinfunction "+V_HALL_OUT_S_6") (pintype "bidirectional"))
    )
    (net (code "275") (name "unconnected-(AMP_2-CURRENT_REF_OUT-PadS_11)") (class "Default")
      (node (ref "AMP_2") (pin "S_11") (pinfunction "CURRENT_REF_OUT_S_11") (pintype "bidirectional"))
    )
    (net (code "276") (name "unconnected-(AMP_2-HALL_1-PadS_8)") (class "Default")
      (node (ref "AMP_2") (pin "S_8") (pinfunction "HALL_1_S_8") (pintype "bidirectional"))
    )
    (net (code "277") (name "unconnected-(AMP_2-HALL_2-PadS_9)") (class "Default")
      (node (ref "AMP_2") (pin "S_9") (pinfunction "HALL_2_S_9") (pintype "bidirectional"))
    )
    (net (code "278") (name "unconnected-(AMP_2-HALL_3-PadS_10)") (class "Default")
      (node (ref "AMP_2") (pin "S_10") (pinfunction "HALL_3_S_10") (pintype "bidirectional"))
    )
    (net (code "279") (name "unconnected-(AMP_2-MOTOR_C_1-PadP_6)") (class "Default")
      (node (ref "AMP_2") (pin "P_6") (pinfunction "MOTOR_C_1_P_6") (pintype "bidirectional"))
    )
    (net (code "280") (name "unconnected-(AMP_2-MOTOR_C_2-PadP_7)") (class "Default")
      (node (ref "AMP_2") (pin "P_7") (pinfunction "MOTOR_C_2_P_7") (pintype "bidirectional"))
    )
    (net (code "281") (name "unconnected-(AMP_2-NC(KEY)-PadP_3)") (class "Default")
      (node (ref "AMP_2") (pin "P_3") (pinfunction "NC(KEY)_P_3") (pintype "bidirectional"))
    )
    (net (code "282") (name "unconnected-(AMP_2-NC_1-PadS_13)") (class "Default")
      (node (ref "AMP_2") (pin "S_13") (pinfunction "NC_1_S_13") (pintype "bidirectional"))
    )
    (net (code "283") (name "unconnected-(AMP_2-NC_2-PadS_14)") (class "Default")
      (node (ref "AMP_2") (pin "S_14") (pinfunction "NC_2_S_14") (pintype "bidirectional"))
    )
    (net (code "284") (name "unconnected-(AMP_2-NC_3-PadS_15)") (class "Default")
      (node (ref "AMP_2") (pin "S_15") (pinfunction "NC_3_S_15") (pintype "bidirectional"))
    )
    (net (code "285") (name "unconnected-(AMP_2-NC_4-PadS_16)") (class "Default")
      (node (ref "AMP_2") (pin "S_16") (pinfunction "NC_4_S_16") (pintype "bidirectional"))
    )
    (net (code "286") (name "unconnected-(AMP_3-+V_HALL_OUT-PadS_6)") (class "Default")
      (node (ref "AMP_3") (pin "S_6") (pinfunction "+V_HALL_OUT_S_6") (pintype "bidirectional"))
    )
    (net (code "287") (name "unconnected-(AMP_3-CURRENT_REF_OUT-PadS_11)") (class "Default")
      (node (ref "AMP_3") (pin "S_11") (pinfunction "CURRENT_REF_OUT_S_11") (pintype "bidirectional"))
    )
    (net (code "288") (name "unconnected-(AMP_3-HALL_1-PadS_8)") (class "Default")
      (node (ref "AMP_3") (pin "S_8") (pinfunction "HALL_1_S_8") (pintype "bidirectional"))
    )
    (net (code "289") (name "unconnected-(AMP_3-HALL_2-PadS_9)") (class "Default")
      (node (ref "AMP_3") (pin "S_9") (pinfunction "HALL_2_S_9") (pintype "bidirectional"))
    )
    (net (code "290") (name "unconnected-(AMP_3-HALL_3-PadS_10)") (class "Default")
      (node (ref "AMP_3") (pin "S_10") (pinfunction "HALL_3_S_10") (pintype "bidirectional"))
    )
    (net (code "291") (name "unconnected-(AMP_3-MOTOR_C_1-PadP_6)") (class "Default")
      (node (ref "AMP_3") (pin "P_6") (pinfunction "MOTOR_C_1_P_6") (pintype "bidirectional"))
    )
    (net (code "292") (name "unconnected-(AMP_3-MOTOR_C_2-PadP_7)") (class "Default")
      (node (ref "AMP_3") (pin "P_7") (pinfunction "MOTOR_C_2_P_7") (pintype "bidirectional"))
    )
    (net (code "293") (name "unconnected-(AMP_3-NC(KEY)-PadP_3)") (class "Default")
      (node (ref "AMP_3") (pin "P_3") (pinfunction "NC(KEY)_P_3") (pintype "bidirectional"))
    )
    (net (code "294") (name "unconnected-(AMP_3-NC_1-PadS_13)") (class "Default")
      (node (ref "AMP_3") (pin "S_13") (pinfunction "NC_1_S_13") (pintype "bidirectional"))
    )
    (net (code "295") (name "unconnected-(AMP_3-NC_2-PadS_14)") (class "Default")
      (node (ref "AMP_3") (pin "S_14") (pinfunction "NC_2_S_14") (pintype "bidirectional"))
    )
    (net (code "296") (name "unconnected-(AMP_3-NC_3-PadS_15)") (class "Default")
      (node (ref "AMP_3") (pin "S_15") (pinfunction "NC_3_S_15") (pintype "bidirectional"))
    )
    (net (code "297") (name "unconnected-(AMP_3-NC_4-PadS_16)") (class "Default")
      (node (ref "AMP_3") (pin "S_16") (pinfunction "NC_4_S_16") (pintype "bidirectional"))
    )
    (net (code "298") (name "unconnected-(AMP_4-+V_HALL_OUT-PadS_6)") (class "Default")
      (node (ref "AMP_4") (pin "S_6") (pinfunction "+V_HALL_OUT_S_6") (pintype "bidirectional"))
    )
    (net (code "299") (name "unconnected-(AMP_4-CURRENT_REF_OUT-PadS_11)") (class "Default")
      (node (ref "AMP_4") (pin "S_11") (pinfunction "CURRENT_REF_OUT_S_11") (pintype "bidirectional"))
    )
    (net (code "300") (name "unconnected-(AMP_4-HALL_1-PadS_8)") (class "Default")
      (node (ref "AMP_4") (pin "S_8") (pinfunction "HALL_1_S_8") (pintype "bidirectional"))
    )
    (net (code "301") (name "unconnected-(AMP_4-HALL_2-PadS_9)") (class "Default")
      (node (ref "AMP_4") (pin "S_9") (pinfunction "HALL_2_S_9") (pintype "bidirectional"))
    )
    (net (code "302") (name "unconnected-(AMP_4-HALL_3-PadS_10)") (class "Default")
      (node (ref "AMP_4") (pin "S_10") (pinfunction "HALL_3_S_10") (pintype "bidirectional"))
    )
    (net (code "303") (name "unconnected-(AMP_4-MOTOR_C_1-PadP_6)") (class "Default")
      (node (ref "AMP_4") (pin "P_6") (pinfunction "MOTOR_C_1_P_6") (pintype "bidirectional"))
    )
    (net (code "304") (name "unconnected-(AMP_4-MOTOR_C_2-PadP_7)") (class "Default")
      (node (ref "AMP_4") (pin "P_7") (pinfunction "MOTOR_C_2_P_7") (pintype "bidirectional"))
    )
    (net (code "305") (name "unconnected-(AMP_4-NC(KEY)-PadP_3)") (class "Default")
      (node (ref "AMP_4") (pin "P_3") (pinfunction "NC(KEY)_P_3") (pintype "bidirectional"))
    )
    (net (code "306") (name "unconnected-(AMP_4-NC_1-PadS_13)") (class "Default")
      (node (ref "AMP_4") (pin "S_13") (pinfunction "NC_1_S_13") (pintype "bidirectional"))
    )
    (net (code "307") (name "unconnected-(AMP_4-NC_2-PadS_14)") (class "Default")
      (node (ref "AMP_4") (pin "S_14") (pinfunction "NC_2_S_14") (pintype "bidirectional"))
    )
    (net (code "308") (name "unconnected-(AMP_4-NC_3-PadS_15)") (class "Default")
      (node (ref "AMP_4") (pin "S_15") (pinfunction "NC_3_S_15") (pintype "bidirectional"))
    )
    (net (code "309") (name "unconnected-(AMP_4-NC_4-PadS_16)") (class "Default")
      (node (ref "AMP_4") (pin "S_16") (pinfunction "NC_4_S_16") (pintype "bidirectional"))
    )
    (net (code "310") (name "unconnected-(AMP_5-+V_HALL_OUT-PadS_6)") (class "Default")
      (node (ref "AMP_5") (pin "S_6") (pinfunction "+V_HALL_OUT_S_6") (pintype "bidirectional"))
    )
    (net (code "311") (name "unconnected-(AMP_5-CURRENT_REF_OUT-PadS_11)") (class "Default")
      (node (ref "AMP_5") (pin "S_11") (pinfunction "CURRENT_REF_OUT_S_11") (pintype "bidirectional"))
    )
    (net (code "312") (name "unconnected-(AMP_5-HALL_1-PadS_8)") (class "Default")
      (node (ref "AMP_5") (pin "S_8") (pinfunction "HALL_1_S_8") (pintype "bidirectional"))
    )
    (net (code "313") (name "unconnected-(AMP_5-HALL_2-PadS_9)") (class "Default")
      (node (ref "AMP_5") (pin "S_9") (pinfunction "HALL_2_S_9") (pintype "bidirectional"))
    )
    (net (code "314") (name "unconnected-(AMP_5-HALL_3-PadS_10)") (class "Default")
      (node (ref "AMP_5") (pin "S_10") (pinfunction "HALL_3_S_10") (pintype "bidirectional"))
    )
    (net (code "315") (name "unconnected-(AMP_5-MOTOR_C_1-PadP_6)") (class "Default")
      (node (ref "AMP_5") (pin "P_6") (pinfunction "MOTOR_C_1_P_6") (pintype "bidirectional"))
    )
    (net (code "316") (name "unconnected-(AMP_5-MOTOR_C_2-PadP_7)") (class "Default")
      (node (ref "AMP_5") (pin "P_7") (pinfunction "MOTOR_C_2_P_7") (pintype "bidirectional"))
    )
    (net (code "317") (name "unconnected-(AMP_5-NC(KEY)-PadP_3)") (class "Default")
      (node (ref "AMP_5") (pin "P_3") (pinfunction "NC(KEY)_P_3") (pintype "bidirectional"))
    )
    (net (code "318") (name "unconnected-(AMP_5-NC_1-PadS_13)") (class "Default")
      (node (ref "AMP_5") (pin "S_13") (pinfunction "NC_1_S_13") (pintype "bidirectional"))
    )
    (net (code "319") (name "unconnected-(AMP_5-NC_2-PadS_14)") (class "Default")
      (node (ref "AMP_5") (pin "S_14") (pinfunction "NC_2_S_14") (pintype "bidirectional"))
    )
    (net (code "320") (name "unconnected-(AMP_5-NC_3-PadS_15)") (class "Default")
      (node (ref "AMP_5") (pin "S_15") (pinfunction "NC_3_S_15") (pintype "bidirectional"))
    )
    (net (code "321") (name "unconnected-(AMP_5-NC_4-PadS_16)") (class "Default")
      (node (ref "AMP_5") (pin "S_16") (pinfunction "NC_4_S_16") (pintype "bidirectional"))
    )
    (net (code "322") (name "unconnected-(IC1A-Y7-Pad12)") (class "Default")
      (node (ref "IC1") (pin "12") (pinfunction "Y7_12") (pintype "tri_state"))
    )
    (net (code "323") (name "unconnected-(IC1A-Y8-Pad11)") (class "Default")
      (node (ref "IC1") (pin "11") (pinfunction "Y8_11") (pintype "tri_state"))
    )
    (net (code "324") (name "unconnected-(IC3A-Y7-Pad12)") (class "Default")
      (node (ref "IC3") (pin "12") (pinfunction "Y7_12") (pintype "tri_state"))
    )
    (net (code "325") (name "unconnected-(IC3A-Y8-Pad11)") (class "Default")
      (node (ref "IC3") (pin "11") (pinfunction "Y8_11") (pintype "tri_state"))
    )
    (net (code "326") (name "unconnected-(J7-GND_ISO-PadP$6)") (class "Default")
      (node (ref "J7") (pin "P$6") (pinfunction "GND_ISO_P$6") (pintype "bidirectional"))
    )
    (net (code "327") (name "unconnected-(J7-GND_ISO-PadP$56)") (class "Default")
      (node (ref "J7") (pin "P$56") (pinfunction "GND_ISO_P$56") (pintype "bidirectional"))
    )
    (net (code "328") (name "unconnected-(J7-ISO_RX_RS232-PadP$2)") (class "Default")
      (node (ref "J7") (pin "P$2") (pinfunction "ISO_RX_RS232_P$2") (pintype "bidirectional"))
    )
    (net (code "329") (name "unconnected-(J7-ISO_TX_RX232-PadP$52)") (class "Default")
      (node (ref "J7") (pin "P$52") (pinfunction "ISO_TX_RX232_P$52") (pintype "bidirectional"))
    )
    (net (code "330") (name "unconnected-(J7-NC-PadP$3)") (class "Default")
      (node (ref "J7") (pin "P$3") (pinfunction "NC_P$3") (pintype "bidirectional"))
    )
    (net (code "331") (name "unconnected-(J7-NC-PadP$4)") (class "Default")
      (node (ref "J7") (pin "P$4") (pinfunction "NC_P$4") (pintype "bidirectional"))
    )
    (net (code "332") (name "unconnected-(J7-NC-PadP$5)") (class "Default")
      (node (ref "J7") (pin "P$5") (pinfunction "NC_P$5") (pintype "bidirectional"))
    )
    (net (code "333") (name "unconnected-(J7-NC-PadP$16)") (class "Default")
      (node (ref "J7") (pin "P$16") (pinfunction "NC_P$16") (pintype "bidirectional"))
    )
    (net (code "334") (name "unconnected-(J7-NC-PadP$53)") (class "Default")
      (node (ref "J7") (pin "P$53") (pinfunction "NC_P$53") (pintype "bidirectional"))
    )
    (net (code "335") (name "unconnected-(J7-NC-PadP$54)") (class "Default")
      (node (ref "J7") (pin "P$54") (pinfunction "NC_P$54") (pintype "bidirectional"))
    )
    (net (code "336") (name "unconnected-(J7-NC-PadP$55)") (class "Default")
      (node (ref "J7") (pin "P$55") (pinfunction "NC_P$55") (pintype "bidirectional"))
    )
    (net (code "337") (name "unconnected-(J7-NC-PadP$66)") (class "Default")
      (node (ref "J7") (pin "P$66") (pinfunction "NC_P$66") (pintype "bidirectional"))
    )
    (net (code "338") (name "unconnected-(J7-V33D_ISO-PadP$1)") (class "Default")
      (node (ref "J7") (pin "P$1") (pinfunction "V33D_ISO_P$1") (pintype "bidirectional"))
    )
    (net (code "339") (name "unconnected-(J7-V33D_ISO-PadP$51)") (class "Default")
      (node (ref "J7") (pin "P$51") (pinfunction "V33D_ISO_P$51") (pintype "bidirectional"))
    )
    (net (code "340") (name "unconnected-(PINS-Pad3)") (class "Default")
      (node (ref "PINS") (pin "3") (pinfunction "3_3") (pintype "passive"))
    )
    (net (code "341") (name "unconnected-(PINS-Pad4)") (class "Default")
      (node (ref "PINS") (pin "4") (pinfunction "4_4") (pintype "passive"))
    )
    (net (code "342") (name "unconnected-(PINS-Pad7)") (class "Default")
      (node (ref "PINS") (pin "7") (pinfunction "7_7") (pintype "passive"))
    )
    (net (code "343") (name "unconnected-(QG1-TS-Pad1)") (class "Default")
      (node (ref "QG1") (pin "1") (pinfunction "TS_1") (pintype "passive"))
    )
    (net (code "344") (name "unconnected-(SV1-+V_HALL_OUT-Pad6)") (class "Default")
      (node (ref "SV1") (pin "6") (pinfunction "+V_HALL_OUT_6") (pintype "passive"))
    )
    (net (code "345") (name "unconnected-(SV1-CURRENT_REF_OUT-Pad11)") (class "Default")
      (node (ref "SV1") (pin "11") (pinfunction "CURRENT_REF_OUT_11") (pintype "passive"))
    )
    (net (code "346") (name "unconnected-(SV1-HALL_1-Pad8)") (class "Default")
      (node (ref "SV1") (pin "8") (pinfunction "HALL_1_8") (pintype "passive"))
    )
    (net (code "347") (name "unconnected-(SV1-HALL_2-Pad9)") (class "Default")
      (node (ref "SV1") (pin "9") (pinfunction "HALL_2_9") (pintype "passive"))
    )
    (net (code "348") (name "unconnected-(SV1-HALL_3-Pad10)") (class "Default")
      (node (ref "SV1") (pin "10") (pinfunction "HALL_3_10") (pintype "passive"))
    )
    (net (code "349") (name "unconnected-(SV1-NC_1-Pad13)") (class "Default")
      (node (ref "SV1") (pin "13") (pinfunction "NC_1_13") (pintype "passive"))
    )
    (net (code "350") (name "unconnected-(SV1-NC_2-Pad14)") (class "Default")
      (node (ref "SV1") (pin "14") (pinfunction "NC_2_14") (pintype "passive"))
    )
    (net (code "351") (name "unconnected-(SV1-NC_3-Pad15)") (class "Default")
      (node (ref "SV1") (pin "15") (pinfunction "NC_3_15") (pintype "passive"))
    )
    (net (code "352") (name "unconnected-(SV1-NC_4-Pad16)") (class "Default")
      (node (ref "SV1") (pin "16") (pinfunction "NC_4_16") (pintype "passive"))
    )
    (net (code "353") (name "unconnected-(SV2-+V_HALL_OUT-Pad6)") (class "Default")
      (node (ref "SV2") (pin "6") (pinfunction "+V_HALL_OUT_6") (pintype "passive"))
    )
    (net (code "354") (name "unconnected-(SV2-CURRENT_REF_OUT-Pad11)") (class "Default")
      (node (ref "SV2") (pin "11") (pinfunction "CURRENT_REF_OUT_11") (pintype "passive"))
    )
    (net (code "355") (name "unconnected-(SV2-HALL_1-Pad8)") (class "Default")
      (node (ref "SV2") (pin "8") (pinfunction "HALL_1_8") (pintype "passive"))
    )
    (net (code "356") (name "unconnected-(SV2-HALL_2-Pad9)") (class "Default")
      (node (ref "SV2") (pin "9") (pinfunction "HALL_2_9") (pintype "passive"))
    )
    (net (code "357") (name "unconnected-(SV2-HALL_3-Pad10)") (class "Default")
      (node (ref "SV2") (pin "10") (pinfunction "HALL_3_10") (pintype "passive"))
    )
    (net (code "358") (name "unconnected-(SV2-NC_1-Pad13)") (class "Default")
      (node (ref "SV2") (pin "13") (pinfunction "NC_1_13") (pintype "passive"))
    )
    (net (code "359") (name "unconnected-(SV2-NC_2-Pad14)") (class "Default")
      (node (ref "SV2") (pin "14") (pinfunction "NC_2_14") (pintype "passive"))
    )
    (net (code "360") (name "unconnected-(SV2-NC_3-Pad15)") (class "Default")
      (node (ref "SV2") (pin "15") (pinfunction "NC_3_15") (pintype "passive"))
    )
    (net (code "361") (name "unconnected-(SV2-NC_4-Pad16)") (class "Default")
      (node (ref "SV2") (pin "16") (pinfunction "NC_4_16") (pintype "passive"))
    )
    (net (code "362") (name "unconnected-(SV3-+V_HALL_OUT-Pad6)") (class "Default")
      (node (ref "SV3") (pin "6") (pinfunction "+V_HALL_OUT_6") (pintype "passive"))
    )
    (net (code "363") (name "unconnected-(SV3-CURRENT_REF_OUT-Pad11)") (class "Default")
      (node (ref "SV3") (pin "11") (pinfunction "CURRENT_REF_OUT_11") (pintype "passive"))
    )
    (net (code "364") (name "unconnected-(SV3-HALL_1-Pad8)") (class "Default")
      (node (ref "SV3") (pin "8") (pinfunction "HALL_1_8") (pintype "passive"))
    )
    (net (code "365") (name "unconnected-(SV3-HALL_2-Pad9)") (class "Default")
      (node (ref "SV3") (pin "9") (pinfunction "HALL_2_9") (pintype "passive"))
    )
    (net (code "366") (name "unconnected-(SV3-HALL_3-Pad10)") (class "Default")
      (node (ref "SV3") (pin "10") (pinfunction "HALL_3_10") (pintype "passive"))
    )
    (net (code "367") (name "unconnected-(SV3-NC_1-Pad13)") (class "Default")
      (node (ref "SV3") (pin "13") (pinfunction "NC_1_13") (pintype "passive"))
    )
    (net (code "368") (name "unconnected-(SV3-NC_2-Pad14)") (class "Default")
      (node (ref "SV3") (pin "14") (pinfunction "NC_2_14") (pintype "passive"))
    )
    (net (code "369") (name "unconnected-(SV3-NC_3-Pad15)") (class "Default")
      (node (ref "SV3") (pin "15") (pinfunction "NC_3_15") (pintype "passive"))
    )
    (net (code "370") (name "unconnected-(SV3-NC_4-Pad16)") (class "Default")
      (node (ref "SV3") (pin "16") (pinfunction "NC_4_16") (pintype "passive"))
    )
    (net (code "371") (name "unconnected-(SV4-+V_HALL_OUT-Pad6)") (class "Default")
      (node (ref "SV4") (pin "6") (pinfunction "+V_HALL_OUT_6") (pintype "passive"))
    )
    (net (code "372") (name "unconnected-(SV4-CURRENT_REF_OUT-Pad11)") (class "Default")
      (node (ref "SV4") (pin "11") (pinfunction "CURRENT_REF_OUT_11") (pintype "passive"))
    )
    (net (code "373") (name "unconnected-(SV4-HALL_1-Pad8)") (class "Default")
      (node (ref "SV4") (pin "8") (pinfunction "HALL_1_8") (pintype "passive"))
    )
    (net (code "374") (name "unconnected-(SV4-HALL_2-Pad9)") (class "Default")
      (node (ref "SV4") (pin "9") (pinfunction "HALL_2_9") (pintype "passive"))
    )
    (net (code "375") (name "unconnected-(SV4-HALL_3-Pad10)") (class "Default")
      (node (ref "SV4") (pin "10") (pinfunction "HALL_3_10") (pintype "passive"))
    )
    (net (code "376") (name "unconnected-(SV4-NC_1-Pad13)") (class "Default")
      (node (ref "SV4") (pin "13") (pinfunction "NC_1_13") (pintype "passive"))
    )
    (net (code "377") (name "unconnected-(SV4-NC_2-Pad14)") (class "Default")
      (node (ref "SV4") (pin "14") (pinfunction "NC_2_14") (pintype "passive"))
    )
    (net (code "378") (name "unconnected-(SV4-NC_3-Pad15)") (class "Default")
      (node (ref "SV4") (pin "15") (pinfunction "NC_3_15") (pintype "passive"))
    )
    (net (code "379") (name "unconnected-(SV4-NC_4-Pad16)") (class "Default")
      (node (ref "SV4") (pin "16") (pinfunction "NC_4_16") (pintype "passive"))
    )
    (net (code "380") (name "unconnected-(SV5-+V_HALL_OUT-Pad6)") (class "Default")
      (node (ref "SV5") (pin "6") (pinfunction "+V_HALL_OUT_6") (pintype "passive"))
    )
    (net (code "381") (name "unconnected-(SV5-CURRENT_REF_OUT-Pad11)") (class "Default")
      (node (ref "SV5") (pin "11") (pinfunction "CURRENT_REF_OUT_11") (pintype "passive"))
    )
    (net (code "382") (name "unconnected-(SV5-HALL_1-Pad8)") (class "Default")
      (node (ref "SV5") (pin "8") (pinfunction "HALL_1_8") (pintype "passive"))
    )
    (net (code "383") (name "unconnected-(SV5-HALL_2-Pad9)") (class "Default")
      (node (ref "SV5") (pin "9") (pinfunction "HALL_2_9") (pintype "passive"))
    )
    (net (code "384") (name "unconnected-(SV5-HALL_3-Pad10)") (class "Default")
      (node (ref "SV5") (pin "10") (pinfunction "HALL_3_10") (pintype "passive"))
    )
    (net (code "385") (name "unconnected-(SV5-NC_1-Pad13)") (class "Default")
      (node (ref "SV5") (pin "13") (pinfunction "NC_1_13") (pintype "passive"))
    )
    (net (code "386") (name "unconnected-(SV5-NC_2-Pad14)") (class "Default")
      (node (ref "SV5") (pin "14") (pinfunction "NC_2_14") (pintype "passive"))
    )
    (net (code "387") (name "unconnected-(SV5-NC_3-Pad15)") (class "Default")
      (node (ref "SV5") (pin "15") (pinfunction "NC_3_15") (pintype "passive"))
    )
    (net (code "388") (name "unconnected-(SV5-NC_4-Pad16)") (class "Default")
      (node (ref "SV5") (pin "16") (pinfunction "NC_4_16") (pintype "passive"))
    )
    (net (code "389") (name "unconnected-(SV6-Pad7)") (class "Default")
      (node (ref "SV6") (pin "7") (pinfunction "7_7") (pintype "passive"))
    )
    (net (code "390") (name "unconnected-(SV6-Pad9)") (class "Default")
      (node (ref "SV6") (pin "9") (pinfunction "9_9") (pintype "passive"))
    )
    (net (code "391") (name "unconnected-(SV6-Pad10)") (class "Default")
      (node (ref "SV6") (pin "10") (pinfunction "10_10") (pintype "passive"))
    )
    (net (code "392") (name "unconnected-(SV12-Pad4)") (class "Default")
      (node (ref "SV12") (pin "4") (pinfunction "4_4") (pintype "passive"))
    )
    (net (code "393") (name "unconnected-(SV13-Pad4)") (class "Default")
      (node (ref "SV13") (pin "4") (pinfunction "4_4") (pintype "passive"))
    )
    (net (code "394") (name "unconnected-(SV14-Pad4)") (class "Default")
      (node (ref "SV14") (pin "4") (pinfunction "4_4") (pintype "passive"))
    )
    (net (code "395") (name "unconnected-(SV15-Pad4)") (class "Default")
      (node (ref "SV15") (pin "4") (pinfunction "4_4") (pintype "passive"))
    )
    (net (code "396") (name "unconnected-(SV19-Pad7)") (class "Default")
      (node (ref "SV19") (pin "7") (pinfunction "7_7") (pintype "passive"))
    )
    (net (code "397") (name "unconnected-(SV19-Pad9)") (class "Default")
      (node (ref "SV19") (pin "9") (pinfunction "9_9") (pintype "passive"))
    )
    (net (code "398") (name "unconnected-(SV19-Pad10)") (class "Default")
      (node (ref "SV19") (pin "10") (pinfunction "10_10") (pintype "passive"))
    )
    (net (code "399") (name "unconnected-(SV28-Pad3)") (class "Default")
      (node (ref "SV28") (pin "3") (pinfunction "3_3") (pintype "passive"))
    )
    (net (code "400") (name "unconnected-(SV28-Pad4)") (class "Default")
      (node (ref "SV28") (pin "4") (pinfunction "4_4") (pintype "passive"))
    )
    (net (code "401") (name "unconnected-(U3-TEST-Pad38)") (class "Default")
      (node (ref "U3") (pin "38") (pinfunction "TEST_38") (pintype "bidirectional"))
    )
    (net (code "402") (name "unconnected-(U3-{slash}XRS-Pad17)") (class "Default")
      (node (ref "U3") (pin "17") (pinfunction "/XRS_17") (pintype "bidirectional"))
    )
    (net (code "403") (name "unconnected-(U4-DIN2-Pad10)") (class "Default")
      (node (ref "U4") (pin "10") (pinfunction "DIN2_10") (pintype "bidirectional"))
    )
    (net (code "404") (name "unconnected-(U4-ROUT2-Pad9)") (class "Default")
      (node (ref "U4") (pin "9") (pinfunction "ROUT2_9") (pintype "bidirectional"))
    )
    (net (code "405") (name "unconnected-(U6-OSCI-Pad27)") (class "Default")
      (node (ref "U6") (pin "27") (pinfunction "OSCI_27") (pintype "input"))
    )
    (net (code "406") (name "unconnected-(U6-OSCO-Pad28)") (class "Default")
      (node (ref "U6") (pin "28") (pinfunction "OSCO_28") (pintype "output"))
    )
    (net (code "407") (name "unconnected-(U6-RESET#-Pad19)") (class "Default")
      (node (ref "U6") (pin "19") (pinfunction "RESET#_19") (pintype "input"))
    )
    (net (code "408") (name "unconnected-(U7-CNT_EN-Pad13)") (class "Default")
      (node (ref "U7") (pin "13") (pinfunction "CNT_EN_13") (pintype "bidirectional"))
    )
    (net (code "409") (name "unconnected-(U7-DFLAG{slash}-Pad9)") (class "Default")
      (node (ref "U7") (pin "9") (pinfunction "DFLAG/_9") (pintype "bidirectional"))
    )
    (net (code "410") (name "unconnected-(U7-FCKO-Pad1)") (class "Default")
      (node (ref "U7") (pin "1") (pinfunction "FCKO_1") (pintype "bidirectional"))
    )
    (net (code "411") (name "unconnected-(U7-INDEX{slash}-Pad10)") (class "Default")
      (node (ref "U7") (pin "10") (pinfunction "INDEX/_10") (pintype "bidirectional"))
    )
    (net (code "412") (name "unconnected-(U7-LFLAG{slash}-Pad8)") (class "Default")
      (node (ref "U7") (pin "8") (pinfunction "LFLAG/_8") (pintype "bidirectional"))
    )
    (net (code "413") (name "unconnected-(U8-CNT_EN-Pad13)") (class "Default")
      (node (ref "U8") (pin "13") (pinfunction "CNT_EN_13") (pintype "bidirectional"))
    )
    (net (code "414") (name "unconnected-(U8-DFLAG{slash}-Pad9)") (class "Default")
      (node (ref "U8") (pin "9") (pinfunction "DFLAG/_9") (pintype "bidirectional"))
    )
    (net (code "415") (name "unconnected-(U8-FCKO-Pad1)") (class "Default")
      (node (ref "U8") (pin "1") (pinfunction "FCKO_1") (pintype "bidirectional"))
    )
    (net (code "416") (name "unconnected-(U8-INDEX{slash}-Pad10)") (class "Default")
      (node (ref "U8") (pin "10") (pinfunction "INDEX/_10") (pintype "bidirectional"))
    )
    (net (code "417") (name "unconnected-(U8-LFLAG{slash}-Pad8)") (class "Default")
      (node (ref "U8") (pin "8") (pinfunction "LFLAG/_8") (pintype "bidirectional"))
    )
    (net (code "418") (name "unconnected-(U9-CNT_EN-Pad13)") (class "Default")
      (node (ref "U9") (pin "13") (pinfunction "CNT_EN_13") (pintype "bidirectional"))
    )
    (net (code "419") (name "unconnected-(U9-DFLAG{slash}-Pad9)") (class "Default")
      (node (ref "U9") (pin "9") (pinfunction "DFLAG/_9") (pintype "bidirectional"))
    )
    (net (code "420") (name "unconnected-(U9-FCKO-Pad1)") (class "Default")
      (node (ref "U9") (pin "1") (pinfunction "FCKO_1") (pintype "bidirectional"))
    )
    (net (code "421") (name "unconnected-(U9-INDEX{slash}-Pad10)") (class "Default")
      (node (ref "U9") (pin "10") (pinfunction "INDEX/_10") (pintype "bidirectional"))
    )
    (net (code "422") (name "unconnected-(U9-LFLAG{slash}-Pad8)") (class "Default")
      (node (ref "U9") (pin "8") (pinfunction "LFLAG/_8") (pintype "bidirectional"))
    )
    (net (code "423") (name "unconnected-(U10-CNT_EN-Pad13)") (class "Default")
      (node (ref "U10") (pin "13") (pinfunction "CNT_EN_13") (pintype "bidirectional"))
    )
    (net (code "424") (name "unconnected-(U10-DFLAG{slash}-Pad9)") (class "Default")
      (node (ref "U10") (pin "9") (pinfunction "DFLAG/_9") (pintype "bidirectional"))
    )
    (net (code "425") (name "unconnected-(U10-FCKO-Pad1)") (class "Default")
      (node (ref "U10") (pin "1") (pinfunction "FCKO_1") (pintype "bidirectional"))
    )
    (net (code "426") (name "unconnected-(U10-INDEX{slash}-Pad10)") (class "Default")
      (node (ref "U10") (pin "10") (pinfunction "INDEX/_10") (pintype "bidirectional"))
    )
    (net (code "427") (name "unconnected-(U10-LFLAG{slash}-Pad8)") (class "Default")
      (node (ref "U10") (pin "8") (pinfunction "LFLAG/_8") (pintype "bidirectional"))
    )
    (net (code "428") (name "unconnected-(U12-CNT_EN-Pad13)") (class "Default")
      (node (ref "U12") (pin "13") (pinfunction "CNT_EN_13") (pintype "bidirectional"))
    )
    (net (code "429") (name "unconnected-(U12-DFLAG{slash}-Pad9)") (class "Default")
      (node (ref "U12") (pin "9") (pinfunction "DFLAG/_9") (pintype "bidirectional"))
    )
    (net (code "430") (name "unconnected-(U12-FCKO-Pad1)") (class "Default")
      (node (ref "U12") (pin "1") (pinfunction "FCKO_1") (pintype "bidirectional"))
    )
    (net (code "431") (name "unconnected-(U12-INDEX{slash}-Pad10)") (class "Default")
      (node (ref "U12") (pin "10") (pinfunction "INDEX/_10") (pintype "bidirectional"))
    )
    (net (code "432") (name "unconnected-(U12-LFLAG{slash}-Pad8)") (class "Default")
      (node (ref "U12") (pin "8") (pinfunction "LFLAG/_8") (pintype "bidirectional"))
    )
    (net (code "433") (name "unconnected-(U13-CNT_EN-Pad13)") (class "Default")
      (node (ref "U13") (pin "13") (pinfunction "CNT_EN_13") (pintype "bidirectional"))
    )
    (net (code "434") (name "unconnected-(U13-DFLAG{slash}-Pad9)") (class "Default")
      (node (ref "U13") (pin "9") (pinfunction "DFLAG/_9") (pintype "bidirectional"))
    )
    (net (code "435") (name "unconnected-(U13-FCKO-Pad1)") (class "Default")
      (node (ref "U13") (pin "1") (pinfunction "FCKO_1") (pintype "bidirectional"))
    )
    (net (code "436") (name "unconnected-(U13-INDEX{slash}-Pad10)") (class "Default")
      (node (ref "U13") (pin "10") (pinfunction "INDEX/_10") (pintype "bidirectional"))
    )
    (net (code "437") (name "unconnected-(U13-LFLAG{slash}-Pad8)") (class "Default")
      (node (ref "U13") (pin "8") (pinfunction "LFLAG/_8") (pintype "bidirectional"))
    )
    (net (code "438") (name "unconnected-(U14-CNT_EN-Pad13)") (class "Default")
      (node (ref "U14") (pin "13") (pinfunction "CNT_EN_13") (pintype "bidirectional"))
    )
    (net (code "439") (name "unconnected-(U14-DFLAG{slash}-Pad9)") (class "Default")
      (node (ref "U14") (pin "9") (pinfunction "DFLAG/_9") (pintype "bidirectional"))
    )
    (net (code "440") (name "unconnected-(U14-FCKO-Pad1)") (class "Default")
      (node (ref "U14") (pin "1") (pinfunction "FCKO_1") (pintype "bidirectional"))
    )
    (net (code "441") (name "unconnected-(U14-INDEX{slash}-Pad10)") (class "Default")
      (node (ref "U14") (pin "10") (pinfunction "INDEX/_10") (pintype "bidirectional"))
    )
    (net (code "442") (name "unconnected-(U14-LFLAG{slash}-Pad8)") (class "Default")
      (node (ref "U14") (pin "8") (pinfunction "LFLAG/_8") (pintype "bidirectional"))
    )
  )
)
